# Main.net
KiCad netlist of a schematic drawn in Altium Designer
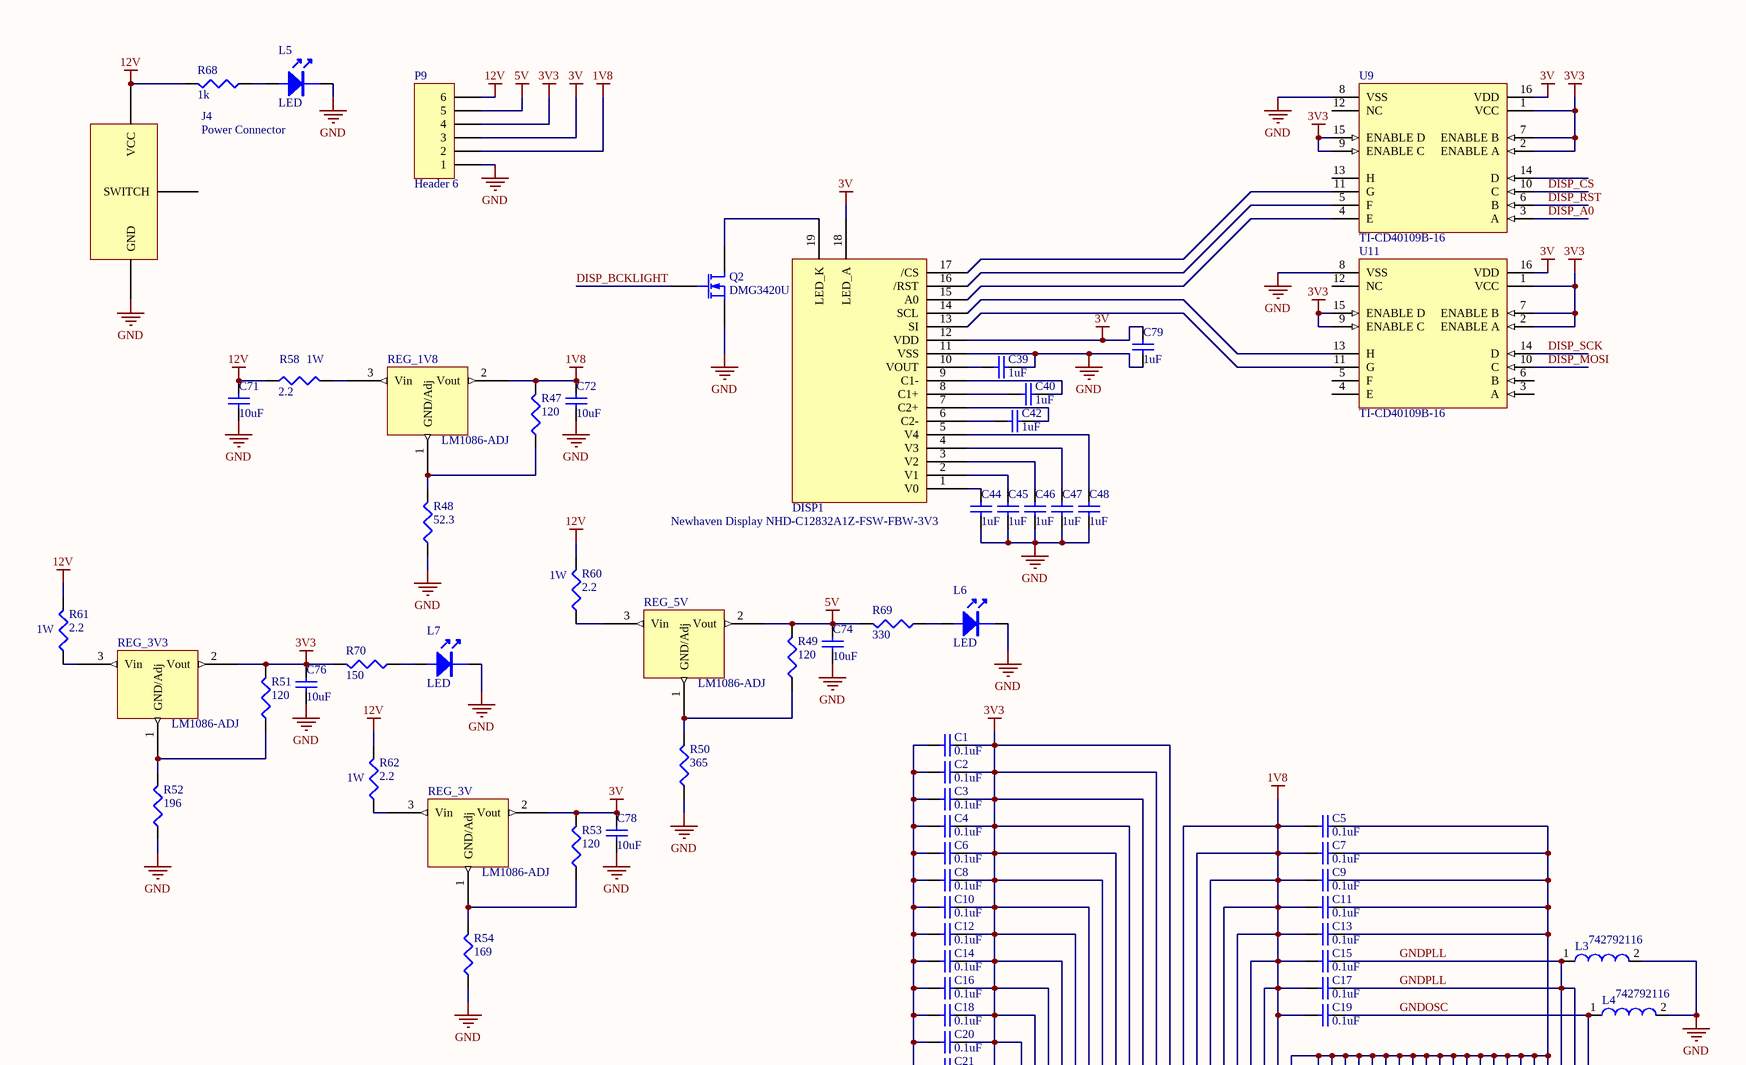
[diagram p0: Main.SchDoc, top left]
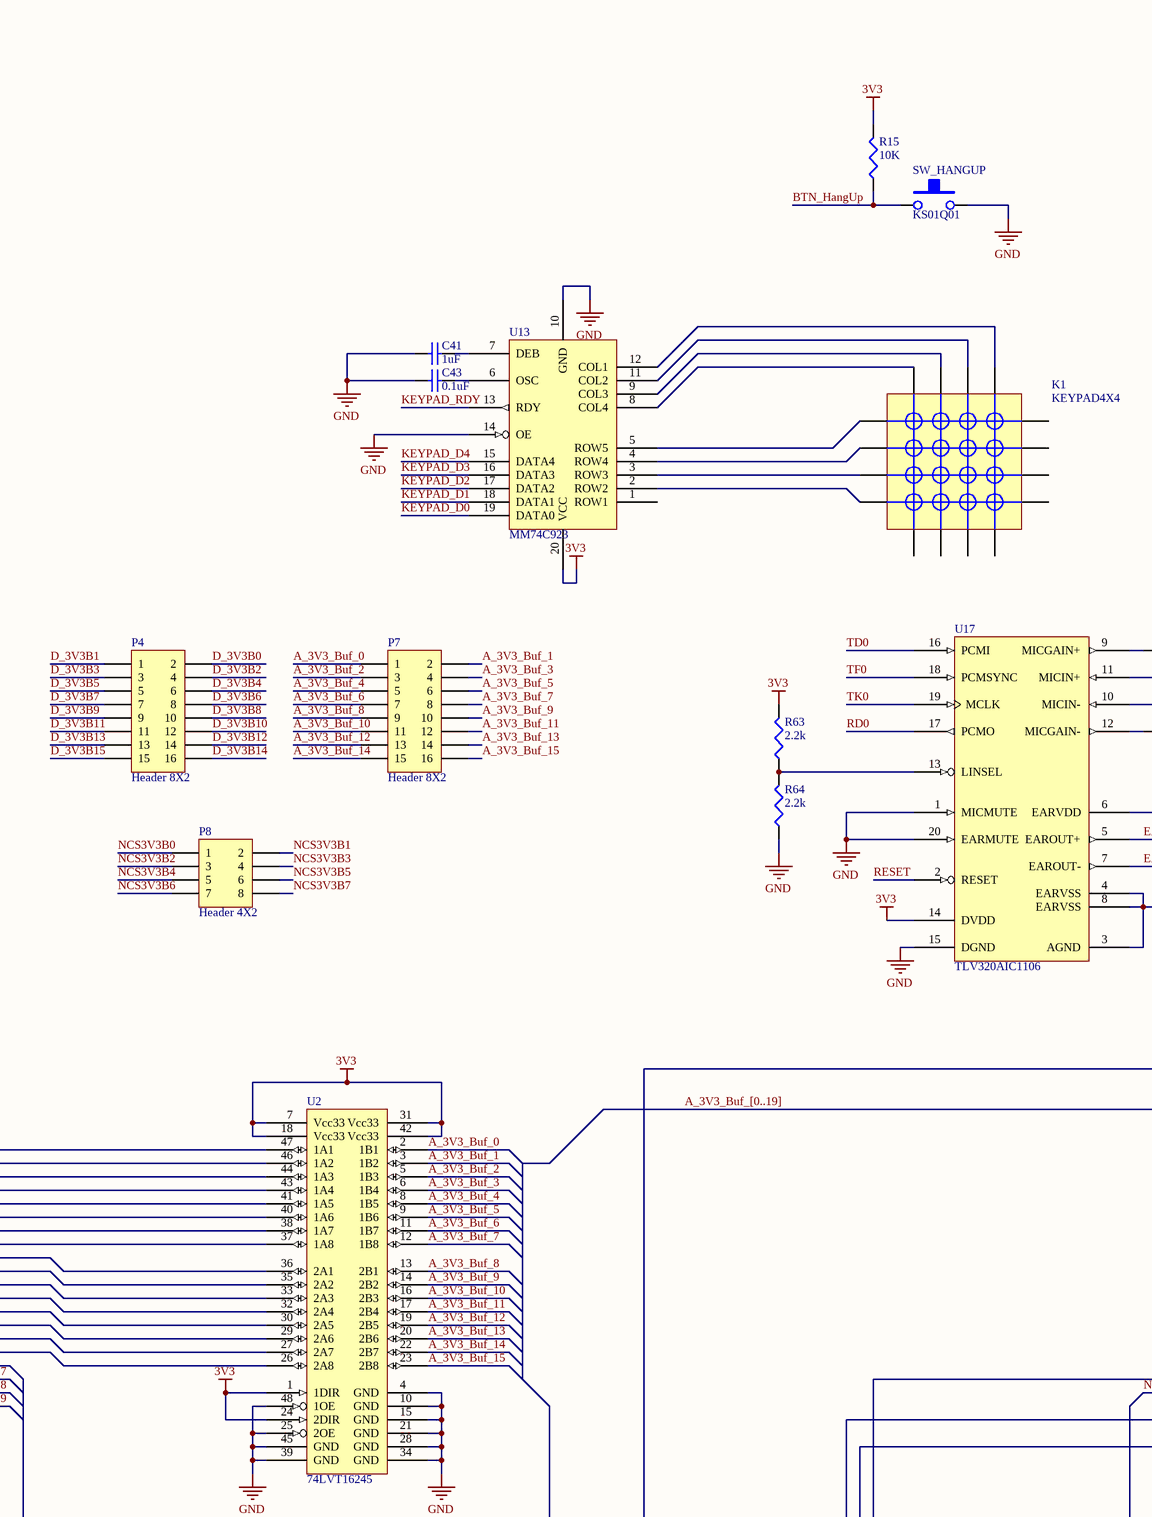
[diagram p1: Main.SchDoc, top middle]
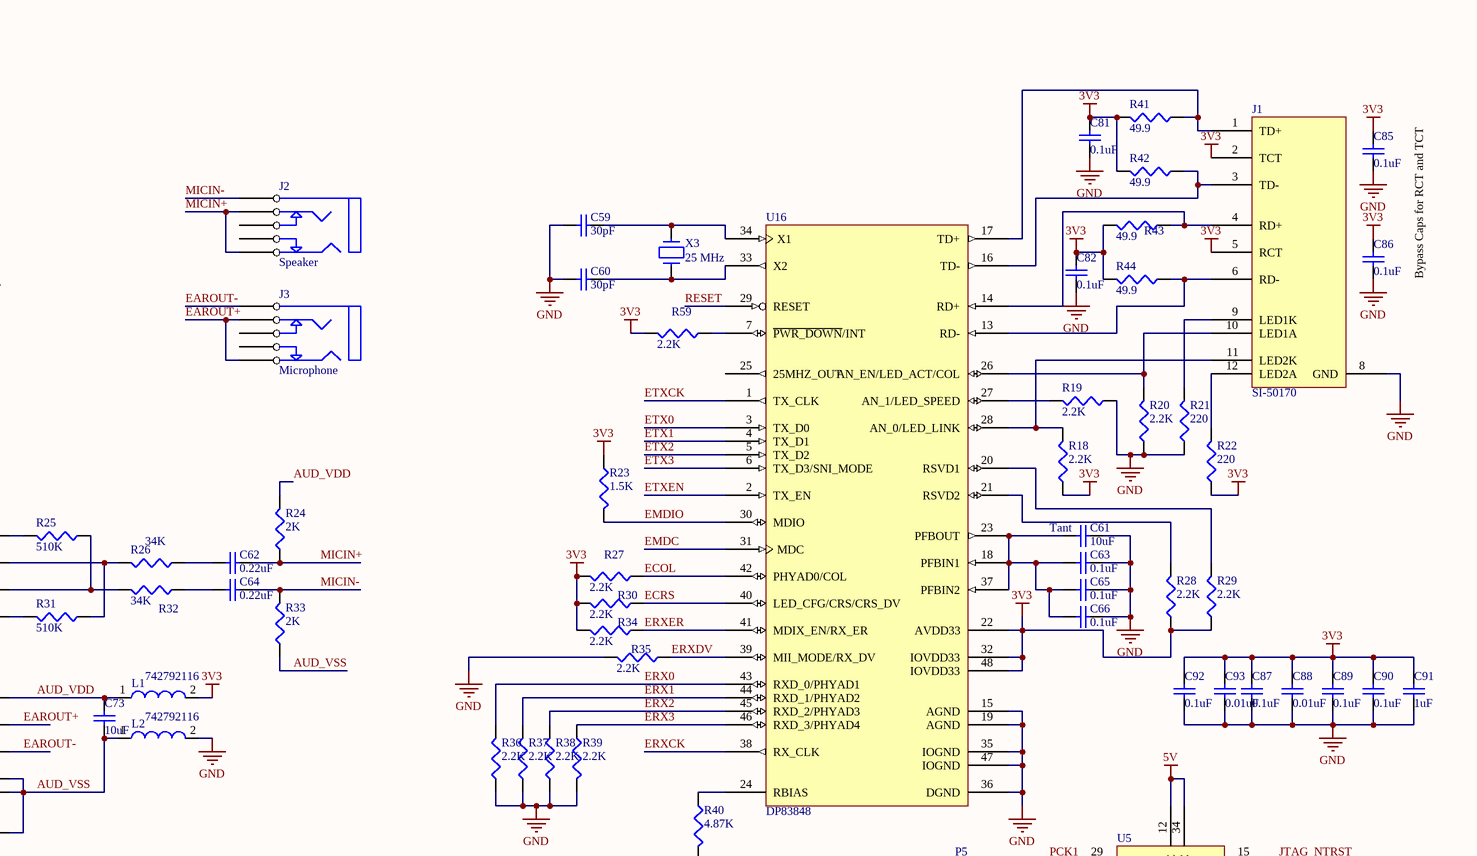
[diagram p2: Main.SchDoc, top right]
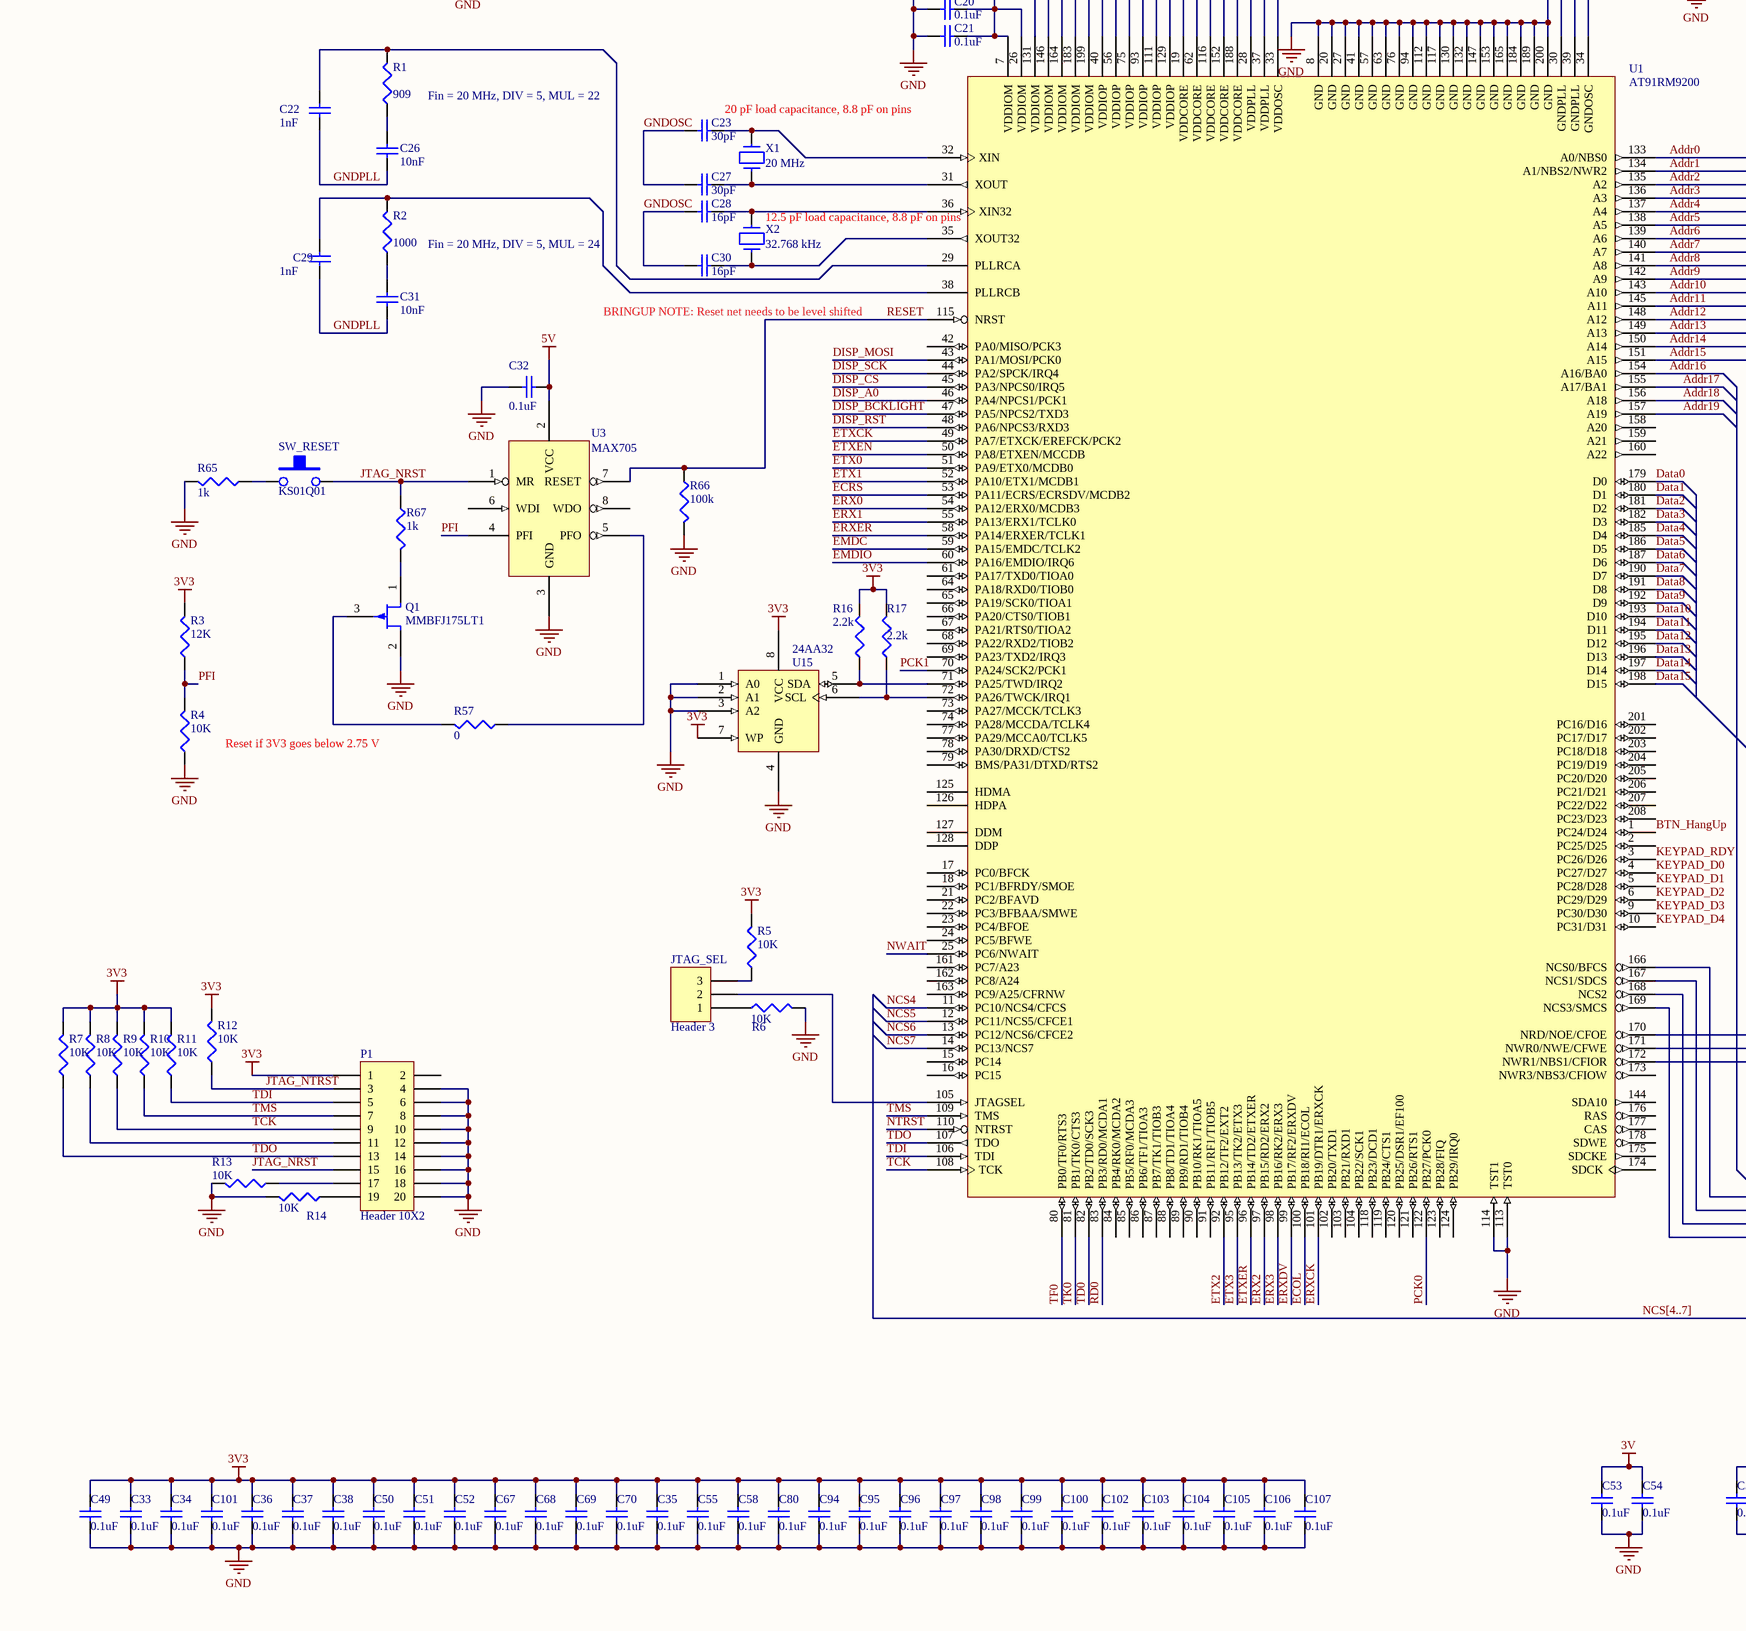
[diagram p3: Main.SchDoc, bottom left]
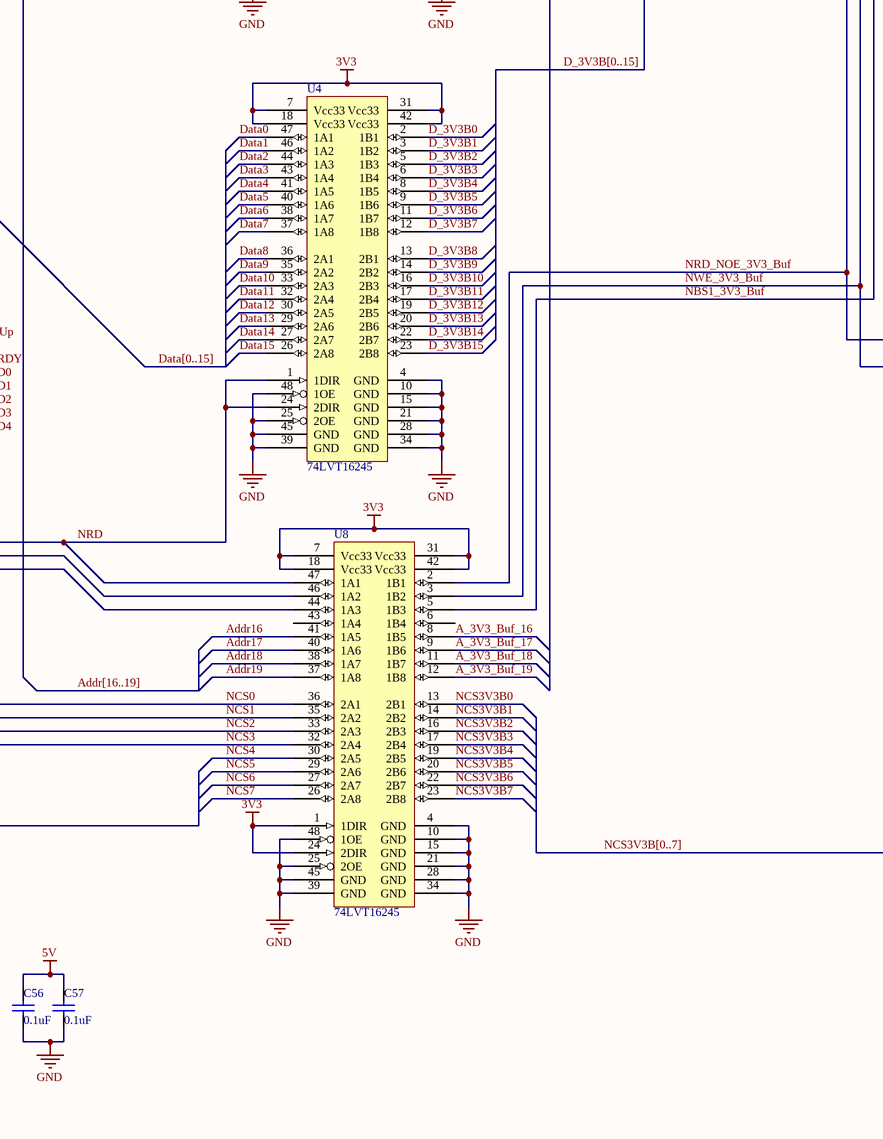
[diagram p4: Main.SchDoc, bottom middle]
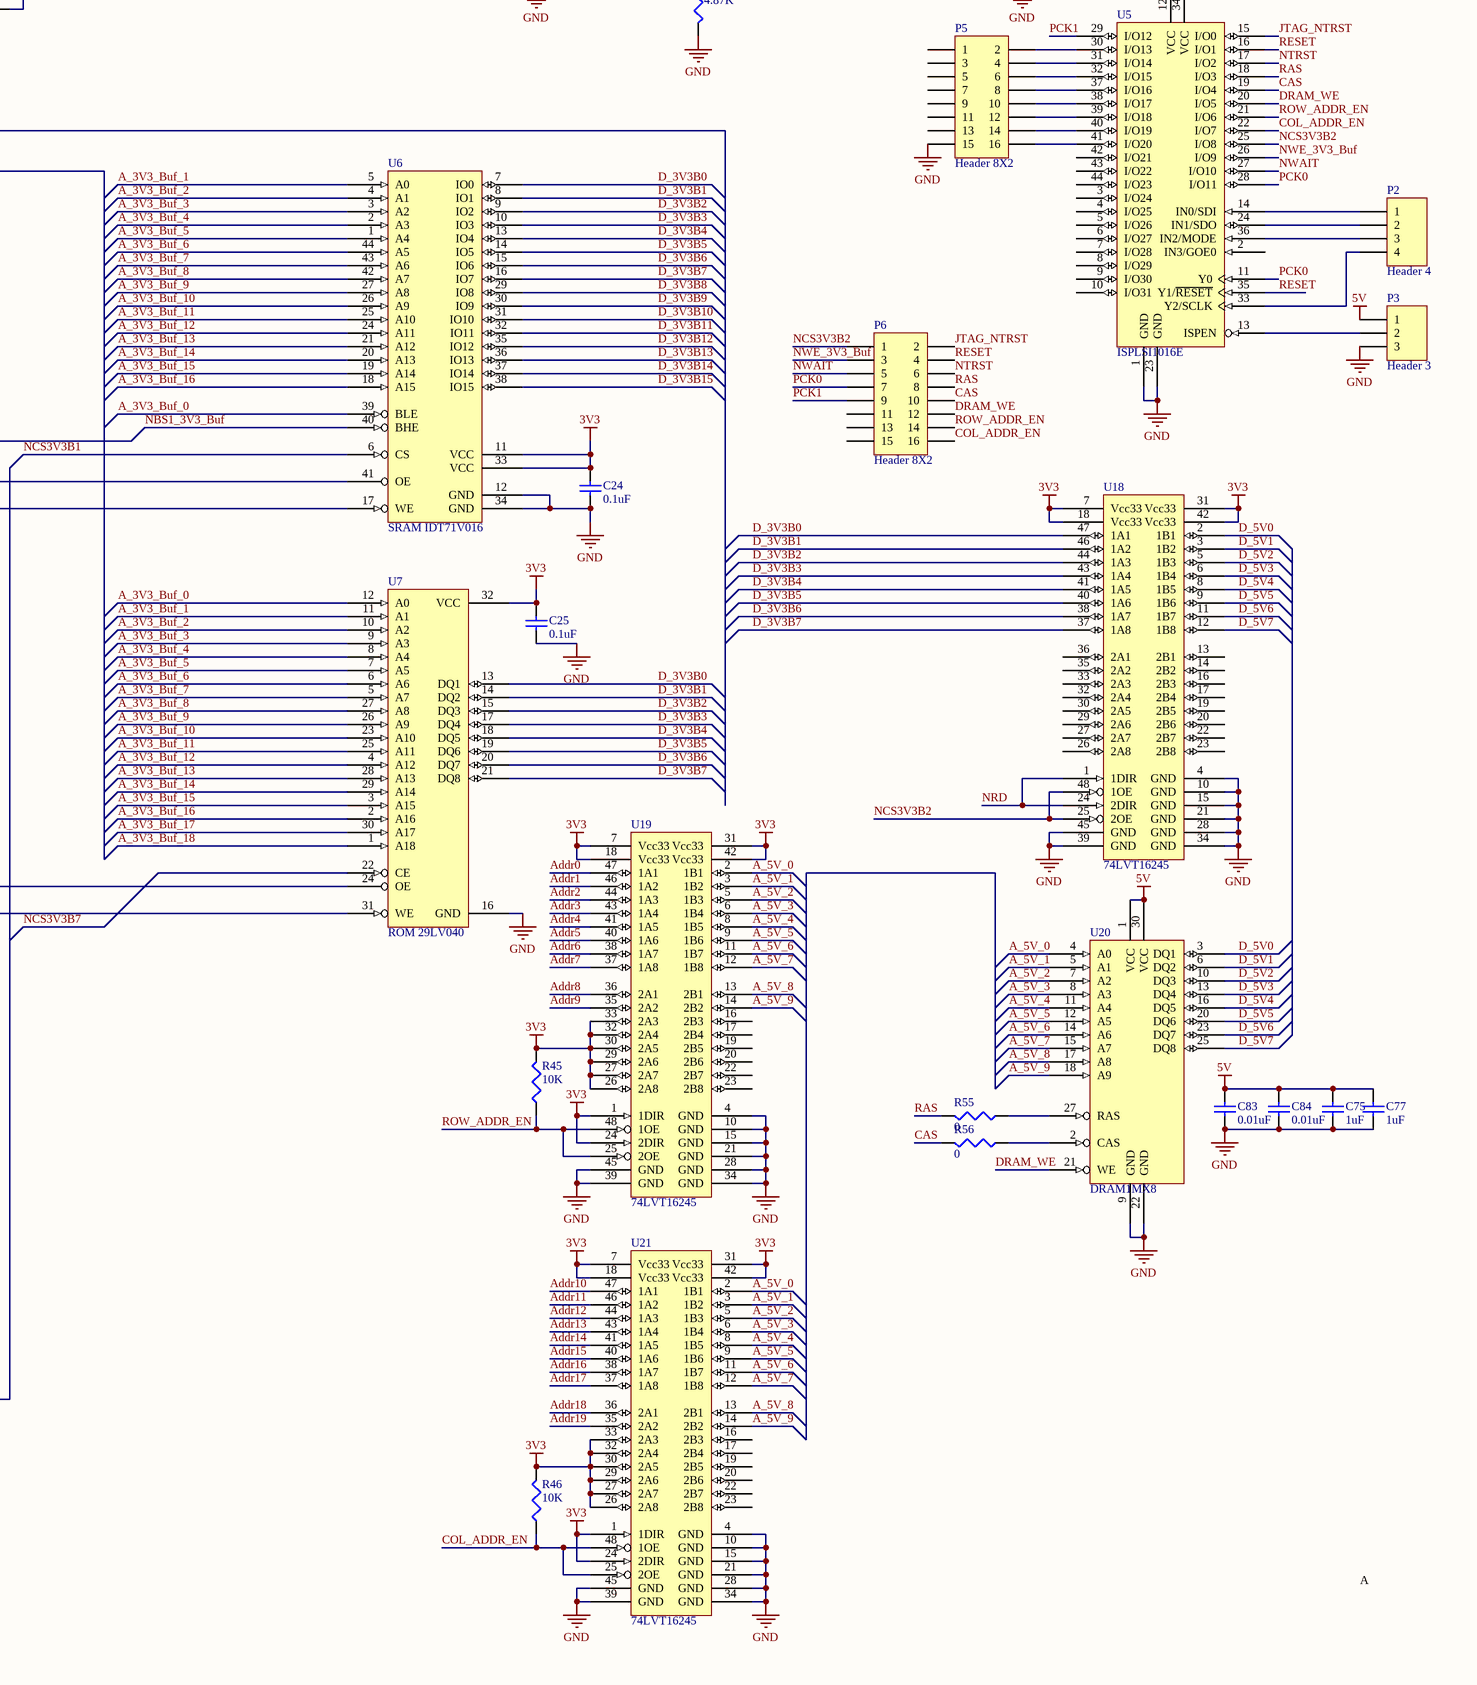
[diagram p5: Main.SchDoc, bottom right]

(export (version "E")
  (design (tool "Eeschema 10.0.6"))
  (components
    (comp (ref "C1")
      (value "0.1uF")
      (footprint "1608[0603]")
      (description "Capacitor (Semiconductor SIM Model)")
      (fields (field (name "PUBLISHER") "Altium Limited"))
      (libsource (lib "Miscellaneous Devices") (part "Cap Semi"))
    )
    (comp (ref "C2")
      (value "0.1uF")
      (footprint "1608[0603]")
      (description "Capacitor (Semiconductor SIM Model)")
      (fields (field (name "PUBLISHER") "Altium Limited"))
      (libsource (lib "Miscellaneous Devices") (part "Cap Semi"))
    )
    (comp (ref "C3")
      (value "0.1uF")
      (footprint "1608[0603]")
      (description "Capacitor (Semiconductor SIM Model)")
      (fields (field (name "PUBLISHER") "Altium Limited"))
      (libsource (lib "Miscellaneous Devices") (part "Cap Semi"))
    )
    (comp (ref "C4")
      (value "0.1uF")
      (footprint "1608[0603]")
      (description "Capacitor (Semiconductor SIM Model)")
      (fields (field (name "PUBLISHER") "Altium Limited"))
      (libsource (lib "Miscellaneous Devices") (part "Cap Semi"))
    )
    (comp (ref "C5")
      (value "0.1uF")
      (footprint "1608[0603]")
      (description "Capacitor (Semiconductor SIM Model)")
      (fields (field (name "PUBLISHER") "Altium Limited"))
      (libsource (lib "Miscellaneous Devices") (part "Cap Semi"))
    )
    (comp (ref "C6")
      (value "0.1uF")
      (footprint "1608[0603]")
      (description "Capacitor (Semiconductor SIM Model)")
      (fields (field (name "PUBLISHER") "Altium Limited"))
      (libsource (lib "Miscellaneous Devices") (part "Cap Semi"))
    )
    (comp (ref "C7")
      (value "0.1uF")
      (footprint "1608[0603]")
      (description "Capacitor (Semiconductor SIM Model)")
      (fields (field (name "PUBLISHER") "Altium Limited"))
      (libsource (lib "Miscellaneous Devices") (part "Cap Semi"))
    )
    (comp (ref "C8")
      (value "0.1uF")
      (footprint "1608[0603]")
      (description "Capacitor (Semiconductor SIM Model)")
      (fields (field (name "PUBLISHER") "Altium Limited"))
      (libsource (lib "Miscellaneous Devices") (part "Cap Semi"))
    )
    (comp (ref "C9")
      (value "0.1uF")
      (footprint "1608[0603]")
      (description "Capacitor (Semiconductor SIM Model)")
      (fields (field (name "PUBLISHER") "Altium Limited"))
      (libsource (lib "Miscellaneous Devices") (part "Cap Semi"))
    )
    (comp (ref "C10")
      (value "0.1uF")
      (footprint "1608[0603]")
      (description "Capacitor (Semiconductor SIM Model)")
      (fields (field (name "PUBLISHER") "Altium Limited"))
      (libsource (lib "Miscellaneous Devices") (part "Cap Semi"))
    )
    (comp (ref "C11")
      (value "0.1uF")
      (footprint "1608[0603]")
      (description "Capacitor (Semiconductor SIM Model)")
      (fields (field (name "PUBLISHER") "Altium Limited"))
      (libsource (lib "Miscellaneous Devices") (part "Cap Semi"))
    )
    (comp (ref "C12")
      (value "0.1uF")
      (footprint "1608[0603]")
      (description "Capacitor (Semiconductor SIM Model)")
      (fields (field (name "PUBLISHER") "Altium Limited"))
      (libsource (lib "Miscellaneous Devices") (part "Cap Semi"))
    )
    (comp (ref "C13")
      (value "0.1uF")
      (footprint "1608[0603]")
      (description "Capacitor (Semiconductor SIM Model)")
      (fields (field (name "PUBLISHER") "Altium Limited"))
      (libsource (lib "Miscellaneous Devices") (part "Cap Semi"))
    )
    (comp (ref "C14")
      (value "0.1uF")
      (footprint "1608[0603]")
      (description "Capacitor (Semiconductor SIM Model)")
      (fields (field (name "PUBLISHER") "Altium Limited"))
      (libsource (lib "Miscellaneous Devices") (part "Cap Semi"))
    )
    (comp (ref "C15")
      (value "0.1uF")
      (footprint "1608[0603]")
      (description "Capacitor (Semiconductor SIM Model)")
      (fields (field (name "PUBLISHER") "Altium Limited"))
      (libsource (lib "Miscellaneous Devices") (part "Cap Semi"))
    )
    (comp (ref "C16")
      (value "0.1uF")
      (footprint "1608[0603]")
      (description "Capacitor (Semiconductor SIM Model)")
      (fields (field (name "PUBLISHER") "Altium Limited"))
      (libsource (lib "Miscellaneous Devices") (part "Cap Semi"))
    )
    (comp (ref "C17")
      (value "0.1uF")
      (footprint "1608[0603]")
      (description "Capacitor (Semiconductor SIM Model)")
      (fields (field (name "PUBLISHER") "Altium Limited"))
      (libsource (lib "Miscellaneous Devices") (part "Cap Semi"))
    )
    (comp (ref "C18")
      (value "0.1uF")
      (footprint "1608[0603]")
      (description "Capacitor (Semiconductor SIM Model)")
      (fields (field (name "PUBLISHER") "Altium Limited"))
      (libsource (lib "Miscellaneous Devices") (part "Cap Semi"))
    )
    (comp (ref "C19")
      (value "0.1uF")
      (footprint "1608[0603]")
      (description "Capacitor (Semiconductor SIM Model)")
      (fields (field (name "PUBLISHER") "Altium Limited"))
      (libsource (lib "Miscellaneous Devices") (part "Cap Semi"))
    )
    (comp (ref "C20")
      (value "0.1uF")
      (footprint "1608[0603]")
      (description "Capacitor (Semiconductor SIM Model)")
      (fields (field (name "PUBLISHER") "Altium Limited"))
      (libsource (lib "Miscellaneous Devices") (part "Cap Semi"))
    )
    (comp (ref "C21")
      (value "0.1uF")
      (footprint "1608[0603]")
      (description "Capacitor (Semiconductor SIM Model)")
      (fields (field (name "PUBLISHER") "Altium Limited"))
      (libsource (lib "Miscellaneous Devices") (part "Cap Semi"))
    )
    (comp (ref "C22")
      (value "1nF")
      (footprint "1608[0603]")
      (description "Capacitor (Semiconductor SIM Model)")
      (fields (field (name "PUBLISHER") "Altium Limited"))
      (libsource (lib "Miscellaneous Devices") (part "Cap Semi"))
    )
    (comp (ref "C23")
      (value "30pF")
      (footprint "1608[0603]")
      (description "Capacitor (Semiconductor SIM Model)")
      (fields (field (name "PUBLISHER") "Altium Limited"))
      (libsource (lib "Miscellaneous Devices") (part "Cap Semi"))
    )
    (comp (ref "C24")
      (value "0.1uF")
      (footprint "1608[0603]")
      (description "Capacitor (Semiconductor SIM Model)")
      (fields (field (name "PUBLISHER") "Altium Limited"))
      (libsource (lib "Miscellaneous Devices") (part "Cap Semi"))
    )
    (comp (ref "C25")
      (value "0.1uF")
      (footprint "1608[0603]")
      (description "Capacitor (Semiconductor SIM Model)")
      (fields (field (name "PUBLISHER") "Altium Limited"))
      (libsource (lib "Miscellaneous Devices") (part "Cap Semi"))
    )
    (comp (ref "C26")
      (value "10nF")
      (footprint "1608[0603]")
      (description "Capacitor (Semiconductor SIM Model)")
      (fields (field (name "PUBLISHER") "Altium Limited"))
      (libsource (lib "Miscellaneous Devices") (part "Cap Semi"))
    )
    (comp (ref "C27")
      (value "30pF")
      (footprint "1608[0603]")
      (description "Capacitor (Semiconductor SIM Model)")
      (fields (field (name "PUBLISHER") "Altium Limited"))
      (libsource (lib "Miscellaneous Devices") (part "Cap Semi"))
    )
    (comp (ref "C28")
      (value "16pF")
      (footprint "1608[0603]")
      (description "Capacitor (Semiconductor SIM Model)")
      (fields (field (name "PUBLISHER") "Altium Limited"))
      (libsource (lib "Miscellaneous Devices") (part "Cap Semi"))
    )
    (comp (ref "C29")
      (value "1nF")
      (footprint "1608[0603]")
      (description "Capacitor (Semiconductor SIM Model)")
      (fields (field (name "PUBLISHER") "Altium Limited"))
      (libsource (lib "Miscellaneous Devices") (part "Cap Semi"))
    )
    (comp (ref "C30")
      (value "16pF")
      (footprint "1608[0603]")
      (description "Capacitor (Semiconductor SIM Model)")
      (fields (field (name "PUBLISHER") "Altium Limited"))
      (libsource (lib "Miscellaneous Devices") (part "Cap Semi"))
    )
    (comp (ref "C31")
      (value "10nF")
      (footprint "1608[0603]")
      (description "Capacitor (Semiconductor SIM Model)")
      (fields (field (name "PUBLISHER") "Altium Limited"))
      (libsource (lib "Miscellaneous Devices") (part "Cap Semi"))
    )
    (comp (ref "C32")
      (value "0.1uF")
      (footprint "1608[0603]")
      (description "Capacitor (Semiconductor SIM Model)")
      (fields (field (name "PUBLISHER") "Altium Limited"))
      (libsource (lib "Miscellaneous Devices") (part "Cap Semi"))
    )
    (comp (ref "C33")
      (value "0.1uF")
      (footprint "1608[0603]")
      (description "Capacitor (Semiconductor SIM Model)")
      (fields (field (name "PUBLISHER") "Altium Limited"))
      (libsource (lib "Miscellaneous Devices") (part "Cap Semi"))
    )
    (comp (ref "C34")
      (value "0.1uF")
      (footprint "1608[0603]")
      (description "Capacitor (Semiconductor SIM Model)")
      (fields (field (name "PUBLISHER") "Altium Limited"))
      (libsource (lib "Miscellaneous Devices") (part "Cap Semi"))
    )
    (comp (ref "C35")
      (value "0.1uF")
      (footprint "1608[0603]")
      (description "Capacitor (Semiconductor SIM Model)")
      (fields (field (name "PUBLISHER") "Altium Limited"))
      (libsource (lib "Miscellaneous Devices") (part "Cap Semi"))
    )
    (comp (ref "C36")
      (value "0.1uF")
      (footprint "1608[0603]")
      (description "Capacitor (Semiconductor SIM Model)")
      (fields (field (name "PUBLISHER") "Altium Limited"))
      (libsource (lib "Miscellaneous Devices") (part "Cap Semi"))
    )
    (comp (ref "C37")
      (value "0.1uF")
      (footprint "1608[0603]")
      (description "Capacitor (Semiconductor SIM Model)")
      (fields (field (name "PUBLISHER") "Altium Limited"))
      (libsource (lib "Miscellaneous Devices") (part "Cap Semi"))
    )
    (comp (ref "C38")
      (value "0.1uF")
      (footprint "1608[0603]")
      (description "Capacitor (Semiconductor SIM Model)")
      (fields (field (name "PUBLISHER") "Altium Limited"))
      (libsource (lib "Miscellaneous Devices") (part "Cap Semi"))
    )
    (comp (ref "C39")
      (value "1uF")
      (footprint "1608[0603]")
      (description "Capacitor (Semiconductor SIM Model)")
      (fields (field (name "PUBLISHER") "Altium Limited"))
      (libsource (lib "Miscellaneous Devices") (part "Cap Semi"))
    )
    (comp (ref "C40")
      (value "1uF")
      (footprint "1608[0603]")
      (description "Capacitor (Semiconductor SIM Model)")
      (fields (field (name "PUBLISHER") "Altium Limited"))
      (libsource (lib "Miscellaneous Devices") (part "Cap Semi"))
    )
    (comp (ref "C41")
      (value "1uF")
      (footprint "1608[0603]")
      (description "Capacitor (Semiconductor SIM Model)")
      (fields (field (name "PUBLISHER") "Altium Limited"))
      (libsource (lib "Miscellaneous Devices") (part "Cap Semi"))
    )
    (comp (ref "C42")
      (value "1uF")
      (footprint "1608[0603]")
      (description "Capacitor (Semiconductor SIM Model)")
      (fields (field (name "PUBLISHER") "Altium Limited"))
      (libsource (lib "Miscellaneous Devices") (part "Cap Semi"))
    )
    (comp (ref "C43")
      (value "0.1uF")
      (footprint "1608[0603]")
      (description "Capacitor (Semiconductor SIM Model)")
      (fields (field (name "PUBLISHER") "Altium Limited"))
      (libsource (lib "Miscellaneous Devices") (part "Cap Semi"))
    )
    (comp (ref "C44")
      (value "1uF")
      (footprint "1608[0603]")
      (description "Capacitor (Semiconductor SIM Model)")
      (fields (field (name "PUBLISHER") "Altium Limited"))
      (libsource (lib "Miscellaneous Devices") (part "Cap Semi"))
    )
    (comp (ref "C45")
      (value "1uF")
      (footprint "1608[0603]")
      (description "Capacitor (Semiconductor SIM Model)")
      (fields (field (name "PUBLISHER") "Altium Limited"))
      (libsource (lib "Miscellaneous Devices") (part "Cap Semi"))
    )
    (comp (ref "C46")
      (value "1uF")
      (footprint "1608[0603]")
      (description "Capacitor (Semiconductor SIM Model)")
      (fields (field (name "PUBLISHER") "Altium Limited"))
      (libsource (lib "Miscellaneous Devices") (part "Cap Semi"))
    )
    (comp (ref "C47")
      (value "1uF")
      (footprint "1608[0603]")
      (description "Capacitor (Semiconductor SIM Model)")
      (fields (field (name "PUBLISHER") "Altium Limited"))
      (libsource (lib "Miscellaneous Devices") (part "Cap Semi"))
    )
    (comp (ref "C48")
      (value "1uF")
      (footprint "1608[0603]")
      (description "Capacitor (Semiconductor SIM Model)")
      (fields (field (name "PUBLISHER") "Altium Limited"))
      (libsource (lib "Miscellaneous Devices") (part "Cap Semi"))
    )
    (comp (ref "C49")
      (value "0.1uF")
      (footprint "1608[0603]")
      (description "Capacitor (Semiconductor SIM Model)")
      (fields (field (name "PUBLISHER") "Altium Limited"))
      (libsource (lib "Miscellaneous Devices") (part "Cap Semi"))
    )
    (comp (ref "C50")
      (value "0.1uF")
      (footprint "1608[0603]")
      (description "Capacitor (Semiconductor SIM Model)")
      (fields (field (name "PUBLISHER") "Altium Limited"))
      (libsource (lib "Miscellaneous Devices") (part "Cap Semi"))
    )
    (comp (ref "C51")
      (value "0.1uF")
      (footprint "1608[0603]")
      (description "Capacitor (Semiconductor SIM Model)")
      (fields (field (name "PUBLISHER") "Altium Limited"))
      (libsource (lib "Miscellaneous Devices") (part "Cap Semi"))
    )
    (comp (ref "C52")
      (value "0.1uF")
      (footprint "1608[0603]")
      (description "Capacitor (Semiconductor SIM Model)")
      (fields (field (name "PUBLISHER") "Altium Limited"))
      (libsource (lib "Miscellaneous Devices") (part "Cap Semi"))
    )
    (comp (ref "C53")
      (value "0.1uF")
      (footprint "1608[0603]")
      (description "Capacitor (Semiconductor SIM Model)")
      (fields (field (name "PUBLISHER") "Altium Limited"))
      (libsource (lib "Miscellaneous Devices") (part "Cap Semi"))
    )
    (comp (ref "C54")
      (value "0.1uF")
      (footprint "1608[0603]")
      (description "Capacitor (Semiconductor SIM Model)")
      (fields (field (name "PUBLISHER") "Altium Limited"))
      (libsource (lib "Miscellaneous Devices") (part "Cap Semi"))
    )
    (comp (ref "C55")
      (value "0.1uF")
      (footprint "1608[0603]")
      (description "Capacitor (Semiconductor SIM Model)")
      (fields (field (name "PUBLISHER") "Altium Limited"))
      (libsource (lib "Miscellaneous Devices") (part "Cap Semi"))
    )
    (comp (ref "C56")
      (value "0.1uF")
      (footprint "1608[0603]")
      (description "Capacitor (Semiconductor SIM Model)")
      (fields (field (name "PUBLISHER") "Altium Limited"))
      (libsource (lib "Miscellaneous Devices") (part "Cap Semi"))
    )
    (comp (ref "C57")
      (value "0.1uF")
      (footprint "1608[0603]")
      (description "Capacitor (Semiconductor SIM Model)")
      (fields (field (name "PUBLISHER") "Altium Limited"))
      (libsource (lib "Miscellaneous Devices") (part "Cap Semi"))
    )
    (comp (ref "C58")
      (value "0.1uF")
      (footprint "1608[0603]")
      (description "Capacitor (Semiconductor SIM Model)")
      (fields (field (name "PUBLISHER") "Altium Limited"))
      (libsource (lib "Miscellaneous Devices") (part "Cap Semi"))
    )
    (comp (ref "C59")
      (value "30pF")
      (footprint "1608[0603]")
      (description "Capacitor (Semiconductor SIM Model)")
      (fields (field (name "PUBLISHER") "Altium Limited"))
      (libsource (lib "Miscellaneous Devices") (part "Cap Semi"))
    )
    (comp (ref "C60")
      (value "30pF")
      (footprint "1608[0603]")
      (description "Capacitor (Semiconductor SIM Model)")
      (fields (field (name "PUBLISHER") "Altium Limited"))
      (libsource (lib "Miscellaneous Devices") (part "Cap Semi"))
    )
    (comp (ref "C61")
      (value "Tant")
      (footprint "C1206")
      (description "Capacitor (Semiconductor SIM Model)")
      (fields (field (name "ALTIUM_VALUE") "10uF") (field (name "PUBLISHER") "Altium Limited"))
      (libsource (lib "Miscellaneous Devices") (part "Cap Semi"))
    )
    (comp (ref "C62")
      (value "0.22uF")
      (footprint "1608[0603]")
      (description "Capacitor (Semiconductor SIM Model)")
      (fields (field (name "PUBLISHER") "Altium Limited"))
      (libsource (lib "Miscellaneous Devices") (part "Cap Semi"))
    )
    (comp (ref "C63")
      (value "0.1uF")
      (footprint "1608[0603]")
      (description "Capacitor (Semiconductor SIM Model)")
      (fields (field (name "PUBLISHER") "Altium Limited"))
      (libsource (lib "Miscellaneous Devices") (part "Cap Semi"))
    )
    (comp (ref "C64")
      (value "0.22uF")
      (footprint "1608[0603]")
      (description "Capacitor (Semiconductor SIM Model)")
      (fields (field (name "PUBLISHER") "Altium Limited"))
      (libsource (lib "Miscellaneous Devices") (part "Cap Semi"))
    )
    (comp (ref "C65")
      (value "0.1uF")
      (footprint "1608[0603]")
      (description "Capacitor (Semiconductor SIM Model)")
      (fields (field (name "PUBLISHER") "Altium Limited"))
      (libsource (lib "Miscellaneous Devices") (part "Cap Semi"))
    )
    (comp (ref "C66")
      (value "0.1uF")
      (footprint "1608[0603]")
      (description "Capacitor (Semiconductor SIM Model)")
      (fields (field (name "PUBLISHER") "Altium Limited"))
      (libsource (lib "Miscellaneous Devices") (part "Cap Semi"))
    )
    (comp (ref "C67")
      (value "0.1uF")
      (footprint "1608[0603]")
      (description "Capacitor (Semiconductor SIM Model)")
      (fields (field (name "PUBLISHER") "Altium Limited"))
      (libsource (lib "Miscellaneous Devices") (part "Cap Semi"))
    )
    (comp (ref "C68")
      (value "0.1uF")
      (footprint "1608[0603]")
      (description "Capacitor (Semiconductor SIM Model)")
      (fields (field (name "PUBLISHER") "Altium Limited"))
      (libsource (lib "Miscellaneous Devices") (part "Cap Semi"))
    )
    (comp (ref "C69")
      (value "0.1uF")
      (footprint "1608[0603]")
      (description "Capacitor (Semiconductor SIM Model)")
      (fields (field (name "PUBLISHER") "Altium Limited"))
      (libsource (lib "Miscellaneous Devices") (part "Cap Semi"))
    )
    (comp (ref "C70")
      (value "0.1uF")
      (footprint "1608[0603]")
      (description "Capacitor (Semiconductor SIM Model)")
      (fields (field (name "PUBLISHER") "Altium Limited"))
      (libsource (lib "Miscellaneous Devices") (part "Cap Semi"))
    )
    (comp (ref "C71")
      (value "10uF")
      (footprint "C1206")
      (description "Capacitor (Semiconductor SIM Model)")
      (fields (field (name "PUBLISHER") "Altium Limited"))
      (libsource (lib "Miscellaneous Devices") (part "Cap Semi"))
    )
    (comp (ref "C72")
      (value "10uF")
      (footprint "C1206")
      (description "Capacitor (Semiconductor SIM Model)")
      (fields (field (name "PUBLISHER") "Altium Limited"))
      (libsource (lib "Miscellaneous Devices") (part "Cap Semi"))
    )
    (comp (ref "C73")
      (value "10uF")
      (footprint "C1206")
      (description "Capacitor (Semiconductor SIM Model)")
      (fields (field (name "PUBLISHER") "Altium Limited"))
      (libsource (lib "Miscellaneous Devices") (part "Cap Semi"))
    )
    (comp (ref "C74")
      (value "10uF")
      (footprint "C1206")
      (description "Capacitor (Semiconductor SIM Model)")
      (fields (field (name "PUBLISHER") "Altium Limited"))
      (libsource (lib "Miscellaneous Devices") (part "Cap Semi"))
    )
    (comp (ref "C75")
      (value "1uF")
      (footprint "1608[0603]")
      (description "Capacitor (Semiconductor SIM Model)")
      (fields (field (name "PUBLISHER") "Altium Limited"))
      (libsource (lib "Miscellaneous Devices") (part "Cap Semi"))
    )
    (comp (ref "C76")
      (value "10uF")
      (footprint "C1206")
      (description "Capacitor (Semiconductor SIM Model)")
      (fields (field (name "PUBLISHER") "Altium Limited"))
      (libsource (lib "Miscellaneous Devices") (part "Cap Semi"))
    )
    (comp (ref "C77")
      (value "1uF")
      (footprint "1608[0603]")
      (description "Capacitor (Semiconductor SIM Model)")
      (fields (field (name "PUBLISHER") "Altium Limited"))
      (libsource (lib "Miscellaneous Devices") (part "Cap Semi"))
    )
    (comp (ref "C78")
      (value "10uF")
      (footprint "C1206")
      (description "Capacitor (Semiconductor SIM Model)")
      (fields (field (name "PUBLISHER") "Altium Limited"))
      (libsource (lib "Miscellaneous Devices") (part "Cap Semi"))
    )
    (comp (ref "C79")
      (value "1uF")
      (footprint "1608[0603]")
      (description "Capacitor (Semiconductor SIM Model)")
      (fields (field (name "PUBLISHER") "Altium Limited"))
      (libsource (lib "Miscellaneous Devices") (part "Cap Semi"))
    )
    (comp (ref "C80")
      (value "0.1uF")
      (footprint "1608[0603]")
      (description "Capacitor (Semiconductor SIM Model)")
      (fields (field (name "PUBLISHER") "Altium Limited"))
      (libsource (lib "Miscellaneous Devices") (part "Cap Semi"))
    )
    (comp (ref "C81")
      (value "0.1uF")
      (footprint "1608[0603]")
      (description "Capacitor (Semiconductor SIM Model)")
      (fields (field (name "PUBLISHER") "Altium Limited"))
      (libsource (lib "Miscellaneous Devices") (part "Cap Semi"))
    )
    (comp (ref "C82")
      (value "0.1uF")
      (footprint "1608[0603]")
      (description "Capacitor (Semiconductor SIM Model)")
      (fields (field (name "PUBLISHER") "Altium Limited"))
      (libsource (lib "Miscellaneous Devices") (part "Cap Semi"))
    )
    (comp (ref "C83")
      (value "0.01uF")
      (footprint "1608[0603]")
      (description "Capacitor (Semiconductor SIM Model)")
      (fields (field (name "PUBLISHER") "Altium Limited"))
      (libsource (lib "Miscellaneous Devices") (part "Cap Semi"))
    )
    (comp (ref "C84")
      (value "0.01uF")
      (footprint "1608[0603]")
      (description "Capacitor (Semiconductor SIM Model)")
      (fields (field (name "PUBLISHER") "Altium Limited"))
      (libsource (lib "Miscellaneous Devices") (part "Cap Semi"))
    )
    (comp (ref "C85")
      (value "0.1uF")
      (footprint "1608[0603]")
      (description "Capacitor (Semiconductor SIM Model)")
      (fields (field (name "PUBLISHER") "Altium Limited"))
      (libsource (lib "Miscellaneous Devices") (part "Cap Semi"))
    )
    (comp (ref "C86")
      (value "0.1uF")
      (footprint "1608[0603]")
      (description "Capacitor (Semiconductor SIM Model)")
      (fields (field (name "PUBLISHER") "Altium Limited"))
      (libsource (lib "Miscellaneous Devices") (part "Cap Semi"))
    )
    (comp (ref "C87")
      (value "0.1uF")
      (footprint "1608[0603]")
      (description "Capacitor (Semiconductor SIM Model)")
      (fields (field (name "PUBLISHER") "Altium Limited"))
      (libsource (lib "Miscellaneous Devices") (part "Cap Semi"))
    )
    (comp (ref "C88")
      (value "0.01uF")
      (footprint "1608[0603]")
      (description "Capacitor (Semiconductor SIM Model)")
      (fields (field (name "PUBLISHER") "Altium Limited"))
      (libsource (lib "Miscellaneous Devices") (part "Cap Semi"))
    )
    (comp (ref "C89")
      (value "0.1uF")
      (footprint "1608[0603]")
      (description "Capacitor (Semiconductor SIM Model)")
      (fields (field (name "PUBLISHER") "Altium Limited"))
      (libsource (lib "Miscellaneous Devices") (part "Cap Semi"))
    )
    (comp (ref "C90")
      (value "0.1uF")
      (footprint "1608[0603]")
      (description "Capacitor (Semiconductor SIM Model)")
      (fields (field (name "PUBLISHER") "Altium Limited"))
      (libsource (lib "Miscellaneous Devices") (part "Cap Semi"))
    )
    (comp (ref "C91")
      (value "1uF")
      (footprint "1608[0603]")
      (description "Capacitor (Semiconductor SIM Model)")
      (fields (field (name "PUBLISHER") "Altium Limited"))
      (libsource (lib "Miscellaneous Devices") (part "Cap Semi"))
    )
    (comp (ref "C92")
      (value "0.1uF")
      (footprint "1608[0603]")
      (description "Capacitor (Semiconductor SIM Model)")
      (fields (field (name "PUBLISHER") "Altium Limited"))
      (libsource (lib "Miscellaneous Devices") (part "Cap Semi"))
    )
    (comp (ref "C93")
      (value "0.01uF")
      (footprint "1608[0603]")
      (description "Capacitor (Semiconductor SIM Model)")
      (fields (field (name "PUBLISHER") "Altium Limited"))
      (libsource (lib "Miscellaneous Devices") (part "Cap Semi"))
    )
    (comp (ref "C94")
      (value "0.1uF")
      (footprint "1608[0603]")
      (description "Capacitor (Semiconductor SIM Model)")
      (fields (field (name "PUBLISHER") "Altium Limited"))
      (libsource (lib "Miscellaneous Devices") (part "Cap Semi"))
    )
    (comp (ref "C95")
      (value "0.1uF")
      (footprint "1608[0603]")
      (description "Capacitor (Semiconductor SIM Model)")
      (fields (field (name "PUBLISHER") "Altium Limited"))
      (libsource (lib "Miscellaneous Devices") (part "Cap Semi"))
    )
    (comp (ref "C96")
      (value "0.1uF")
      (footprint "1608[0603]")
      (description "Capacitor (Semiconductor SIM Model)")
      (fields (field (name "PUBLISHER") "Altium Limited"))
      (libsource (lib "Miscellaneous Devices") (part "Cap Semi"))
    )
    (comp (ref "C97")
      (value "0.1uF")
      (footprint "1608[0603]")
      (description "Capacitor (Semiconductor SIM Model)")
      (fields (field (name "PUBLISHER") "Altium Limited"))
      (libsource (lib "Miscellaneous Devices") (part "Cap Semi"))
    )
    (comp (ref "C98")
      (value "0.1uF")
      (footprint "1608[0603]")
      (description "Capacitor (Semiconductor SIM Model)")
      (fields (field (name "PUBLISHER") "Altium Limited"))
      (libsource (lib "Miscellaneous Devices") (part "Cap Semi"))
    )
    (comp (ref "C99")
      (value "0.1uF")
      (footprint "1608[0603]")
      (description "Capacitor (Semiconductor SIM Model)")
      (fields (field (name "PUBLISHER") "Altium Limited"))
      (libsource (lib "Miscellaneous Devices") (part "Cap Semi"))
    )
    (comp (ref "C100")
      (value "0.1uF")
      (footprint "1608[0603]")
      (description "Capacitor (Semiconductor SIM Model)")
      (fields (field (name "PUBLISHER") "Altium Limited"))
      (libsource (lib "Miscellaneous Devices") (part "Cap Semi"))
    )
    (comp (ref "C101")
      (value "0.1uF")
      (footprint "1608[0603]")
      (description "Capacitor (Semiconductor SIM Model)")
      (fields (field (name "PUBLISHER") "Altium Limited"))
      (libsource (lib "Miscellaneous Devices") (part "Cap Semi"))
    )
    (comp (ref "C102")
      (value "0.1uF")
      (footprint "1608[0603]")
      (description "Capacitor (Semiconductor SIM Model)")
      (fields (field (name "PUBLISHER") "Altium Limited"))
      (libsource (lib "Miscellaneous Devices") (part "Cap Semi"))
    )
    (comp (ref "C103")
      (value "0.1uF")
      (footprint "1608[0603]")
      (description "Capacitor (Semiconductor SIM Model)")
      (fields (field (name "PUBLISHER") "Altium Limited"))
      (libsource (lib "Miscellaneous Devices") (part "Cap Semi"))
    )
    (comp (ref "C104")
      (value "0.1uF")
      (footprint "1608[0603]")
      (description "Capacitor (Semiconductor SIM Model)")
      (fields (field (name "PUBLISHER") "Altium Limited"))
      (libsource (lib "Miscellaneous Devices") (part "Cap Semi"))
    )
    (comp (ref "C105")
      (value "0.1uF")
      (footprint "1608[0603]")
      (description "Capacitor (Semiconductor SIM Model)")
      (fields (field (name "PUBLISHER") "Altium Limited"))
      (libsource (lib "Miscellaneous Devices") (part "Cap Semi"))
    )
    (comp (ref "C106")
      (value "0.1uF")
      (footprint "1608[0603]")
      (description "Capacitor (Semiconductor SIM Model)")
      (fields (field (name "PUBLISHER") "Altium Limited"))
      (libsource (lib "Miscellaneous Devices") (part "Cap Semi"))
    )
    (comp (ref "C107")
      (value "0.1uF")
      (footprint "1608[0603]")
      (description "Capacitor (Semiconductor SIM Model)")
      (fields (field (name "PUBLISHER") "Altium Limited"))
      (libsource (lib "Miscellaneous Devices") (part "Cap Semi"))
    )
    (comp (ref "DISP1")
      (value "Newhaven Display NHD-C12832A1Z-FSW-FBW-3V3")
      (footprint "PCB-1539121-1")
      (libsource (lib "Display-NHD-C12832") (part "SYM-1539121-1"))
    )
    (comp (ref "J1")
      (value "SI-50170")
      (footprint "SI51070")
      (description "MagJack SI-50170 Ethernet Jack with LEDs")
      (libsource (lib "eecs5x") (part "SI-50170"))
    )
    (comp (ref "J2")
      (value "Speaker")
      (footprint "SJ1-352")
      (description "3.5mm Stereo Jack with Switches PHONEJACK STEREO SW")
      (libsource (lib "eecs5x") (part "PHONEJACK STEREO SW"))
    )
    (comp (ref "J3")
      (value "Microphone")
      (footprint "SJ1-352")
      (description "3.5mm Stereo Jack with Switches PHONEJACK STEREO SW")
      (libsource (lib "eecs5x") (part "PHONEJACK STEREO SW"))
    )
    (comp (ref "J4")
      (value "Power Connector")
      (footprint "EJ508A")
      (description "EJ508A")
      (libsource (lib "EEW_Client") (part "EJ508A"))
    )
    (comp (ref "JTAG_SEL")
      (value "Header 3")
      (footprint "HDR1X3")
      (description "Header, 3-Pin")
      (fields (field (name "PUBLISHER") "Altium Limited"))
      (libsource (lib "Miscellaneous Connectors") (part "Header 3"))
    )
    (comp (ref "K1")
      (value "KEYPAD4X4")
      (footprint "SIP8")
      (description "Grayhill 4x4 Keypad")
      (libsource (lib "eecs5x") (part "KEYPAD4X4"))
    )
    (comp (ref "L1")
      (value "742792116")
      (footprint "SMD-1206")
      (description "SMD EMI Suppression Ferrite Bead WE-CBF, Z = 500 Ohm")
      (libsource (lib "WE-CBF SMD EMI Suppression Ferrite Bead") (part "742792116"))
    )
    (comp (ref "L2")
      (value "742792116")
      (footprint "SMD-1206")
      (description "SMD EMI Suppression Ferrite Bead WE-CBF, Z = 500 Ohm")
      (libsource (lib "WE-CBF SMD EMI Suppression Ferrite Bead") (part "742792116"))
    )
    (comp (ref "L3")
      (value "742792116")
      (footprint "SMD-1206")
      (description "SMD EMI Suppression Ferrite Bead WE-CBF, Z = 500 Ohm")
      (libsource (lib "WE-CBF SMD EMI Suppression Ferrite Bead") (part "742792116"))
    )
    (comp (ref "L4")
      (value "742792116")
      (footprint "SMD-1206")
      (description "SMD EMI Suppression Ferrite Bead WE-CBF, Z = 500 Ohm")
      (libsource (lib "WE-CBF SMD EMI Suppression Ferrite Bead") (part "742792116"))
    )
    (comp (ref "L5")
      (value "LED")
      (footprint "LTST-C191KFKT")
      (libsource (lib "EEW_Client") (part "LTST-C191KFKT"))
    )
    (comp (ref "L6")
      (value "LED")
      (footprint "LTST-C191KFKT")
      (libsource (lib "EEW_Client") (part "LTST-C191KFKT"))
    )
    (comp (ref "L7")
      (value "LED")
      (footprint "LTST-C191KFKT")
      (libsource (lib "EEW_Client") (part "LTST-C191KFKT"))
    )
    (comp (ref "P1")
      (value "Header 10X2")
      (footprint "HDR2X10")
      (description "Header, 10-Pin, Dual row")
      (fields (field (name "PUBLISHER") "Altium Limited"))
      (libsource (lib "Miscellaneous Connectors") (part "Header 10X2"))
    )
    (comp (ref "P2")
      (value "Header 4")
      (footprint "HDR1X4")
      (description "Header, 4-Pin")
      (fields (field (name "PUBLISHER") "Altium Limited"))
      (libsource (lib "Miscellaneous Connectors") (part "Header 4"))
    )
    (comp (ref "P3")
      (value "Header 3")
      (footprint "HDR1X3")
      (description "Header, 3-Pin")
      (fields (field (name "PUBLISHER") "Altium Limited"))
      (libsource (lib "") (part "Header 3_1"))
    )
    (comp (ref "P4")
      (value "Header 8X2")
      (footprint "HDR2X8")
      (description "Header, 8-Pin, Dual row")
      (fields (field (name "PUBLISHER") "Altium Limited"))
      (libsource (lib "Miscellaneous Connectors") (part "Header 8X2"))
    )
    (comp (ref "P5")
      (value "Header 8X2")
      (footprint "HDR2X8")
      (description "Header, 8-Pin, Dual row")
      (fields (field (name "PUBLISHER") "Altium Limited"))
      (libsource (lib "Miscellaneous Connectors") (part "Header 8X2"))
    )
    (comp (ref "P6")
      (value "Header 8X2")
      (footprint "HDR2X8")
      (description "Header, 8-Pin, Dual row")
      (fields (field (name "PUBLISHER") "Altium Limited"))
      (libsource (lib "Miscellaneous Connectors") (part "Header 8X2"))
    )
    (comp (ref "P7")
      (value "Header 8X2")
      (footprint "HDR2X8")
      (description "Header, 8-Pin, Dual row")
      (fields (field (name "PUBLISHER") "Altium Limited"))
      (libsource (lib "Miscellaneous Connectors") (part "Header 8X2"))
    )
    (comp (ref "P8")
      (value "Header 4X2")
      (footprint "HDR2X4")
      (description "Header, 4-Pin, Dual row")
      (fields (field (name "PUBLISHER") "Altium Limited"))
      (libsource (lib "Miscellaneous Connectors") (part "Header 4X2"))
    )
    (comp (ref "P9")
      (value "Header 6")
      (footprint "HDR1X6")
      (description "Header, 6-Pin")
      (fields (field (name "PUBLISHER") "Altium Limited"))
      (libsource (lib "Miscellaneous Connectors") (part "Header 6"))
    )
    (comp (ref "Q1")
      (value "MMBFJ175LT1")
      (footprint "ONSC-SOT-23-3-318-08_V")
      (description "JFET Chopper, P-Channel - Depletion, 3-Pin SOT-23, Tape and Reel")
      (fields (field (name "MANUFACTURER") "On Semiconductor"))
      (libsource (lib "ON Semi JFETs") (part "MMBFJ175LT1"))
    )
    (comp (ref "Q2") (value "DMG3420U") (footprint "SOT23") (libsource (lib "EEW_Client") (part "DMG3420")))
    (comp (ref "R1")
      (value "909")
      (footprint "J1-0603")
      (description "Resistor")
      (fields (field (name "Comment") "Res3") (field (name "PUBLISHER") "Altium Limited"))
      (libsource (lib "Miscellaneous Devices") (part "Res3"))
    )
    (comp (ref "R2")
      (value "1000")
      (footprint "J1-0603")
      (description "Resistor")
      (fields (field (name "Comment") "Res3") (field (name "PUBLISHER") "Altium Limited"))
      (libsource (lib "Miscellaneous Devices") (part "Res3"))
    )
    (comp (ref "R3")
      (value "12K")
      (footprint "J1-0603")
      (description "Resistor")
      (fields (field (name "Comment") "Res3") (field (name "PUBLISHER") "Altium Limited"))
      (libsource (lib "Miscellaneous Devices") (part "Res3"))
    )
    (comp (ref "R4")
      (value "10K")
      (footprint "J1-0603")
      (description "Resistor")
      (fields (field (name "Comment") "Res3") (field (name "PUBLISHER") "Altium Limited"))
      (libsource (lib "Miscellaneous Devices") (part "Res3"))
    )
    (comp (ref "R5")
      (value "10K")
      (footprint "J1-0603")
      (description "Resistor")
      (fields (field (name "Comment") "Res3") (field (name "PUBLISHER") "Altium Limited"))
      (libsource (lib "Miscellaneous Devices") (part "Res3"))
    )
    (comp (ref "R6")
      (value "10K")
      (footprint "J1-0603")
      (description "Resistor")
      (fields (field (name "Comment") "Res3") (field (name "PUBLISHER") "Altium Limited"))
      (libsource (lib "Miscellaneous Devices") (part "Res3"))
    )
    (comp (ref "R7")
      (value "10K")
      (footprint "J1-0603")
      (description "Resistor")
      (fields (field (name "Comment") "Res3") (field (name "PUBLISHER") "Altium Limited"))
      (libsource (lib "Miscellaneous Devices") (part "Res3"))
    )
    (comp (ref "R8")
      (value "10K")
      (footprint "J1-0603")
      (description "Resistor")
      (fields (field (name "Comment") "Res3") (field (name "PUBLISHER") "Altium Limited"))
      (libsource (lib "Miscellaneous Devices") (part "Res3"))
    )
    (comp (ref "R9")
      (value "10K")
      (footprint "J1-0603")
      (description "Resistor")
      (fields (field (name "Comment") "Res3") (field (name "PUBLISHER") "Altium Limited"))
      (libsource (lib "Miscellaneous Devices") (part "Res3"))
    )
    (comp (ref "R10")
      (value "10K")
      (footprint "J1-0603")
      (description "Resistor")
      (fields (field (name "Comment") "Res3") (field (name "PUBLISHER") "Altium Limited"))
      (libsource (lib "Miscellaneous Devices") (part "Res3"))
    )
    (comp (ref "R11")
      (value "10K")
      (footprint "J1-0603")
      (description "Resistor")
      (fields (field (name "Comment") "Res3") (field (name "PUBLISHER") "Altium Limited"))
      (libsource (lib "Miscellaneous Devices") (part "Res3"))
    )
    (comp (ref "R12")
      (value "10K")
      (footprint "J1-0603")
      (description "Resistor")
      (fields (field (name "Comment") "Res3") (field (name "PUBLISHER") "Altium Limited"))
      (libsource (lib "Miscellaneous Devices") (part "Res3"))
    )
    (comp (ref "R13")
      (value "10K")
      (footprint "J1-0603")
      (description "Resistor")
      (fields (field (name "Comment") "Res3") (field (name "PUBLISHER") "Altium Limited"))
      (libsource (lib "Miscellaneous Devices") (part "Res3"))
    )
    (comp (ref "R14")
      (value "10K")
      (footprint "J1-0603")
      (description "Resistor")
      (fields (field (name "Comment") "Res3") (field (name "PUBLISHER") "Altium Limited"))
      (libsource (lib "Miscellaneous Devices") (part "Res3"))
    )
    (comp (ref "R15")
      (value "10K")
      (footprint "J1-0603")
      (description "Resistor")
      (fields (field (name "Comment") "Res3") (field (name "PUBLISHER") "Altium Limited"))
      (libsource (lib "Miscellaneous Devices") (part "Res3"))
    )
    (comp (ref "R16")
      (value "2.2k")
      (footprint "J1-0603")
      (description "Resistor")
      (fields (field (name "Comment") "Res3") (field (name "PUBLISHER") "Altium Limited"))
      (libsource (lib "Miscellaneous Devices") (part "Res3"))
    )
    (comp (ref "R17")
      (value "2.2k")
      (footprint "J1-0603")
      (description "Resistor")
      (fields (field (name "Comment") "Res3") (field (name "PUBLISHER") "Altium Limited"))
      (libsource (lib "Miscellaneous Devices") (part "Res3"))
    )
    (comp (ref "R18")
      (value "2.2K")
      (footprint "J1-0603")
      (description "Resistor")
      (fields (field (name "Comment") "Res3") (field (name "PUBLISHER") "Altium Limited"))
      (libsource (lib "Miscellaneous Devices") (part "Res3"))
    )
    (comp (ref "R19")
      (value "2.2K")
      (footprint "J1-0603")
      (description "Resistor")
      (fields (field (name "Comment") "Res3") (field (name "PUBLISHER") "Altium Limited"))
      (libsource (lib "Miscellaneous Devices") (part "Res3"))
    )
    (comp (ref "R20")
      (value "2.2K")
      (footprint "J1-0603")
      (description "Resistor")
      (fields (field (name "Comment") "Res3") (field (name "PUBLISHER") "Altium Limited"))
      (libsource (lib "Miscellaneous Devices") (part "Res3"))
    )
    (comp (ref "R21")
      (value "220")
      (footprint "J1-0603")
      (description "Resistor")
      (fields (field (name "Comment") "Res3") (field (name "PUBLISHER") "Altium Limited"))
      (libsource (lib "Miscellaneous Devices") (part "Res3"))
    )
    (comp (ref "R22")
      (value "220")
      (footprint "J1-0603")
      (description "Resistor")
      (fields (field (name "Comment") "Res3") (field (name "PUBLISHER") "Altium Limited"))
      (libsource (lib "Miscellaneous Devices") (part "Res3"))
    )
    (comp (ref "R23")
      (value "1.5K")
      (footprint "J1-0603")
      (description "Resistor")
      (fields (field (name "Comment") "Res3") (field (name "PUBLISHER") "Altium Limited"))
      (libsource (lib "Miscellaneous Devices") (part "Res3"))
    )
    (comp (ref "R24")
      (value "2K")
      (footprint "J1-0603")
      (description "Resistor")
      (fields (field (name "Comment") "Res3") (field (name "PUBLISHER") "Altium Limited"))
      (libsource (lib "Miscellaneous Devices") (part "Res3"))
    )
    (comp (ref "R25")
      (value "510K")
      (footprint "J1-0603")
      (description "Resistor")
      (fields (field (name "Comment") "Res3") (field (name "PUBLISHER") "Altium Limited"))
      (libsource (lib "Miscellaneous Devices") (part "Res3"))
    )
    (comp (ref "R26")
      (value "34K")
      (footprint "J1-0603")
      (description "Resistor")
      (fields (field (name "Comment") "Res3") (field (name "PUBLISHER") "Altium Limited"))
      (libsource (lib "Miscellaneous Devices") (part "Res3"))
    )
    (comp (ref "R27")
      (value "2.2K")
      (footprint "J1-0603")
      (description "Resistor")
      (fields (field (name "Comment") "Res3") (field (name "PUBLISHER") "Altium Limited"))
      (libsource (lib "Miscellaneous Devices") (part "Res3"))
    )
    (comp (ref "R28")
      (value "2.2K")
      (footprint "J1-0603")
      (description "Resistor")
      (fields (field (name "Comment") "Res3") (field (name "PUBLISHER") "Altium Limited"))
      (libsource (lib "Miscellaneous Devices") (part "Res3"))
    )
    (comp (ref "R29")
      (value "2.2K")
      (footprint "J1-0603")
      (description "Resistor")
      (fields (field (name "Comment") "Res3") (field (name "PUBLISHER") "Altium Limited"))
      (libsource (lib "Miscellaneous Devices") (part "Res3"))
    )
    (comp (ref "R30")
      (value "2.2K")
      (footprint "J1-0603")
      (description "Resistor")
      (fields (field (name "Comment") "Res3") (field (name "PUBLISHER") "Altium Limited"))
      (libsource (lib "Miscellaneous Devices") (part "Res3"))
    )
    (comp (ref "R31")
      (value "510K")
      (footprint "J1-0603")
      (description "Resistor")
      (fields (field (name "Comment") "Res3") (field (name "PUBLISHER") "Altium Limited"))
      (libsource (lib "Miscellaneous Devices") (part "Res3"))
    )
    (comp (ref "R32")
      (value "34K")
      (footprint "J1-0603")
      (description "Resistor")
      (fields (field (name "Comment") "Res3") (field (name "PUBLISHER") "Altium Limited"))
      (libsource (lib "Miscellaneous Devices") (part "Res3"))
    )
    (comp (ref "R33")
      (value "2K")
      (footprint "J1-0603")
      (description "Resistor")
      (fields (field (name "Comment") "Res3") (field (name "PUBLISHER") "Altium Limited"))
      (libsource (lib "Miscellaneous Devices") (part "Res3"))
    )
    (comp (ref "R34")
      (value "2.2K")
      (footprint "J1-0603")
      (description "Resistor")
      (fields (field (name "Comment") "Res3") (field (name "PUBLISHER") "Altium Limited"))
      (libsource (lib "Miscellaneous Devices") (part "Res3"))
    )
    (comp (ref "R35")
      (value "2.2K")
      (footprint "J1-0603")
      (description "Resistor")
      (fields (field (name "Comment") "Res3") (field (name "PUBLISHER") "Altium Limited"))
      (libsource (lib "Miscellaneous Devices") (part "Res3"))
    )
    (comp (ref "R36")
      (value "2.2K")
      (footprint "J1-0603")
      (description "Resistor")
      (fields (field (name "Comment") "Res3") (field (name "PUBLISHER") "Altium Limited"))
      (libsource (lib "Miscellaneous Devices") (part "Res3"))
    )
    (comp (ref "R37")
      (value "2.2K")
      (footprint "J1-0603")
      (description "Resistor")
      (fields (field (name "Comment") "Res3") (field (name "PUBLISHER") "Altium Limited"))
      (libsource (lib "Miscellaneous Devices") (part "Res3"))
    )
    (comp (ref "R38")
      (value "2.2K")
      (footprint "J1-0603")
      (description "Resistor")
      (fields (field (name "Comment") "Res3") (field (name "PUBLISHER") "Altium Limited"))
      (libsource (lib "Miscellaneous Devices") (part "Res3"))
    )
    (comp (ref "R39")
      (value "2.2K")
      (footprint "J1-0603")
      (description "Resistor")
      (fields (field (name "Comment") "Res3") (field (name "PUBLISHER") "Altium Limited"))
      (libsource (lib "Miscellaneous Devices") (part "Res3"))
    )
    (comp (ref "R40")
      (value "4.87K")
      (footprint "J1-0603")
      (description "Resistor")
      (fields (field (name "Comment") "Res3") (field (name "PUBLISHER") "Altium Limited"))
      (libsource (lib "Miscellaneous Devices") (part "Res3"))
    )
    (comp (ref "R41")
      (value "49.9")
      (footprint "J1-0603")
      (description "Resistor")
      (fields (field (name "Comment") "Res3") (field (name "PUBLISHER") "Altium Limited"))
      (libsource (lib "Miscellaneous Devices") (part "Res3"))
    )
    (comp (ref "R42")
      (value "49.9")
      (footprint "J1-0603")
      (description "Resistor")
      (fields (field (name "Comment") "Res3") (field (name "PUBLISHER") "Altium Limited"))
      (libsource (lib "Miscellaneous Devices") (part "Res3"))
    )
    (comp (ref "R43")
      (value "49.9")
      (footprint "J1-0603")
      (description "Resistor")
      (fields (field (name "Comment") "Res3") (field (name "PUBLISHER") "Altium Limited"))
      (libsource (lib "Miscellaneous Devices") (part "Res3"))
    )
    (comp (ref "R44")
      (value "49.9")
      (footprint "J1-0603")
      (description "Resistor")
      (fields (field (name "Comment") "Res3") (field (name "PUBLISHER") "Altium Limited"))
      (libsource (lib "Miscellaneous Devices") (part "Res3"))
    )
    (comp (ref "R45")
      (value "10K")
      (footprint "J1-0603")
      (description "Resistor")
      (fields (field (name "Comment") "Res3") (field (name "PUBLISHER") "Altium Limited"))
      (libsource (lib "Miscellaneous Devices") (part "Res3"))
    )
    (comp (ref "R46")
      (value "10K")
      (footprint "J1-0603")
      (description "Resistor")
      (fields (field (name "Comment") "Res3") (field (name "PUBLISHER") "Altium Limited"))
      (libsource (lib "Miscellaneous Devices") (part "Res3"))
    )
    (comp (ref "R47")
      (value "120")
      (footprint "J1-0603")
      (description "Resistor")
      (fields (field (name "Comment") "Res3") (field (name "PUBLISHER") "Altium Limited"))
      (libsource (lib "Miscellaneous Devices") (part "Res3"))
    )
    (comp (ref "R48")
      (value "52.3")
      (footprint "J1-0603")
      (description "Resistor")
      (fields (field (name "Comment") "Res3") (field (name "PUBLISHER") "Altium Limited"))
      (libsource (lib "Miscellaneous Devices") (part "Res3"))
    )
    (comp (ref "R49")
      (value "120")
      (footprint "J1-0603")
      (description "Resistor")
      (fields (field (name "Comment") "Res3") (field (name "PUBLISHER") "Altium Limited"))
      (libsource (lib "Miscellaneous Devices") (part "Res3"))
    )
    (comp (ref "R50")
      (value "365")
      (footprint "J1-0603")
      (description "Resistor")
      (fields (field (name "Comment") "Res3") (field (name "PUBLISHER") "Altium Limited"))
      (libsource (lib "Miscellaneous Devices") (part "Res3"))
    )
    (comp (ref "R51")
      (value "120")
      (footprint "J1-0603")
      (description "Resistor")
      (fields (field (name "Comment") "Res3") (field (name "PUBLISHER") "Altium Limited"))
      (libsource (lib "Miscellaneous Devices") (part "Res3"))
    )
    (comp (ref "R52")
      (value "196")
      (footprint "J1-0603")
      (description "Resistor")
      (fields (field (name "Comment") "Res3") (field (name "PUBLISHER") "Altium Limited"))
      (libsource (lib "Miscellaneous Devices") (part "Res3"))
    )
    (comp (ref "R53")
      (value "120")
      (footprint "J1-0603")
      (description "Resistor")
      (fields (field (name "Comment") "Res3") (field (name "PUBLISHER") "Altium Limited"))
      (libsource (lib "Miscellaneous Devices") (part "Res3"))
    )
    (comp (ref "R54")
      (value "169")
      (footprint "J1-0603")
      (description "Resistor")
      (fields (field (name "Comment") "Res3") (field (name "PUBLISHER") "Altium Limited"))
      (libsource (lib "Miscellaneous Devices") (part "Res3"))
    )
    (comp (ref "R55")
      (value "0")
      (footprint "J1-0603")
      (description "Resistor")
      (fields (field (name "Comment") "Res3") (field (name "PUBLISHER") "Altium Limited"))
      (libsource (lib "Miscellaneous Devices") (part "Res3"))
    )
    (comp (ref "R56")
      (value "0")
      (footprint "J1-0603")
      (description "Resistor")
      (fields (field (name "Comment") "Res3") (field (name "PUBLISHER") "Altium Limited"))
      (libsource (lib "Miscellaneous Devices") (part "Res3"))
    )
    (comp (ref "R57")
      (value "0")
      (footprint "J1-0603")
      (description "Resistor")
      (fields (field (name "Comment") "Res3") (field (name "PUBLISHER") "Altium Limited"))
      (libsource (lib "Miscellaneous Devices") (part "Res3"))
    )
    (comp (ref "R58")
      (value "1W")
      (footprint "RESC6332")
      (description "MCR100JZHJ2R2")
      (fields (field (name "ALTIUM_VALUE") "2.2") (field (name "PUBLISHER") "Altium Limited"))
      (libsource (lib "Miscellaneous Devices") (part "Res3"))
    )
    (comp (ref "R59")
      (value "2.2K")
      (footprint "J1-0603")
      (description "Resistor")
      (fields (field (name "Comment") "Res3") (field (name "PUBLISHER") "Altium Limited"))
      (libsource (lib "Miscellaneous Devices") (part "Res3"))
    )
    (comp (ref "R60")
      (value "1W")
      (footprint "RESC6332")
      (description "MCR100JZHJ2R2")
      (fields (field (name "ALTIUM_VALUE") "2.2") (field (name "PUBLISHER") "Altium Limited"))
      (libsource (lib "Miscellaneous Devices") (part "Res3"))
    )
    (comp (ref "R61")
      (value "1W")
      (footprint "RESC6332")
      (description "MCR100JZHJ2R2")
      (fields (field (name "ALTIUM_VALUE") "2.2") (field (name "PUBLISHER") "Altium Limited"))
      (libsource (lib "Miscellaneous Devices") (part "Res3"))
    )
    (comp (ref "R62")
      (value "1W")
      (footprint "RESC6332")
      (description "MCR100JZHJ2R2")
      (fields (field (name "ALTIUM_VALUE") "2.2") (field (name "PUBLISHER") "Altium Limited"))
      (libsource (lib "Miscellaneous Devices") (part "Res3"))
    )
    (comp (ref "R63")
      (value "2.2k")
      (footprint "J1-0603")
      (description "Resistor")
      (fields (field (name "Comment") "Res3") (field (name "PUBLISHER") "Altium Limited"))
      (libsource (lib "Miscellaneous Devices") (part "Res3"))
    )
    (comp (ref "R64")
      (value "2.2k")
      (footprint "J1-0603")
      (description "Resistor")
      (fields (field (name "Comment") "Res3") (field (name "PUBLISHER") "Altium Limited"))
      (libsource (lib "Miscellaneous Devices") (part "Res3"))
    )
    (comp (ref "R65")
      (value "1k")
      (footprint "J1-0603")
      (description "Resistor")
      (fields (field (name "Comment") "Res3") (field (name "PUBLISHER") "Altium Limited"))
      (libsource (lib "Miscellaneous Devices") (part "Res3"))
    )
    (comp (ref "R66")
      (value "100k")
      (footprint "J1-0603")
      (description "Resistor")
      (fields (field (name "Comment") "Res3") (field (name "PUBLISHER") "Altium Limited"))
      (libsource (lib "Miscellaneous Devices") (part "Res3"))
    )
    (comp (ref "R67")
      (value "1k")
      (footprint "J1-0603")
      (description "Resistor")
      (fields (field (name "Comment") "Res3") (field (name "PUBLISHER") "Altium Limited"))
      (libsource (lib "Miscellaneous Devices") (part "Res3"))
    )
    (comp (ref "R68")
      (value "1k")
      (footprint "J1-0603")
      (description "Resistor")
      (fields (field (name "Comment") "Res3") (field (name "PUBLISHER") "Altium Limited"))
      (libsource (lib "Miscellaneous Devices") (part "Res3"))
    )
    (comp (ref "R69")
      (value "330")
      (footprint "J1-0603")
      (description "Resistor")
      (fields (field (name "Comment") "Res3") (field (name "PUBLISHER") "Altium Limited"))
      (libsource (lib "Miscellaneous Devices") (part "Res3"))
    )
    (comp (ref "R70")
      (value "150")
      (footprint "J1-0603")
      (description "Resistor")
      (fields (field (name "Comment") "Res3") (field (name "PUBLISHER") "Altium Limited"))
      (libsource (lib "Miscellaneous Devices") (part "Res3"))
    )
    (comp (ref "REG_1V8")
      (value "LM1086-ADJ")
      (footprint "TO-220V")
      (description "1.5A Low Dropout Positive Regulator")
      (libsource (lib "eecs5x") (part "LM1086"))
    )
    (comp (ref "REG_3V")
      (value "LM1086-ADJ")
      (footprint "TO-220V")
      (description "1.5A Low Dropout Positive Regulator")
      (libsource (lib "eecs5x") (part "LM1086"))
    )
    (comp (ref "REG_3V3")
      (value "LM1086-ADJ")
      (footprint "TO-220V")
      (description "1.5A Low Dropout Positive Regulator")
      (libsource (lib "eecs5x") (part "LM1086"))
    )
    (comp (ref "REG_5V")
      (value "LM1086-ADJ")
      (footprint "TO-220V")
      (description "1.5A Low Dropout Positive Regulator")
      (libsource (lib "eecs5x") (part "LM1086"))
    )
    (comp (ref "SW_HANGUP")
      (value "KS01Q01")
      (footprint "KS01Q01")
      (libsource (lib "EEW_Client") (part "KS01Q01"))
    )
    (comp (ref "SW_RESET")
      (value "KS01Q01")
      (footprint "KS01Q01")
      (libsource (lib "EEW_Client") (part "KS01Q01"))
    )
    (comp (ref "U1")
      (value "AT91RM9200")
      (footprint "PQFP208")
      (description "Atmel ARM")
      (libsource (lib "eecs5x") (part "AT91RM9200"))
    )
    (comp (ref "U2")
      (value "74LVT16245")
      (footprint "TSSOP48")
      (description "16-Bit Bus Transceiver")
      (libsource (lib "eecs5x") (part "74LVT16245"))
    )
    (comp (ref "U3")
      (value "MAX705")
      (footprint "DIPS8")
      (description "Maxim uP Supervisory Circuit")
      (libsource (lib "eecs5x") (part "MAX705"))
    )
    (comp (ref "U4")
      (value "74LVT16245")
      (footprint "TSSOP48")
      (description "16-Bit Bus Transceiver")
      (libsource (lib "eecs5x") (part "74LVT16245"))
    )
    (comp (ref "U5")
      (value "ISPLSI1016E")
      (footprint "PLCCS44")
      (description "In-System Programmable High Density CPLD")
      (libsource (lib "eecs5x") (part "ISPLSI1016E"))
    )
    (comp (ref "U6")
      (value "SRAM IDT71V016")
      (footprint "SSOP44.400")
      (description "64K x 16 3.3V Static CMOS RAM")
      (libsource (lib "eecs5x") (part "IDT71V016"))
    )
    (comp (ref "U7")
      (value "ROM 29LV040")
      (footprint "PLCCS32")
      (description "4 Megabit (512K x 8) CMOS Uniform Sector Flash Memory")
      (libsource (lib "eecs5x") (part "29LV040"))
    )
    (comp (ref "U8")
      (value "74LVT16245")
      (footprint "TSSOP48")
      (description "16-Bit Bus Transceiver")
      (libsource (lib "eecs5x") (part "74LVT16245"))
    )
    (comp (ref "U9")
      (value "TI-CD40109B-16")
      (footprint "TI-PW16_M")
      (libsource (lib "CD40109") (part "TI-CD40109B-16"))
    )
    (comp (ref "U11")
      (value "TI-CD40109B-16")
      (footprint "TI-PW16_M")
      (libsource (lib "CD40109") (part "TI-CD40109B-16"))
    )
    (comp (ref "U13")
      (value "MM74C923")
      (footprint "DIPS20")
      (description "20-Key Encoder")
      (libsource (lib "eecs5x") (part "MM74C923"))
    )
    (comp (ref "U15")
      (value "24AA32")
      (footprint "DIPS8")
      (description "I2C Serial EEPROM")
      (libsource (lib "eecs5x") (part "24AA32"))
    )
    (comp (ref "U16")
      (value "DP83848")
      (footprint "LQFP48")
      (description "PHYTER - Single Port 10/100 Mb/s Ethernet Physical Layer Transceiver")
      (libsource (lib "eecs5x") (part "DP83848"))
    )
    (comp (ref "U17")
      (value "TLV320AIC1106")
      (footprint "PSOP20")
      (description "PCM Codec")
      (libsource (lib "eecs5x") (part "TLV320AIC1106"))
    )
    (comp (ref "U18")
      (value "74LVT16245")
      (footprint "TSSOP48")
      (description "16-Bit Bus Transceiver")
      (libsource (lib "eecs5x") (part "74LVT16245"))
    )
    (comp (ref "U19")
      (value "74LVT16245")
      (footprint "TSSOP48")
      (description "16-Bit Bus Transceiver")
      (libsource (lib "eecs5x") (part "74LVT16245"))
    )
    (comp (ref "U20")
      (value "DRAM1MX8")
      (footprint "SIMM30")
      (description "1M x 8 DRAM SIMM")
      (libsource (lib "eecs5x") (part "DRAM1MX8"))
    )
    (comp (ref "U21")
      (value "74LVT16245")
      (footprint "TSSOP48")
      (description "16-Bit Bus Transceiver")
      (libsource (lib "eecs5x") (part "74LVT16245"))
    )
    (comp (ref "X1")
      (value "20 MHz")
      (footprint "HC-49U")
      (description "Crystal")
      (libsource (lib "eecs5x") (part "CRYSTAL"))
    )
    (comp (ref "X2")
      (value "32.768 kHz")
      (footprint "FX-3")
      (description "Crystal")
      (libsource (lib "eecs5x") (part "CRYSTAL"))
    )
    (comp (ref "X3")
      (value "25 MHz")
      (footprint "HC-49U")
      (description "Crystal")
      (libsource (lib "eecs5x") (part "CRYSTAL"))
    )
  )
  (nets
    (net (code "1") (name "/AUD_VDD") (class "Default")
      (node (ref "C73") (pin "2") (pinfunction "2_2") (pintype "passive"))
      (node (ref "L1") (pin "1") (pinfunction "1_1") (pintype "passive"))
      (node (ref "R24") (pin "2") (pinfunction "2_2") (pintype "passive"))
      (node (ref "U17") (pin "6") (pinfunction "EARVDD_6") (pintype "power_in"))
    )
    (net (code "2") (name "/AUD_VSS") (class "Default")
      (node (ref "C73") (pin "1") (pinfunction "1_1") (pintype "passive"))
      (node (ref "L2") (pin "1") (pinfunction "1_1") (pintype "passive"))
      (node (ref "R33") (pin "1") (pinfunction "1_1") (pintype "passive"))
      (node (ref "U17") (pin "3") (pinfunction "AGND_3") (pintype "power_in"))
      (node (ref "U17") (pin "4") (pinfunction "EARVSS_4") (pintype "power_in"))
      (node (ref "U17") (pin "8") (pinfunction "EARVSS_8") (pintype "power_in"))
    )
    (net (code "3") (name "/A_3V3_Buf_0") (class "Default")
      (node (ref "P7") (pin "1") (pinfunction "1_1") (pintype "passive"))
      (node (ref "U2") (pin "2") (pinfunction "1B1_2") (pintype "bidirectional"))
      (node (ref "U6") (pin "39") (pinfunction "BLE_39") (pintype "input"))
      (node (ref "U7") (pin "12") (pinfunction "A0_12") (pintype "input"))
    )
    (net (code "4") (name "/A_3V3_Buf_1") (class "Default")
      (node (ref "P7") (pin "2") (pinfunction "2_2") (pintype "passive"))
      (node (ref "U2") (pin "3") (pinfunction "1B2_3") (pintype "bidirectional"))
      (node (ref "U6") (pin "5") (pinfunction "A0_5") (pintype "input"))
      (node (ref "U7") (pin "11") (pinfunction "A1_11") (pintype "input"))
    )
    (net (code "5") (name "/A_3V3_Buf_2") (class "Default")
      (node (ref "P7") (pin "3") (pinfunction "3_3") (pintype "passive"))
      (node (ref "U2") (pin "5") (pinfunction "1B3_5") (pintype "bidirectional"))
      (node (ref "U6") (pin "4") (pinfunction "A1_4") (pintype "input"))
      (node (ref "U7") (pin "10") (pinfunction "A2_10") (pintype "input"))
    )
    (net (code "6") (name "/A_3V3_Buf_3") (class "Default")
      (node (ref "P7") (pin "4") (pinfunction "4_4") (pintype "passive"))
      (node (ref "U2") (pin "6") (pinfunction "1B4_6") (pintype "bidirectional"))
      (node (ref "U6") (pin "3") (pinfunction "A2_3") (pintype "input"))
      (node (ref "U7") (pin "9") (pinfunction "A3_9") (pintype "input"))
    )
    (net (code "7") (name "/A_3V3_Buf_4") (class "Default")
      (node (ref "P7") (pin "5") (pinfunction "5_5") (pintype "passive"))
      (node (ref "U2") (pin "8") (pinfunction "1B5_8") (pintype "bidirectional"))
      (node (ref "U6") (pin "2") (pinfunction "A3_2") (pintype "input"))
      (node (ref "U7") (pin "8") (pinfunction "A4_8") (pintype "input"))
    )
    (net (code "8") (name "/A_3V3_Buf_5") (class "Default")
      (node (ref "P7") (pin "6") (pinfunction "6_6") (pintype "passive"))
      (node (ref "U2") (pin "9") (pinfunction "1B6_9") (pintype "bidirectional"))
      (node (ref "U6") (pin "1") (pinfunction "A4_1") (pintype "input"))
      (node (ref "U7") (pin "7") (pinfunction "A5_7") (pintype "input"))
    )
    (net (code "9") (name "/A_3V3_Buf_6") (class "Default")
      (node (ref "P7") (pin "7") (pinfunction "7_7") (pintype "passive"))
      (node (ref "U2") (pin "11") (pinfunction "1B7_11") (pintype "bidirectional"))
      (node (ref "U6") (pin "44") (pinfunction "A5_44") (pintype "input"))
      (node (ref "U7") (pin "6") (pinfunction "A6_6") (pintype "input"))
    )
    (net (code "10") (name "/A_3V3_Buf_7") (class "Default")
      (node (ref "P7") (pin "8") (pinfunction "8_8") (pintype "passive"))
      (node (ref "U2") (pin "12") (pinfunction "1B8_12") (pintype "bidirectional"))
      (node (ref "U6") (pin "43") (pinfunction "A6_43") (pintype "input"))
      (node (ref "U7") (pin "5") (pinfunction "A7_5") (pintype "input"))
    )
    (net (code "11") (name "/A_3V3_Buf_8") (class "Default")
      (node (ref "P7") (pin "9") (pinfunction "9_9") (pintype "passive"))
      (node (ref "U2") (pin "13") (pinfunction "2B1_13") (pintype "bidirectional"))
      (node (ref "U6") (pin "42") (pinfunction "A7_42") (pintype "input"))
      (node (ref "U7") (pin "27") (pinfunction "A8_27") (pintype "input"))
    )
    (net (code "12") (name "/A_3V3_Buf_9") (class "Default")
      (node (ref "P7") (pin "10") (pinfunction "10_10") (pintype "passive"))
      (node (ref "U2") (pin "14") (pinfunction "2B2_14") (pintype "bidirectional"))
      (node (ref "U6") (pin "27") (pinfunction "A8_27") (pintype "input"))
      (node (ref "U7") (pin "26") (pinfunction "A9_26") (pintype "input"))
    )
    (net (code "13") (name "/A_3V3_Buf_10") (class "Default")
      (node (ref "P7") (pin "11") (pinfunction "11_11") (pintype "passive"))
      (node (ref "U2") (pin "16") (pinfunction "2B3_16") (pintype "bidirectional"))
      (node (ref "U6") (pin "26") (pinfunction "A9_26") (pintype "input"))
      (node (ref "U7") (pin "23") (pinfunction "A10_23") (pintype "input"))
    )
    (net (code "14") (name "/A_3V3_Buf_11") (class "Default")
      (node (ref "P7") (pin "12") (pinfunction "12_12") (pintype "passive"))
      (node (ref "U2") (pin "17") (pinfunction "2B4_17") (pintype "bidirectional"))
      (node (ref "U6") (pin "25") (pinfunction "A10_25") (pintype "input"))
      (node (ref "U7") (pin "25") (pinfunction "A11_25") (pintype "input"))
    )
    (net (code "15") (name "/A_3V3_Buf_12") (class "Default")
      (node (ref "P7") (pin "13") (pinfunction "13_13") (pintype "passive"))
      (node (ref "U2") (pin "19") (pinfunction "2B5_19") (pintype "bidirectional"))
      (node (ref "U6") (pin "24") (pinfunction "A11_24") (pintype "input"))
      (node (ref "U7") (pin "4") (pinfunction "A12_4") (pintype "input"))
    )
    (net (code "16") (name "/A_3V3_Buf_13") (class "Default")
      (node (ref "P7") (pin "14") (pinfunction "14_14") (pintype "passive"))
      (node (ref "U2") (pin "20") (pinfunction "2B6_20") (pintype "bidirectional"))
      (node (ref "U6") (pin "21") (pinfunction "A12_21") (pintype "input"))
      (node (ref "U7") (pin "28") (pinfunction "A13_28") (pintype "input"))
    )
    (net (code "17") (name "/A_3V3_Buf_14") (class "Default")
      (node (ref "P7") (pin "15") (pinfunction "15_15") (pintype "passive"))
      (node (ref "U2") (pin "22") (pinfunction "2B7_22") (pintype "bidirectional"))
      (node (ref "U6") (pin "20") (pinfunction "A13_20") (pintype "input"))
      (node (ref "U7") (pin "29") (pinfunction "A14_29") (pintype "input"))
    )
    (net (code "18") (name "/A_3V3_Buf_15") (class "Default")
      (node (ref "P7") (pin "16") (pinfunction "16_16") (pintype "passive"))
      (node (ref "U2") (pin "23") (pinfunction "2B8_23") (pintype "bidirectional"))
      (node (ref "U6") (pin "19") (pinfunction "A14_19") (pintype "input"))
      (node (ref "U7") (pin "3") (pinfunction "A15_3") (pintype "input"))
    )
    (net (code "19") (name "/A_3V3_Buf_16") (class "Default")
      (node (ref "U6") (pin "18") (pinfunction "A15_18") (pintype "input"))
      (node (ref "U7") (pin "2") (pinfunction "A16_2") (pintype "input"))
      (node (ref "U8") (pin "8") (pinfunction "1B5_8") (pintype "bidirectional"))
    )
    (net (code "20") (name "/A_3V3_Buf_17") (class "Default")
      (node (ref "U7") (pin "30") (pinfunction "A17_30") (pintype "input"))
      (node (ref "U8") (pin "9") (pinfunction "1B6_9") (pintype "bidirectional"))
    )
    (net (code "21") (name "/A_3V3_Buf_18") (class "Default")
      (node (ref "U7") (pin "1") (pinfunction "A18_1") (pintype "input"))
      (node (ref "U8") (pin "11") (pinfunction "1B7_11") (pintype "bidirectional"))
    )
    (net (code "22") (name "/A_3V3_Buf_19") (class "Default")
      (node (ref "U8") (pin "12") (pinfunction "1B8_12") (pintype "bidirectional"))
    )
    (net (code "24") (name "/A_5V_0") (class "Default")
      (node (ref "U19") (pin "2") (pinfunction "1B1_2") (pintype "bidirectional"))
      (node (ref "U20") (pin "4") (pinfunction "A0_4") (pintype "input"))
      (node (ref "U21") (pin "2") (pinfunction "1B1_2") (pintype "bidirectional"))
    )
    (net (code "25") (name "/A_5V_1") (class "Default")
      (node (ref "U19") (pin "3") (pinfunction "1B2_3") (pintype "bidirectional"))
      (node (ref "U20") (pin "5") (pinfunction "A1_5") (pintype "input"))
      (node (ref "U21") (pin "3") (pinfunction "1B2_3") (pintype "bidirectional"))
    )
    (net (code "26") (name "/A_5V_2") (class "Default")
      (node (ref "U19") (pin "5") (pinfunction "1B3_5") (pintype "bidirectional"))
      (node (ref "U20") (pin "7") (pinfunction "A2_7") (pintype "input"))
      (node (ref "U21") (pin "5") (pinfunction "1B3_5") (pintype "bidirectional"))
    )
    (net (code "27") (name "/A_5V_3") (class "Default")
      (node (ref "U19") (pin "6") (pinfunction "1B4_6") (pintype "bidirectional"))
      (node (ref "U20") (pin "8") (pinfunction "A3_8") (pintype "input"))
      (node (ref "U21") (pin "6") (pinfunction "1B4_6") (pintype "bidirectional"))
    )
    (net (code "28") (name "/A_5V_4") (class "Default")
      (node (ref "U19") (pin "8") (pinfunction "1B5_8") (pintype "bidirectional"))
      (node (ref "U20") (pin "11") (pinfunction "A4_11") (pintype "input"))
      (node (ref "U21") (pin "8") (pinfunction "1B5_8") (pintype "bidirectional"))
    )
    (net (code "29") (name "/A_5V_5") (class "Default")
      (node (ref "U19") (pin "9") (pinfunction "1B6_9") (pintype "bidirectional"))
      (node (ref "U20") (pin "12") (pinfunction "A5_12") (pintype "input"))
      (node (ref "U21") (pin "9") (pinfunction "1B6_9") (pintype "bidirectional"))
    )
    (net (code "30") (name "/A_5V_6") (class "Default")
      (node (ref "U19") (pin "11") (pinfunction "1B7_11") (pintype "bidirectional"))
      (node (ref "U20") (pin "14") (pinfunction "A6_14") (pintype "input"))
      (node (ref "U21") (pin "11") (pinfunction "1B7_11") (pintype "bidirectional"))
    )
    (net (code "31") (name "/A_5V_7") (class "Default")
      (node (ref "U19") (pin "12") (pinfunction "1B8_12") (pintype "bidirectional"))
      (node (ref "U20") (pin "15") (pinfunction "A7_15") (pintype "input"))
      (node (ref "U21") (pin "12") (pinfunction "1B8_12") (pintype "bidirectional"))
    )
    (net (code "32") (name "/A_5V_8") (class "Default")
      (node (ref "U19") (pin "13") (pinfunction "2B1_13") (pintype "bidirectional"))
      (node (ref "U20") (pin "17") (pinfunction "A8_17") (pintype "input"))
      (node (ref "U21") (pin "13") (pinfunction "2B1_13") (pintype "bidirectional"))
    )
    (net (code "33") (name "/A_5V_9") (class "Default")
      (node (ref "U19") (pin "14") (pinfunction "2B2_14") (pintype "bidirectional"))
      (node (ref "U20") (pin "18") (pinfunction "A9_18") (pintype "input"))
      (node (ref "U21") (pin "14") (pinfunction "2B2_14") (pintype "bidirectional"))
    )
    (net (code "34") (name "/Addr0") (class "Default")
      (node (ref "U1") (pin "133") (pinfunction "A0/NBS0_133") (pintype "output"))
      (node (ref "U19") (pin "47") (pinfunction "1A1_47") (pintype "bidirectional"))
      (node (ref "U2") (pin "47") (pinfunction "1A1_47") (pintype "bidirectional"))
    )
    (net (code "35") (name "/Addr1") (class "Default")
      (node (ref "U1") (pin "134") (pinfunction "A1/NBS2/NWR2_134") (pintype "output"))
      (node (ref "U19") (pin "46") (pinfunction "1A2_46") (pintype "bidirectional"))
      (node (ref "U2") (pin "46") (pinfunction "1A2_46") (pintype "bidirectional"))
    )
    (net (code "36") (name "/Addr2") (class "Default")
      (node (ref "U1") (pin "135") (pinfunction "A2_135") (pintype "output"))
      (node (ref "U19") (pin "44") (pinfunction "1A3_44") (pintype "bidirectional"))
      (node (ref "U2") (pin "44") (pinfunction "1A3_44") (pintype "bidirectional"))
    )
    (net (code "37") (name "/Addr3") (class "Default")
      (node (ref "U1") (pin "136") (pinfunction "A3_136") (pintype "output"))
      (node (ref "U19") (pin "43") (pinfunction "1A4_43") (pintype "bidirectional"))
      (node (ref "U2") (pin "43") (pinfunction "1A4_43") (pintype "bidirectional"))
    )
    (net (code "38") (name "/Addr4") (class "Default")
      (node (ref "U1") (pin "137") (pinfunction "A4_137") (pintype "output"))
      (node (ref "U19") (pin "41") (pinfunction "1A5_41") (pintype "bidirectional"))
      (node (ref "U2") (pin "41") (pinfunction "1A5_41") (pintype "bidirectional"))
    )
    (net (code "39") (name "/Addr5") (class "Default")
      (node (ref "U1") (pin "138") (pinfunction "A5_138") (pintype "output"))
      (node (ref "U19") (pin "40") (pinfunction "1A6_40") (pintype "bidirectional"))
      (node (ref "U2") (pin "40") (pinfunction "1A6_40") (pintype "bidirectional"))
    )
    (net (code "40") (name "/Addr6") (class "Default")
      (node (ref "U1") (pin "139") (pinfunction "A6_139") (pintype "output"))
      (node (ref "U19") (pin "38") (pinfunction "1A7_38") (pintype "bidirectional"))
      (node (ref "U2") (pin "38") (pinfunction "1A7_38") (pintype "bidirectional"))
    )
    (net (code "41") (name "/Addr7") (class "Default")
      (node (ref "U1") (pin "140") (pinfunction "A7_140") (pintype "output"))
      (node (ref "U19") (pin "37") (pinfunction "1A8_37") (pintype "bidirectional"))
      (node (ref "U2") (pin "37") (pinfunction "1A8_37") (pintype "bidirectional"))
    )
    (net (code "42") (name "/Addr8") (class "Default")
      (node (ref "U1") (pin "141") (pinfunction "A8_141") (pintype "output"))
      (node (ref "U19") (pin "36") (pinfunction "2A1_36") (pintype "bidirectional"))
      (node (ref "U2") (pin "36") (pinfunction "2A1_36") (pintype "bidirectional"))
    )
    (net (code "43") (name "/Addr9") (class "Default")
      (node (ref "U1") (pin "142") (pinfunction "A9_142") (pintype "output"))
      (node (ref "U19") (pin "35") (pinfunction "2A2_35") (pintype "bidirectional"))
      (node (ref "U2") (pin "35") (pinfunction "2A2_35") (pintype "bidirectional"))
    )
    (net (code "44") (name "/Addr10") (class "Default")
      (node (ref "U1") (pin "143") (pinfunction "A10_143") (pintype "output"))
      (node (ref "U2") (pin "33") (pinfunction "2A3_33") (pintype "bidirectional"))
      (node (ref "U21") (pin "47") (pinfunction "1A1_47") (pintype "bidirectional"))
    )
    (net (code "45") (name "/Addr11") (class "Default")
      (node (ref "U1") (pin "145") (pinfunction "A11_145") (pintype "output"))
      (node (ref "U2") (pin "32") (pinfunction "2A4_32") (pintype "bidirectional"))
      (node (ref "U21") (pin "46") (pinfunction "1A2_46") (pintype "bidirectional"))
    )
    (net (code "46") (name "/Addr12") (class "Default")
      (node (ref "U1") (pin "148") (pinfunction "A12_148") (pintype "output"))
      (node (ref "U2") (pin "30") (pinfunction "2A5_30") (pintype "bidirectional"))
      (node (ref "U21") (pin "44") (pinfunction "1A3_44") (pintype "bidirectional"))
    )
    (net (code "47") (name "/Addr13") (class "Default")
      (node (ref "U1") (pin "149") (pinfunction "A13_149") (pintype "output"))
      (node (ref "U2") (pin "29") (pinfunction "2A6_29") (pintype "bidirectional"))
      (node (ref "U21") (pin "43") (pinfunction "1A4_43") (pintype "bidirectional"))
    )
    (net (code "48") (name "/Addr14") (class "Default")
      (node (ref "U1") (pin "150") (pinfunction "A14_150") (pintype "output"))
      (node (ref "U2") (pin "27") (pinfunction "2A7_27") (pintype "bidirectional"))
      (node (ref "U21") (pin "41") (pinfunction "1A5_41") (pintype "bidirectional"))
    )
    (net (code "49") (name "/Addr15") (class "Default")
      (node (ref "U1") (pin "151") (pinfunction "A15_151") (pintype "output"))
      (node (ref "U2") (pin "26") (pinfunction "2A8_26") (pintype "bidirectional"))
      (node (ref "U21") (pin "40") (pinfunction "1A6_40") (pintype "bidirectional"))
    )
    (net (code "50") (name "/Addr16") (class "Default")
      (node (ref "U1") (pin "154") (pinfunction "A16/BA0_154") (pintype "output"))
      (node (ref "U21") (pin "38") (pinfunction "1A7_38") (pintype "bidirectional"))
      (node (ref "U8") (pin "41") (pinfunction "1A5_41") (pintype "bidirectional"))
    )
    (net (code "51") (name "/Addr17") (class "Default")
      (node (ref "U1") (pin "155") (pinfunction "A17/BA1_155") (pintype "output"))
      (node (ref "U21") (pin "37") (pinfunction "1A8_37") (pintype "bidirectional"))
      (node (ref "U8") (pin "40") (pinfunction "1A6_40") (pintype "bidirectional"))
    )
    (net (code "52") (name "/Addr18") (class "Default")
      (node (ref "U1") (pin "156") (pinfunction "A18_156") (pintype "output"))
      (node (ref "U21") (pin "36") (pinfunction "2A1_36") (pintype "bidirectional"))
      (node (ref "U8") (pin "38") (pinfunction "1A7_38") (pintype "bidirectional"))
    )
    (net (code "53") (name "/Addr19") (class "Default")
      (node (ref "U1") (pin "157") (pinfunction "A19_157") (pintype "output"))
      (node (ref "U21") (pin "35") (pinfunction "2A2_35") (pintype "bidirectional"))
      (node (ref "U8") (pin "37") (pinfunction "1A8_37") (pintype "bidirectional"))
    )
    (net (code "55") (name "/BTN_HangUp") (class "Default")
      (node (ref "R15") (pin "1") (pinfunction "1_1") (pintype "passive"))
      (node (ref "SW_HANGUP") (pin "1") (pintype "passive"))
      (node (ref "U1") (pin "1") (pinfunction "PC24/D24_1") (pintype "bidirectional"))
    )
    (net (code "56") (name "/CAS") (class "Default")
      (node (ref "P6") (pin "10") (pinfunction "10_10") (pintype "passive"))
      (node (ref "R56") (pin "2") (pinfunction "2_2") (pintype "passive"))
      (node (ref "U5") (pin "19") (pinfunction "I/O4_19") (pintype "bidirectional"))
    )
    (net (code "57") (name "/COL_ADDR_EN") (class "Default")
      (node (ref "P6") (pin "16") (pinfunction "16_16") (pintype "passive"))
      (node (ref "R46") (pin "1") (pinfunction "1_1") (pintype "passive"))
      (node (ref "U21") (pin "25") (pinfunction "2OE_25") (pintype "input"))
      (node (ref "U21") (pin "48") (pinfunction "1OE_48") (pintype "input"))
      (node (ref "U5") (pin "22") (pinfunction "I/O7_22") (pintype "bidirectional"))
    )
    (net (code "58") (name "/DISP_A0") (class "Default")
      (node (ref "U1") (pin "46") (pinfunction "PA4/NPCS1/PCK1_46") (pintype "bidirectional"))
      (node (ref "U9") (pin "3") (pinfunction "A_3") (pintype "input"))
    )
    (net (code "59") (name "/DISP_BCKLIGHT") (class "Default")
      (node (ref "Q2") (pin "G") (pinfunction "G_G") (pintype "passive"))
      (node (ref "U1") (pin "47") (pinfunction "PA5/NPCS2/TXD3_47") (pintype "bidirectional"))
    )
    (net (code "60") (name "/DISP_CS") (class "Default")
      (node (ref "U1") (pin "45") (pinfunction "PA3/NPCS0/IRQ5_45") (pintype "bidirectional"))
      (node (ref "U9") (pin "10") (pinfunction "C_10") (pintype "input"))
    )
    (net (code "61") (name "/DISP_MOSI") (class "Default")
      (node (ref "U1") (pin "43") (pinfunction "PA1/MOSI/PCK0_43") (pintype "bidirectional"))
      (node (ref "U11") (pin "10") (pinfunction "C_10") (pintype "input"))
    )
    (net (code "62") (name "/DISP_RST") (class "Default")
      (node (ref "U1") (pin "48") (pinfunction "PA6/NPCS3/RXD3_48") (pintype "bidirectional"))
      (node (ref "U9") (pin "6") (pinfunction "B_6") (pintype "input"))
    )
    (net (code "63") (name "/DISP_SCK") (class "Default")
      (node (ref "U1") (pin "44") (pinfunction "PA2/SPCK/IRQ4_44") (pintype "bidirectional"))
      (node (ref "U11") (pin "14") (pinfunction "D_14") (pintype "input"))
    )
    (net (code "64") (name "/DRAM_WE") (class "Default")
      (node (ref "P6") (pin "12") (pinfunction "12_12") (pintype "passive"))
      (node (ref "U20") (pin "21") (pinfunction "WE_21") (pintype "input"))
      (node (ref "U5") (pin "20") (pinfunction "I/O5_20") (pintype "bidirectional"))
    )
    (net (code "65") (name "/D_3V3B0") (class "Default")
      (node (ref "P4") (pin "2") (pinfunction "2_2") (pintype "passive"))
      (node (ref "U18") (pin "47") (pinfunction "1A1_47") (pintype "bidirectional"))
      (node (ref "U4") (pin "2") (pinfunction "1B1_2") (pintype "bidirectional"))
      (node (ref "U6") (pin "7") (pinfunction "IO0_7") (pintype "bidirectional"))
      (node (ref "U7") (pin "13") (pinfunction "DQ1_13") (pintype "bidirectional"))
    )
    (net (code "66") (name "/D_3V3B1") (class "Default")
      (node (ref "P4") (pin "1") (pinfunction "1_1") (pintype "passive"))
      (node (ref "U18") (pin "46") (pinfunction "1A2_46") (pintype "bidirectional"))
      (node (ref "U4") (pin "3") (pinfunction "1B2_3") (pintype "bidirectional"))
      (node (ref "U6") (pin "8") (pinfunction "IO1_8") (pintype "bidirectional"))
      (node (ref "U7") (pin "14") (pinfunction "DQ2_14") (pintype "bidirectional"))
    )
    (net (code "67") (name "/D_3V3B2") (class "Default")
      (node (ref "P4") (pin "4") (pinfunction "4_4") (pintype "passive"))
      (node (ref "U18") (pin "44") (pinfunction "1A3_44") (pintype "bidirectional"))
      (node (ref "U4") (pin "5") (pinfunction "1B3_5") (pintype "bidirectional"))
      (node (ref "U6") (pin "9") (pinfunction "IO2_9") (pintype "bidirectional"))
      (node (ref "U7") (pin "15") (pinfunction "DQ3_15") (pintype "bidirectional"))
    )
    (net (code "68") (name "/D_3V3B3") (class "Default")
      (node (ref "P4") (pin "3") (pinfunction "3_3") (pintype "passive"))
      (node (ref "U18") (pin "43") (pinfunction "1A4_43") (pintype "bidirectional"))
      (node (ref "U4") (pin "6") (pinfunction "1B4_6") (pintype "bidirectional"))
      (node (ref "U6") (pin "10") (pinfunction "IO3_10") (pintype "bidirectional"))
      (node (ref "U7") (pin "17") (pinfunction "DQ4_17") (pintype "bidirectional"))
    )
    (net (code "69") (name "/D_3V3B4") (class "Default")
      (node (ref "P4") (pin "6") (pinfunction "6_6") (pintype "passive"))
      (node (ref "U18") (pin "41") (pinfunction "1A5_41") (pintype "bidirectional"))
      (node (ref "U4") (pin "8") (pinfunction "1B5_8") (pintype "bidirectional"))
      (node (ref "U6") (pin "13") (pinfunction "IO4_13") (pintype "bidirectional"))
      (node (ref "U7") (pin "18") (pinfunction "DQ5_18") (pintype "bidirectional"))
    )
    (net (code "70") (name "/D_3V3B5") (class "Default")
      (node (ref "P4") (pin "5") (pinfunction "5_5") (pintype "passive"))
      (node (ref "U18") (pin "40") (pinfunction "1A6_40") (pintype "bidirectional"))
      (node (ref "U4") (pin "9") (pinfunction "1B6_9") (pintype "bidirectional"))
      (node (ref "U6") (pin "14") (pinfunction "IO5_14") (pintype "bidirectional"))
      (node (ref "U7") (pin "19") (pinfunction "DQ6_19") (pintype "bidirectional"))
    )
    (net (code "71") (name "/D_3V3B6") (class "Default")
      (node (ref "P4") (pin "8") (pinfunction "8_8") (pintype "passive"))
      (node (ref "U18") (pin "38") (pinfunction "1A7_38") (pintype "bidirectional"))
      (node (ref "U4") (pin "11") (pinfunction "1B7_11") (pintype "bidirectional"))
      (node (ref "U6") (pin "15") (pinfunction "IO6_15") (pintype "bidirectional"))
      (node (ref "U7") (pin "20") (pinfunction "DQ7_20") (pintype "bidirectional"))
    )
    (net (code "72") (name "/D_3V3B7") (class "Default")
      (node (ref "P4") (pin "7") (pinfunction "7_7") (pintype "passive"))
      (node (ref "U18") (pin "37") (pinfunction "1A8_37") (pintype "bidirectional"))
      (node (ref "U4") (pin "12") (pinfunction "1B8_12") (pintype "bidirectional"))
      (node (ref "U6") (pin "16") (pinfunction "IO7_16") (pintype "bidirectional"))
      (node (ref "U7") (pin "21") (pinfunction "DQ8_21") (pintype "bidirectional"))
    )
    (net (code "73") (name "/D_3V3B8") (class "Default")
      (node (ref "P4") (pin "10") (pinfunction "10_10") (pintype "passive"))
      (node (ref "U4") (pin "13") (pinfunction "2B1_13") (pintype "bidirectional"))
      (node (ref "U6") (pin "29") (pinfunction "IO8_29") (pintype "bidirectional"))
    )
    (net (code "74") (name "/D_3V3B9") (class "Default")
      (node (ref "P4") (pin "9") (pinfunction "9_9") (pintype "passive"))
      (node (ref "U4") (pin "14") (pinfunction "2B2_14") (pintype "bidirectional"))
      (node (ref "U6") (pin "30") (pinfunction "IO9_30") (pintype "bidirectional"))
    )
    (net (code "75") (name "/D_3V3B10") (class "Default")
      (node (ref "P4") (pin "12") (pinfunction "12_12") (pintype "passive"))
      (node (ref "U4") (pin "16") (pinfunction "2B3_16") (pintype "bidirectional"))
      (node (ref "U6") (pin "31") (pinfunction "IO10_31") (pintype "bidirectional"))
    )
    (net (code "76") (name "/D_3V3B11") (class "Default")
      (node (ref "P4") (pin "11") (pinfunction "11_11") (pintype "passive"))
      (node (ref "U4") (pin "17") (pinfunction "2B4_17") (pintype "bidirectional"))
      (node (ref "U6") (pin "32") (pinfunction "IO11_32") (pintype "bidirectional"))
    )
    (net (code "77") (name "/D_3V3B12") (class "Default")
      (node (ref "P4") (pin "14") (pinfunction "14_14") (pintype "passive"))
      (node (ref "U4") (pin "19") (pinfunction "2B5_19") (pintype "bidirectional"))
      (node (ref "U6") (pin "35") (pinfunction "IO12_35") (pintype "bidirectional"))
    )
    (net (code "78") (name "/D_3V3B13") (class "Default")
      (node (ref "P4") (pin "13") (pinfunction "13_13") (pintype "passive"))
      (node (ref "U4") (pin "20") (pinfunction "2B6_20") (pintype "bidirectional"))
      (node (ref "U6") (pin "36") (pinfunction "IO13_36") (pintype "bidirectional"))
    )
    (net (code "79") (name "/D_3V3B14") (class "Default")
      (node (ref "P4") (pin "16") (pinfunction "16_16") (pintype "passive"))
      (node (ref "U4") (pin "22") (pinfunction "2B7_22") (pintype "bidirectional"))
      (node (ref "U6") (pin "37") (pinfunction "IO14_37") (pintype "bidirectional"))
    )
    (net (code "80") (name "/D_3V3B15") (class "Default")
      (node (ref "P4") (pin "15") (pinfunction "15_15") (pintype "passive"))
      (node (ref "U4") (pin "23") (pinfunction "2B8_23") (pintype "bidirectional"))
      (node (ref "U6") (pin "38") (pinfunction "IO15_38") (pintype "bidirectional"))
    )
    (net (code "82") (name "/D_5V0") (class "Default")
      (node (ref "U18") (pin "2") (pinfunction "1B1_2") (pintype "bidirectional"))
      (node (ref "U20") (pin "3") (pinfunction "DQ1_3") (pintype "bidirectional"))
    )
    (net (code "83") (name "/D_5V1") (class "Default")
      (node (ref "U18") (pin "3") (pinfunction "1B2_3") (pintype "bidirectional"))
      (node (ref "U20") (pin "6") (pinfunction "DQ2_6") (pintype "bidirectional"))
    )
    (net (code "84") (name "/D_5V2") (class "Default")
      (node (ref "U18") (pin "5") (pinfunction "1B3_5") (pintype "bidirectional"))
      (node (ref "U20") (pin "10") (pinfunction "DQ3_10") (pintype "bidirectional"))
    )
    (net (code "85") (name "/D_5V3") (class "Default")
      (node (ref "U18") (pin "6") (pinfunction "1B4_6") (pintype "bidirectional"))
      (node (ref "U20") (pin "13") (pinfunction "DQ4_13") (pintype "bidirectional"))
    )
    (net (code "86") (name "/D_5V4") (class "Default")
      (node (ref "U18") (pin "8") (pinfunction "1B5_8") (pintype "bidirectional"))
      (node (ref "U20") (pin "16") (pinfunction "DQ5_16") (pintype "bidirectional"))
    )
    (net (code "87") (name "/D_5V5") (class "Default")
      (node (ref "U18") (pin "9") (pinfunction "1B6_9") (pintype "bidirectional"))
      (node (ref "U20") (pin "20") (pinfunction "DQ6_20") (pintype "bidirectional"))
    )
    (net (code "88") (name "/D_5V6") (class "Default")
      (node (ref "U18") (pin "11") (pinfunction "1B7_11") (pintype "bidirectional"))
      (node (ref "U20") (pin "23") (pinfunction "DQ7_23") (pintype "bidirectional"))
    )
    (net (code "89") (name "/D_5V7") (class "Default")
      (node (ref "U18") (pin "12") (pinfunction "1B8_12") (pintype "bidirectional"))
      (node (ref "U20") (pin "25") (pinfunction "DQ8_25") (pintype "bidirectional"))
    )
    (net (code "90") (name "/Data0") (class "Default")
      (node (ref "U1") (pin "179") (pinfunction "D0_179") (pintype "bidirectional"))
      (node (ref "U4") (pin "47") (pinfunction "1A1_47") (pintype "bidirectional"))
    )
    (net (code "91") (name "/Data1") (class "Default")
      (node (ref "U1") (pin "180") (pinfunction "D1_180") (pintype "bidirectional"))
      (node (ref "U4") (pin "46") (pinfunction "1A2_46") (pintype "bidirectional"))
    )
    (net (code "92") (name "/Data2") (class "Default")
      (node (ref "U1") (pin "181") (pinfunction "D2_181") (pintype "bidirectional"))
      (node (ref "U4") (pin "44") (pinfunction "1A3_44") (pintype "bidirectional"))
    )
    (net (code "93") (name "/Data3") (class "Default")
      (node (ref "U1") (pin "182") (pinfunction "D3_182") (pintype "bidirectional"))
      (node (ref "U4") (pin "43") (pinfunction "1A4_43") (pintype "bidirectional"))
    )
    (net (code "94") (name "/Data4") (class "Default")
      (node (ref "U1") (pin "185") (pinfunction "D4_185") (pintype "bidirectional"))
      (node (ref "U4") (pin "41") (pinfunction "1A5_41") (pintype "bidirectional"))
    )
    (net (code "95") (name "/Data5") (class "Default")
      (node (ref "U1") (pin "186") (pinfunction "D5_186") (pintype "bidirectional"))
      (node (ref "U4") (pin "40") (pinfunction "1A6_40") (pintype "bidirectional"))
    )
    (net (code "96") (name "/Data6") (class "Default")
      (node (ref "U1") (pin "187") (pinfunction "D6_187") (pintype "bidirectional"))
      (node (ref "U4") (pin "38") (pinfunction "1A7_38") (pintype "bidirectional"))
    )
    (net (code "97") (name "/Data7") (class "Default")
      (node (ref "U1") (pin "190") (pinfunction "D7_190") (pintype "bidirectional"))
      (node (ref "U4") (pin "37") (pinfunction "1A8_37") (pintype "bidirectional"))
    )
    (net (code "98") (name "/Data8") (class "Default")
      (node (ref "U1") (pin "191") (pinfunction "D8_191") (pintype "bidirectional"))
      (node (ref "U4") (pin "36") (pinfunction "2A1_36") (pintype "bidirectional"))
    )
    (net (code "99") (name "/Data9") (class "Default")
      (node (ref "U1") (pin "192") (pinfunction "D9_192") (pintype "bidirectional"))
      (node (ref "U4") (pin "35") (pinfunction "2A2_35") (pintype "bidirectional"))
    )
    (net (code "100") (name "/Data10") (class "Default")
      (node (ref "U1") (pin "193") (pinfunction "D10_193") (pintype "bidirectional"))
      (node (ref "U4") (pin "33") (pinfunction "2A3_33") (pintype "bidirectional"))
    )
    (net (code "101") (name "/Data11") (class "Default")
      (node (ref "U1") (pin "194") (pinfunction "D11_194") (pintype "bidirectional"))
      (node (ref "U4") (pin "32") (pinfunction "2A4_32") (pintype "bidirectional"))
    )
    (net (code "102") (name "/Data12") (class "Default")
      (node (ref "U1") (pin "195") (pinfunction "D12_195") (pintype "bidirectional"))
      (node (ref "U4") (pin "30") (pinfunction "2A5_30") (pintype "bidirectional"))
    )
    (net (code "103") (name "/Data13") (class "Default")
      (node (ref "U1") (pin "196") (pinfunction "D13_196") (pintype "bidirectional"))
      (node (ref "U4") (pin "29") (pinfunction "2A6_29") (pintype "bidirectional"))
    )
    (net (code "104") (name "/Data14") (class "Default")
      (node (ref "U1") (pin "197") (pinfunction "D14_197") (pintype "bidirectional"))
      (node (ref "U4") (pin "27") (pinfunction "2A7_27") (pintype "bidirectional"))
    )
    (net (code "105") (name "/Data15") (class "Default")
      (node (ref "U1") (pin "198") (pinfunction "D15_198") (pintype "bidirectional"))
      (node (ref "U4") (pin "26") (pinfunction "2A8_26") (pintype "bidirectional"))
    )
    (net (code "107") (name "/EAROUT+") (class "Default")
      (node (ref "J3") (pin "A") (pinfunction "RING_A") (pintype "passive"))
      (node (ref "J3") (pin "D") (pinfunction "TIP_D") (pintype "passive"))
      (node (ref "U17") (pin "5") (pinfunction "EAROUT+_5") (pintype "output"))
    )
    (net (code "108") (name "/EAROUT-") (class "Default")
      (node (ref "J3") (pin "E") (pinfunction "SLEEVE_E") (pintype "passive"))
      (node (ref "U17") (pin "7") (pinfunction "EAROUT-_7") (pintype "output"))
    )
    (net (code "109") (name "/ECOL") (class "Default")
      (node (ref "R27") (pin "1") (pinfunction "1_1") (pintype "passive"))
      (node (ref "U1") (pin "100") (pinfunction "PB18/RI1/ECOL_100") (pintype "bidirectional"))
      (node (ref "U16") (pin "42") (pinfunction "PHYAD0/COL_42") (pintype "bidirectional"))
    )
    (net (code "110") (name "/ECRS") (class "Default")
      (node (ref "R30") (pin "1") (pinfunction "1_1") (pintype "passive"))
      (node (ref "U1") (pin "53") (pinfunction "PA11/ECRS/ECRSDV/MCDB2_53") (pintype "bidirectional"))
      (node (ref "U16") (pin "40") (pinfunction "LED_CFG/CRS/CRS_DV_40") (pintype "bidirectional"))
    )
    (net (code "111") (name "/EMDC") (class "Default")
      (node (ref "U1") (pin "59") (pinfunction "PA15/EMDC/TCLK2_59") (pintype "bidirectional"))
      (node (ref "U16") (pin "31") (pinfunction "MDC_31") (pintype "input"))
    )
    (net (code "112") (name "/EMDIO") (class "Default")
      (node (ref "R23") (pin "2") (pinfunction "2_2") (pintype "passive"))
      (node (ref "U1") (pin "60") (pinfunction "PA16/EMDIO/IRQ6_60") (pintype "bidirectional"))
      (node (ref "U16") (pin "30") (pinfunction "MDIO_30") (pintype "bidirectional"))
    )
    (net (code "113") (name "/ERX0") (class "Default")
      (node (ref "R36") (pin "2") (pinfunction "2_2") (pintype "passive"))
      (node (ref "U1") (pin "54") (pinfunction "PA12/ERX0/MCDB3_54") (pintype "bidirectional"))
      (node (ref "U16") (pin "43") (pinfunction "RXD_0/PHYAD1_43") (pintype "bidirectional"))
    )
    (net (code "114") (name "/ERX1") (class "Default")
      (node (ref "R37") (pin "2") (pinfunction "2_2") (pintype "passive"))
      (node (ref "U1") (pin "55") (pinfunction "PA13/ERX1/TCLK0_55") (pintype "bidirectional"))
      (node (ref "U16") (pin "44") (pinfunction "RXD_1/PHYAD2_44") (pintype "bidirectional"))
    )
    (net (code "115") (name "/ERX2") (class "Default")
      (node (ref "R38") (pin "2") (pinfunction "2_2") (pintype "passive"))
      (node (ref "U1") (pin "97") (pinfunction "PB15/RD2/ERX2_97") (pintype "bidirectional"))
      (node (ref "U16") (pin "45") (pinfunction "RXD_2/PHYAD3_45") (pintype "bidirectional"))
    )
    (net (code "116") (name "/ERX3") (class "Default")
      (node (ref "R39") (pin "1") (pinfunction "1_1") (pintype "passive"))
      (node (ref "U1") (pin "98") (pinfunction "PB16/RK2/ERX3_98") (pintype "bidirectional"))
      (node (ref "U16") (pin "46") (pinfunction "RXD_3/PHYAD4_46") (pintype "bidirectional"))
    )
    (net (code "117") (name "/ERXCK") (class "Default")
      (node (ref "U1") (pin "101") (pinfunction "PB19/DTR1/ERXCK_101") (pintype "bidirectional"))
      (node (ref "U16") (pin "38") (pinfunction "RX_CLK_38") (pintype "output"))
    )
    (net (code "118") (name "/ERXDV") (class "Default")
      (node (ref "R35") (pin "1") (pinfunction "1_1") (pintype "passive"))
      (node (ref "U1") (pin "99") (pinfunction "PB17/RF2/ERXDV_99") (pintype "bidirectional"))
      (node (ref "U16") (pin "39") (pinfunction "MII_MODE/RX_DV_39") (pintype "bidirectional"))
    )
    (net (code "119") (name "/ERXER") (class "Default")
      (node (ref "R34") (pin "1") (pinfunction "1_1") (pintype "passive"))
      (node (ref "U1") (pin "58") (pinfunction "PA14/ERXER/TCLK1_58") (pintype "bidirectional"))
      (node (ref "U16") (pin "41") (pinfunction "MDIX_EN/RX_ER_41") (pintype "bidirectional"))
    )
    (net (code "120") (name "/ETX0") (class "Default")
      (node (ref "U1") (pin "51") (pinfunction "PA9/ETX0/MCDB0_51") (pintype "bidirectional"))
      (node (ref "U16") (pin "3") (pinfunction "TX_D0_3") (pintype "input"))
    )
    (net (code "121") (name "/ETX1") (class "Default")
      (node (ref "U1") (pin "52") (pinfunction "PA10/ETX1/MCDB1_52") (pintype "bidirectional"))
      (node (ref "U16") (pin "4") (pinfunction "TX_D1_4") (pintype "input"))
    )
    (net (code "122") (name "/ETX2") (class "Default")
      (node (ref "U1") (pin "92") (pinfunction "PB12/TF2/EXT2_92") (pintype "bidirectional"))
      (node (ref "U16") (pin "5") (pinfunction "TX_D2_5") (pintype "input"))
    )
    (net (code "123") (name "/ETX3") (class "Default")
      (node (ref "U1") (pin "95") (pinfunction "PB13/TK2/ETX3_95") (pintype "bidirectional"))
      (node (ref "U16") (pin "6") (pinfunction "TX_D3/SNI_MODE_6") (pintype "input"))
    )
    (net (code "124") (name "/ETXCK") (class "Default")
      (node (ref "U1") (pin "49") (pinfunction "PA7/ETXCK/EREFCK/PCK2_49") (pintype "bidirectional"))
      (node (ref "U16") (pin "1") (pinfunction "TX_CLK_1") (pintype "output"))
    )
    (net (code "125") (name "/ETXEN") (class "Default")
      (node (ref "U1") (pin "50") (pinfunction "PA8/ETXEN/MCCDB_50") (pintype "bidirectional"))
      (node (ref "U16") (pin "2") (pinfunction "TX_EN_2") (pintype "input"))
    )
    (net (code "126") (name "/ETXER") (class "Default")
      (node (ref "U1") (pin "96") (pinfunction "PB14/TD2/ETXER_96") (pintype "bidirectional"))
    )
    (net (code "127") (name "/GNDOSC") (class "Default")
      (node (ref "C19") (pin "1") (pinfunction "1_1") (pintype "passive"))
      (node (ref "C23") (pin "2") (pinfunction "2_2") (pintype "passive"))
      (node (ref "C27") (pin "2") (pinfunction "2_2") (pintype "passive"))
      (node (ref "C28") (pin "2") (pinfunction "2_2") (pintype "passive"))
      (node (ref "C30") (pin "2") (pinfunction "2_2") (pintype "passive"))
      (node (ref "L4") (pin "1") (pinfunction "1_1") (pintype "passive"))
      (node (ref "U1") (pin "34") (pinfunction "GNDOSC_34") (pintype "power_in"))
    )
    (net (code "128") (name "/GNDPLL") (class "Default")
      (node (ref "C15") (pin "1") (pinfunction "1_1") (pintype "passive"))
      (node (ref "C17") (pin "1") (pinfunction "1_1") (pintype "passive"))
      (node (ref "C22") (pin "2") (pinfunction "2_2") (pintype "passive"))
      (node (ref "C26") (pin "2") (pinfunction "2_2") (pintype "passive"))
      (node (ref "C29") (pin "2") (pinfunction "2_2") (pintype "passive"))
      (node (ref "C31") (pin "2") (pinfunction "2_2") (pintype "passive"))
      (node (ref "L3") (pin "1") (pinfunction "1_1") (pintype "passive"))
      (node (ref "U1") (pin "30") (pinfunction "GNDPLL_30") (pintype "power_in"))
      (node (ref "U1") (pin "39") (pinfunction "GNDPLL_39") (pintype "power_in"))
    )
    (net (code "129") (name "/JTAG_NRST") (class "Default")
      (node (ref "P1") (pin "15") (pinfunction "15_15") (pintype "passive"))
      (node (ref "R67") (pin "1") (pinfunction "1_1") (pintype "passive"))
      (node (ref "SW_RESET") (pin "2") (pintype "passive"))
      (node (ref "U3") (pin "1") (pinfunction "MR_1") (pintype "input"))
    )
    (net (code "130") (name "/JTAG_NTRST") (class "Default")
      (node (ref "P1") (pin "3") (pinfunction "3_3") (pintype "passive"))
      (node (ref "P6") (pin "2") (pinfunction "2_2") (pintype "passive"))
      (node (ref "R12") (pin "1") (pinfunction "1_1") (pintype "passive"))
      (node (ref "U5") (pin "15") (pinfunction "I/O0_15") (pintype "bidirectional"))
    )
    (net (code "131") (name "/KEYPAD_D0") (class "Default")
      (node (ref "U1") (pin "4") (pinfunction "PC27/D27_4") (pintype "bidirectional"))
      (node (ref "U13") (pin "19") (pinfunction "DATA0_19") (pintype "tri_state"))
    )
    (net (code "132") (name "/KEYPAD_D1") (class "Default")
      (node (ref "U1") (pin "5") (pinfunction "PC28/D28_5") (pintype "bidirectional"))
      (node (ref "U13") (pin "18") (pinfunction "DATA1_18") (pintype "tri_state"))
    )
    (net (code "133") (name "/KEYPAD_D2") (class "Default")
      (node (ref "U1") (pin "6") (pinfunction "PC29/D29_6") (pintype "bidirectional"))
      (node (ref "U13") (pin "17") (pinfunction "DATA2_17") (pintype "tri_state"))
    )
    (net (code "134") (name "/KEYPAD_D3") (class "Default")
      (node (ref "U1") (pin "9") (pinfunction "PC30/D30_9") (pintype "bidirectional"))
      (node (ref "U13") (pin "16") (pinfunction "DATA3_16") (pintype "tri_state"))
    )
    (net (code "135") (name "/KEYPAD_D4") (class "Default")
      (node (ref "U1") (pin "10") (pinfunction "PC31/D31_10") (pintype "bidirectional"))
      (node (ref "U13") (pin "15") (pinfunction "DATA4_15") (pintype "passive"))
    )
    (net (code "136") (name "/KEYPAD_RDY") (class "Default")
      (node (ref "U1") (pin "3") (pinfunction "PC26/D26_3") (pintype "bidirectional"))
      (node (ref "U13") (pin "13") (pinfunction "RDY_13") (pintype "output"))
    )
    (net (code "137") (name "/MICIN+") (class "Default")
      (node (ref "C62") (pin "1") (pinfunction "1_1") (pintype "passive"))
      (node (ref "J2") (pin "A") (pinfunction "RING_A") (pintype "passive"))
      (node (ref "J2") (pin "D") (pinfunction "TIP_D") (pintype "passive"))
      (node (ref "R24") (pin "1") (pinfunction "1_1") (pintype "passive"))
    )
    (net (code "138") (name "/MICIN-") (class "Default")
      (node (ref "C64") (pin "1") (pinfunction "1_1") (pintype "passive"))
      (node (ref "J2") (pin "E") (pinfunction "SLEEVE_E") (pintype "passive"))
      (node (ref "R33") (pin "2") (pinfunction "2_2") (pintype "passive"))
    )
    (net (code "139") (name "/NBS1_3V3_Buf") (class "Default")
      (node (ref "U6") (pin "40") (pinfunction "BHE_40") (pintype "input"))
      (node (ref "U8") (pin "5") (pinfunction "1B3_5") (pintype "bidirectional"))
    )
    (net (code "140") (name "/NCS0") (class "Default")
      (node (ref "U1") (pin "166") (pinfunction "NCS0/BFCS_166") (pintype "output"))
      (node (ref "U8") (pin "36") (pinfunction "2A1_36") (pintype "bidirectional"))
    )
    (net (code "141") (name "/NCS1") (class "Default")
      (node (ref "U1") (pin "167") (pinfunction "NCS1/SDCS_167") (pintype "output"))
      (node (ref "U8") (pin "35") (pinfunction "2A2_35") (pintype "bidirectional"))
    )
    (net (code "142") (name "/NCS2") (class "Default")
      (node (ref "U1") (pin "168") (pinfunction "NCS2_168") (pintype "output"))
      (node (ref "U8") (pin "33") (pinfunction "2A3_33") (pintype "bidirectional"))
    )
    (net (code "143") (name "/NCS3") (class "Default")
      (node (ref "U1") (pin "169") (pinfunction "NCS3/SMCS_169") (pintype "output"))
      (node (ref "U8") (pin "32") (pinfunction "2A4_32") (pintype "bidirectional"))
    )
    (net (code "144") (name "/NCS3V3B0") (class "Default")
      (node (ref "P8") (pin "1") (pinfunction "1_1") (pintype "passive"))
      (node (ref "U8") (pin "13") (pinfunction "2B1_13") (pintype "bidirectional"))
    )
    (net (code "145") (name "/NCS3V3B1") (class "Default")
      (node (ref "P8") (pin "2") (pinfunction "2_2") (pintype "passive"))
      (node (ref "U6") (pin "6") (pinfunction "CS_6") (pintype "input"))
      (node (ref "U8") (pin "14") (pinfunction "2B2_14") (pintype "bidirectional"))
    )
    (net (code "146") (name "/NCS3V3B2") (class "Default")
      (node (ref "P6") (pin "1") (pinfunction "1_1") (pintype "passive"))
      (node (ref "P8") (pin "3") (pinfunction "3_3") (pintype "passive"))
      (node (ref "U18") (pin "25") (pinfunction "2OE_25") (pintype "input"))
      (node (ref "U18") (pin "48") (pinfunction "1OE_48") (pintype "input"))
      (node (ref "U5") (pin "25") (pinfunction "I/O8_25") (pintype "bidirectional"))
      (node (ref "U8") (pin "16") (pinfunction "2B3_16") (pintype "bidirectional"))
    )
    (net (code "147") (name "/NCS3V3B3") (class "Default")
      (node (ref "P8") (pin "4") (pinfunction "4_4") (pintype "passive"))
      (node (ref "U8") (pin "17") (pinfunction "2B4_17") (pintype "bidirectional"))
    )
    (net (code "148") (name "/NCS3V3B4") (class "Default")
      (node (ref "P8") (pin "5") (pinfunction "5_5") (pintype "passive"))
      (node (ref "U8") (pin "19") (pinfunction "2B5_19") (pintype "bidirectional"))
    )
    (net (code "149") (name "/NCS3V3B5") (class "Default")
      (node (ref "P8") (pin "6") (pinfunction "6_6") (pintype "passive"))
      (node (ref "U8") (pin "20") (pinfunction "2B6_20") (pintype "bidirectional"))
    )
    (net (code "150") (name "/NCS3V3B6") (class "Default")
      (node (ref "P8") (pin "7") (pinfunction "7_7") (pintype "passive"))
      (node (ref "U8") (pin "22") (pinfunction "2B7_22") (pintype "bidirectional"))
    )
    (net (code "151") (name "/NCS3V3B7") (class "Default")
      (node (ref "P8") (pin "8") (pinfunction "8_8") (pintype "passive"))
      (node (ref "U7") (pin "22") (pinfunction "CE_22") (pintype "input"))
      (node (ref "U8") (pin "23") (pinfunction "2B8_23") (pintype "bidirectional"))
    )
    (net (code "153") (name "/NCS4") (class "Default")
      (node (ref "U1") (pin "11") (pinfunction "PC10/NCS4/CFCS_11") (pintype "bidirectional"))
      (node (ref "U8") (pin "30") (pinfunction "2A5_30") (pintype "bidirectional"))
    )
    (net (code "154") (name "/NCS5") (class "Default")
      (node (ref "U1") (pin "12") (pinfunction "PC11/NCS5/CFCE1_12") (pintype "bidirectional"))
      (node (ref "U8") (pin "29") (pinfunction "2A6_29") (pintype "bidirectional"))
    )
    (net (code "155") (name "/NCS6") (class "Default")
      (node (ref "U1") (pin "13") (pinfunction "PC12/NCS6/CFCE2_13") (pintype "bidirectional"))
      (node (ref "U8") (pin "27") (pinfunction "2A7_27") (pintype "bidirectional"))
    )
    (net (code "156") (name "/NCS7") (class "Default")
      (node (ref "U1") (pin "14") (pinfunction "PC13/NCS7_14") (pintype "bidirectional"))
      (node (ref "U8") (pin "26") (pinfunction "2A8_26") (pintype "bidirectional"))
    )
    (net (code "158") (name "/NRD") (class "Default")
      (node (ref "U1") (pin "170") (pinfunction "NRD/NOE/CFOE_170") (pintype "output"))
      (node (ref "U18") (pin "1") (pinfunction "1DIR_1") (pintype "input"))
      (node (ref "U18") (pin "24") (pinfunction "2DIR_24") (pintype "input"))
      (node (ref "U4") (pin "1") (pinfunction "1DIR_1") (pintype "input"))
      (node (ref "U4") (pin "24") (pinfunction "2DIR_24") (pintype "input"))
      (node (ref "U8") (pin "47") (pinfunction "1A1_47") (pintype "bidirectional"))
    )
    (net (code "159") (name "/NRD_NOE_3V3_Buf") (class "Default")
      (node (ref "U6") (pin "41") (pinfunction "OE_41") (pintype "passive"))
      (node (ref "U7") (pin "24") (pinfunction "OE_24") (pintype "passive"))
      (node (ref "U8") (pin "2") (pinfunction "1B1_2") (pintype "bidirectional"))
    )
    (net (code "160") (name "/NTRST") (class "Default")
      (node (ref "P6") (pin "6") (pinfunction "6_6") (pintype "passive"))
      (node (ref "U1") (pin "110") (pinfunction "NTRST_110") (pintype "input"))
      (node (ref "U5") (pin "17") (pinfunction "I/O2_17") (pintype "bidirectional"))
    )
    (net (code "161") (name "/NWAIT") (class "Default")
      (node (ref "P6") (pin "5") (pinfunction "5_5") (pintype "passive"))
      (node (ref "U1") (pin "25") (pinfunction "PC6/NWAIT_25") (pintype "bidirectional"))
      (node (ref "U5") (pin "27") (pinfunction "I/O10_27") (pintype "bidirectional"))
    )
    (net (code "162") (name "/NWE_3V3_Buf") (class "Default")
      (node (ref "P6") (pin "3") (pinfunction "3_3") (pintype "passive"))
      (node (ref "U5") (pin "26") (pinfunction "I/O9_26") (pintype "bidirectional"))
      (node (ref "U6") (pin "17") (pinfunction "WE_17") (pintype "input"))
      (node (ref "U7") (pin "31") (pinfunction "WE_31") (pintype "input"))
      (node (ref "U8") (pin "3") (pinfunction "1B2_3") (pintype "bidirectional"))
    )
    (net (code "163") (name "/PCK0") (class "Default")
      (node (ref "P6") (pin "7") (pinfunction "7_7") (pintype "passive"))
      (node (ref "U1") (pin "122") (pinfunction "PB27/PCK0_122") (pintype "bidirectional"))
      (node (ref "U5") (pin "11") (pinfunction "Y0_11") (pintype "input"))
      (node (ref "U5") (pin "28") (pinfunction "I/O11_28") (pintype "bidirectional"))
    )
    (net (code "164") (name "/PCK1") (class "Default")
      (node (ref "P6") (pin "9") (pinfunction "9_9") (pintype "passive"))
      (node (ref "U1") (pin "70") (pinfunction "PA24/SCK2/PCK1_70") (pintype "bidirectional"))
      (node (ref "U5") (pin "29") (pinfunction "I/O12_29") (pintype "bidirectional"))
    )
    (net (code "165") (name "/PFI") (class "Default")
      (node (ref "R3") (pin "1") (pinfunction "1_1") (pintype "passive"))
      (node (ref "R4") (pin "2") (pinfunction "2_2") (pintype "passive"))
      (node (ref "U3") (pin "4") (pinfunction "PFI_4") (pintype "passive"))
    )
    (net (code "166") (name "/RAS") (class "Default")
      (node (ref "P6") (pin "8") (pinfunction "8_8") (pintype "passive"))
      (node (ref "R55") (pin "2") (pinfunction "2_2") (pintype "passive"))
      (node (ref "U5") (pin "18") (pinfunction "I/O3_18") (pintype "bidirectional"))
    )
    (net (code "167") (name "/RD0") (class "Default")
      (node (ref "U1") (pin "83") (pinfunction "PB3/RD0/MCDA1_83") (pintype "bidirectional"))
      (node (ref "U17") (pin "17") (pinfunction "PCMO_17") (pintype "output"))
    )
    (net (code "168") (name "/RESET") (class "Default")
      (node (ref "P6") (pin "4") (pinfunction "4_4") (pintype "passive"))
      (node (ref "R66") (pin "1") (pinfunction "1_1") (pintype "passive"))
      (node (ref "U1") (pin "115") (pinfunction "NRST_115") (pintype "input"))
      (node (ref "U16") (pin "29") (pinfunction "RESET_29") (pintype "input"))
      (node (ref "U17") (pin "2") (pinfunction "RESET_2") (pintype "input"))
      (node (ref "U3") (pin "7") (pinfunction "RESET_7") (pintype "output"))
      (node (ref "U5") (pin "16") (pinfunction "I/O1_16") (pintype "bidirectional"))
      (node (ref "U5") (pin "35") (pinfunction "Y1/~{RESET}_35") (pintype "input"))
    )
    (net (code "169") (name "/ROW_ADDR_EN") (class "Default")
      (node (ref "P6") (pin "14") (pinfunction "14_14") (pintype "passive"))
      (node (ref "R45") (pin "1") (pinfunction "1_1") (pintype "passive"))
      (node (ref "U19") (pin "25") (pinfunction "2OE_25") (pintype "input"))
      (node (ref "U19") (pin "48") (pinfunction "1OE_48") (pintype "input"))
      (node (ref "U5") (pin "21") (pinfunction "I/O6_21") (pintype "bidirectional"))
    )
    (net (code "170") (name "/TCK") (class "Default")
      (node (ref "P1") (pin "9") (pinfunction "9_9") (pintype "passive"))
      (node (ref "R9") (pin "1") (pinfunction "1_1") (pintype "passive"))
      (node (ref "U1") (pin "108") (pinfunction "TCK_108") (pintype "input"))
    )
    (net (code "171") (name "/TD0") (class "Default")
      (node (ref "U1") (pin "82") (pinfunction "PB2/TD0/SCK3_82") (pintype "bidirectional"))
      (node (ref "U17") (pin "16") (pinfunction "PCMI_16") (pintype "input"))
    )
    (net (code "172") (name "/TDI") (class "Default")
      (node (ref "P1") (pin "5") (pinfunction "5_5") (pintype "passive"))
      (node (ref "R11") (pin "1") (pinfunction "1_1") (pintype "passive"))
      (node (ref "U1") (pin "106") (pinfunction "TDI_106") (pintype "input"))
    )
    (net (code "173") (name "/TDO") (class "Default")
      (node (ref "P1") (pin "13") (pinfunction "13_13") (pintype "passive"))
      (node (ref "R7") (pin "1") (pinfunction "1_1") (pintype "passive"))
      (node (ref "U1") (pin "107") (pinfunction "TDO_107") (pintype "output"))
    )
    (net (code "174") (name "/TF0") (class "Default")
      (node (ref "U1") (pin "80") (pinfunction "PB0/TF0/RTS3_80") (pintype "bidirectional"))
      (node (ref "U17") (pin "18") (pinfunction "PCMSYNC_18") (pintype "input"))
    )
    (net (code "175") (name "/TK0") (class "Default")
      (node (ref "U1") (pin "81") (pinfunction "PB1/TK0/CTS3_81") (pintype "bidirectional"))
      (node (ref "U17") (pin "19") (pinfunction "MCLK_19") (pintype "input"))
    )
    (net (code "176") (name "/TMS") (class "Default")
      (node (ref "P1") (pin "7") (pinfunction "7_7") (pintype "passive"))
      (node (ref "R10") (pin "1") (pinfunction "1_1") (pintype "passive"))
      (node (ref "U1") (pin "109") (pinfunction "TMS_109") (pintype "input"))
    )
    (net (code "177") (name "1V8") (class "Default")
      (node (ref "C11") (pin "2") (pinfunction "2_2") (pintype "passive"))
      (node (ref "C13") (pin "2") (pinfunction "2_2") (pintype "passive"))
      (node (ref "C15") (pin "2") (pinfunction "2_2") (pintype "passive"))
      (node (ref "C17") (pin "2") (pinfunction "2_2") (pintype "passive"))
      (node (ref "C19") (pin "2") (pinfunction "2_2") (pintype "passive"))
      (node (ref "C5") (pin "2") (pinfunction "2_2") (pintype "passive"))
      (node (ref "C7") (pin "2") (pinfunction "2_2") (pintype "passive"))
      (node (ref "C72") (pin "2") (pinfunction "2_2") (pintype "passive"))
      (node (ref "C9") (pin "2") (pinfunction "2_2") (pintype "passive"))
      (node (ref "P9") (pin "2") (pinfunction "2_2") (pintype "passive"))
      (node (ref "R47") (pin "2") (pinfunction "2_2") (pintype "passive"))
      (node (ref "REG_1V8") (pin "2") (pinfunction "Vout_2") (pintype "output"))
      (node (ref "U1") (pin "116") (pinfunction "VDDCORE_116") (pintype "power_in"))
      (node (ref "U1") (pin "152") (pinfunction "VDDCORE_152") (pintype "power_in"))
      (node (ref "U1") (pin "188") (pinfunction "VDDCORE_188") (pintype "power_in"))
      (node (ref "U1") (pin "19") (pinfunction "VDDCORE_19") (pintype "power_in"))
      (node (ref "U1") (pin "28") (pinfunction "VDDPLL_28") (pintype "power_in"))
      (node (ref "U1") (pin "33") (pinfunction "VDDOSC_33") (pintype "power_in"))
      (node (ref "U1") (pin "37") (pinfunction "VDDPLL_37") (pintype "power_in"))
      (node (ref "U1") (pin "62") (pinfunction "VDDCORE_62") (pintype "power_in"))
    )
    (net (code "178") (name "3V") (class "Default")
      (node (ref "C53") (pin "1") (pinfunction "1_1") (pintype "passive"))
      (node (ref "C54") (pin "1") (pinfunction "1_1") (pintype "passive"))
      (node (ref "C78") (pin "2") (pinfunction "2_2") (pintype "passive"))
      (node (ref "C79") (pin "2") (pinfunction "2_2") (pintype "passive"))
      (node (ref "DISP1") (pin "12") (pinfunction "VDD_12") (pintype "passive"))
      (node (ref "DISP1") (pin "18") (pinfunction "LED_A_18") (pintype "passive"))
      (node (ref "P9") (pin "3") (pinfunction "3_3") (pintype "passive"))
      (node (ref "R53") (pin "2") (pinfunction "2_2") (pintype "passive"))
      (node (ref "REG_3V") (pin "2") (pinfunction "Vout_2") (pintype "output"))
      (node (ref "U11") (pin "16") (pinfunction "VDD_16") (pintype "power_in"))
      (node (ref "U9") (pin "16") (pinfunction "VDD_16") (pintype "power_in"))
    )
    (net (code "179") (name "3V3") (class "Default")
      (node (ref "C1") (pin "1") (pinfunction "1_1") (pintype "passive"))
      (node (ref "C10") (pin "1") (pinfunction "1_1") (pintype "passive"))
      (node (ref "C100") (pin "1") (pinfunction "1_1") (pintype "passive"))
      (node (ref "C101") (pin "1") (pinfunction "1_1") (pintype "passive"))
      (node (ref "C102") (pin "1") (pinfunction "1_1") (pintype "passive"))
      (node (ref "C103") (pin "1") (pinfunction "1_1") (pintype "passive"))
      (node (ref "C104") (pin "1") (pinfunction "1_1") (pintype "passive"))
      (node (ref "C105") (pin "1") (pinfunction "1_1") (pintype "passive"))
      (node (ref "C106") (pin "1") (pinfunction "1_1") (pintype "passive"))
      (node (ref "C107") (pin "1") (pinfunction "1_1") (pintype "passive"))
      (node (ref "C12") (pin "1") (pinfunction "1_1") (pintype "passive"))
      (node (ref "C14") (pin "1") (pinfunction "1_1") (pintype "passive"))
      (node (ref "C16") (pin "1") (pinfunction "1_1") (pintype "passive"))
      (node (ref "C18") (pin "1") (pinfunction "1_1") (pintype "passive"))
      (node (ref "C2") (pin "1") (pinfunction "1_1") (pintype "passive"))
      (node (ref "C20") (pin "1") (pinfunction "1_1") (pintype "passive"))
      (node (ref "C21") (pin "1") (pinfunction "1_1") (pintype "passive"))
      (node (ref "C24") (pin "1") (pinfunction "1_1") (pintype "passive"))
      (node (ref "C25") (pin "1") (pinfunction "1_1") (pintype "passive"))
      (node (ref "C3") (pin "1") (pinfunction "1_1") (pintype "passive"))
      (node (ref "C32") (pin "1") (pinfunction "1_1") (pintype "passive"))
      (node (ref "C33") (pin "1") (pinfunction "1_1") (pintype "passive"))
      (node (ref "C34") (pin "1") (pinfunction "1_1") (pintype "passive"))
      (node (ref "C35") (pin "1") (pinfunction "1_1") (pintype "passive"))
      (node (ref "C36") (pin "1") (pinfunction "1_1") (pintype "passive"))
      (node (ref "C37") (pin "1") (pinfunction "1_1") (pintype "passive"))
      (node (ref "C38") (pin "1") (pinfunction "1_1") (pintype "passive"))
      (node (ref "C4") (pin "1") (pinfunction "1_1") (pintype "passive"))
      (node (ref "C49") (pin "1") (pinfunction "1_1") (pintype "passive"))
      (node (ref "C50") (pin "1") (pinfunction "1_1") (pintype "passive"))
      (node (ref "C51") (pin "1") (pinfunction "1_1") (pintype "passive"))
      (node (ref "C52") (pin "1") (pinfunction "1_1") (pintype "passive"))
      (node (ref "C55") (pin "1") (pinfunction "1_1") (pintype "passive"))
      (node (ref "C56") (pin "1") (pinfunction "1_1") (pintype "passive"))
      (node (ref "C57") (pin "1") (pinfunction "1_1") (pintype "passive"))
      (node (ref "C58") (pin "1") (pinfunction "1_1") (pintype "passive"))
      (node (ref "C6") (pin "1") (pinfunction "1_1") (pintype "passive"))
      (node (ref "C67") (pin "1") (pinfunction "1_1") (pintype "passive"))
      (node (ref "C68") (pin "1") (pinfunction "1_1") (pintype "passive"))
      (node (ref "C69") (pin "1") (pinfunction "1_1") (pintype "passive"))
      (node (ref "C70") (pin "1") (pinfunction "1_1") (pintype "passive"))
      (node (ref "C74") (pin "2") (pinfunction "2_2") (pintype "passive"))
      (node (ref "C75") (pin "1") (pinfunction "1_1") (pintype "passive"))
      (node (ref "C76") (pin "2") (pinfunction "2_2") (pintype "passive"))
      (node (ref "C77") (pin "1") (pinfunction "1_1") (pintype "passive"))
      (node (ref "C8") (pin "1") (pinfunction "1_1") (pintype "passive"))
      (node (ref "C80") (pin "1") (pinfunction "1_1") (pintype "passive"))
      (node (ref "C81") (pin "1") (pinfunction "1_1") (pintype "passive"))
      (node (ref "C82") (pin "1") (pinfunction "1_1") (pintype "passive"))
      (node (ref "C83") (pin "1") (pinfunction "1_1") (pintype "passive"))
      (node (ref "C84") (pin "1") (pinfunction "1_1") (pintype "passive"))
      (node (ref "C85") (pin "1") (pinfunction "1_1") (pintype "passive"))
      (node (ref "C86") (pin "1") (pinfunction "1_1") (pintype "passive"))
      (node (ref "C87") (pin "1") (pinfunction "1_1") (pintype "passive"))
      (node (ref "C88") (pin "1") (pinfunction "1_1") (pintype "passive"))
      (node (ref "C89") (pin "1") (pinfunction "1_1") (pintype "passive"))
      (node (ref "C90") (pin "1") (pinfunction "1_1") (pintype "passive"))
      (node (ref "C91") (pin "1") (pinfunction "1_1") (pintype "passive"))
      (node (ref "C92") (pin "1") (pinfunction "1_1") (pintype "passive"))
      (node (ref "C93") (pin "1") (pinfunction "1_1") (pintype "passive"))
      (node (ref "C94") (pin "1") (pinfunction "1_1") (pintype "passive"))
      (node (ref "C95") (pin "1") (pinfunction "1_1") (pintype "passive"))
      (node (ref "C96") (pin "1") (pinfunction "1_1") (pintype "passive"))
      (node (ref "C97") (pin "1") (pinfunction "1_1") (pintype "passive"))
      (node (ref "C98") (pin "1") (pinfunction "1_1") (pintype "passive"))
      (node (ref "C99") (pin "1") (pinfunction "1_1") (pintype "passive"))
      (node (ref "J1") (pin "2") (pinfunction "TCT_2") (pintype "passive"))
      (node (ref "J1") (pin "5") (pinfunction "RCT_5") (pintype "passive"))
      (node (ref "L1") (pin "2") (pinfunction "2_2") (pintype "passive"))
      (node (ref "P1") (pin "1") (pinfunction "1_1") (pintype "passive"))
      (node (ref "P3") (pin "1") (pinfunction "1_1") (pintype "passive"))
      (node (ref "P9") (pin "4") (pinfunction "4_4") (pintype "passive"))
      (node (ref "P9") (pin "5") (pinfunction "5_5") (pintype "passive"))
      (node (ref "R10") (pin "2") (pinfunction "2_2") (pintype "passive"))
      (node (ref "R11") (pin "2") (pinfunction "2_2") (pintype "passive"))
      (node (ref "R12") (pin "2") (pinfunction "2_2") (pintype "passive"))
      (node (ref "R15") (pin "2") (pinfunction "2_2") (pintype "passive"))
      (node (ref "R16") (pin "2") (pinfunction "2_2") (pintype "passive"))
      (node (ref "R17") (pin "2") (pinfunction "2_2") (pintype "passive"))
      (node (ref "R18") (pin "1") (pinfunction "1_1") (pintype "passive"))
      (node (ref "R22") (pin "1") (pinfunction "1_1") (pintype "passive"))
      (node (ref "R23") (pin "1") (pinfunction "1_1") (pintype "passive"))
      (node (ref "R27") (pin "2") (pinfunction "2_2") (pintype "passive"))
      (node (ref "R28") (pin "1") (pinfunction "1_1") (pintype "passive"))
      (node (ref "R29") (pin "1") (pinfunction "1_1") (pintype "passive"))
      (node (ref "R3") (pin "2") (pinfunction "2_2") (pintype "passive"))
      (node (ref "R30") (pin "2") (pinfunction "2_2") (pintype "passive"))
      (node (ref "R34") (pin "2") (pinfunction "2_2") (pintype "passive"))
      (node (ref "R41") (pin "2") (pinfunction "2_2") (pintype "passive"))
      (node (ref "R42") (pin "2") (pinfunction "2_2") (pintype "passive"))
      (node (ref "R43") (pin "2") (pinfunction "2_2") (pintype "passive"))
      (node (ref "R44") (pin "2") (pinfunction "2_2") (pintype "passive"))
      (node (ref "R45") (pin "2") (pinfunction "2_2") (pintype "passive"))
      (node (ref "R46") (pin "2") (pinfunction "2_2") (pintype "passive"))
      (node (ref "R49") (pin "2") (pinfunction "2_2") (pintype "passive"))
      (node (ref "R5") (pin "2") (pinfunction "2_2") (pintype "passive"))
      (node (ref "R51") (pin "2") (pinfunction "2_2") (pintype "passive"))
      (node (ref "R59") (pin "2") (pinfunction "2_2") (pintype "passive"))
      (node (ref "R63") (pin "2") (pinfunction "2_2") (pintype "passive"))
      (node (ref "R69") (pin "2") (pinfunction "2_2") (pintype "passive"))
      (node (ref "R7") (pin "2") (pinfunction "2_2") (pintype "passive"))
      (node (ref "R70") (pin "2") (pinfunction "2_2") (pintype "passive"))
      (node (ref "R8") (pin "2") (pinfunction "2_2") (pintype "passive"))
      (node (ref "R9") (pin "2") (pinfunction "2_2") (pintype "passive"))
      (node (ref "REG_3V3") (pin "2") (pinfunction "Vout_2") (pintype "output"))
      (node (ref "REG_5V") (pin "2") (pinfunction "Vout_2") (pintype "output"))
      (node (ref "U1") (pin "111") (pinfunction "VDDIOP_111") (pintype "power_in"))
      (node (ref "U1") (pin "129") (pinfunction "VDDIOP_129") (pintype "power_in"))
      (node (ref "U1") (pin "131") (pinfunction "VDDIOM_131") (pintype "power_in"))
      (node (ref "U1") (pin "146") (pinfunction "VDDIOM_146") (pintype "power_in"))
      (node (ref "U1") (pin "164") (pinfunction "VDDIOM_164") (pintype "power_in"))
      (node (ref "U1") (pin "183") (pinfunction "VDDIOM_183") (pintype "power_in"))
      (node (ref "U1") (pin "199") (pinfunction "VDDIOM_199") (pintype "power_in"))
      (node (ref "U1") (pin "26") (pinfunction "VDDIOM_26") (pintype "power_in"))
      (node (ref "U1") (pin "40") (pinfunction "VDDIOP_40") (pintype "power_in"))
      (node (ref "U1") (pin "56") (pinfunction "VDDIOP_56") (pintype "power_in"))
      (node (ref "U1") (pin "7") (pinfunction "VDDIOM_7") (pintype "power_in"))
      (node (ref "U1") (pin "75") (pinfunction "VDDIOP_75") (pintype "power_in"))
      (node (ref "U1") (pin "93") (pinfunction "VDDIOP_93") (pintype "power_in"))
      (node (ref "U11") (pin "1") (pinfunction "VCC_1") (pintype "power_in"))
      (node (ref "U11") (pin "15") (pinfunction "ENABLE_D_15") (pintype "input"))
      (node (ref "U11") (pin "2") (pinfunction "ENABLE_A_2") (pintype "input"))
      (node (ref "U11") (pin "7") (pinfunction "ENABLE_B_7") (pintype "input"))
      (node (ref "U11") (pin "9") (pinfunction "ENABLE_C_9") (pintype "input"))
      (node (ref "U13") (pin "20") (pinfunction "VCC_20") (pintype "power_in"))
      (node (ref "U15") (pin "7") (pinfunction "WP_7") (pintype "input"))
      (node (ref "U15") (pin "8") (pinfunction "VCC_8") (pintype "power_in"))
      (node (ref "U16") (pin "22") (pinfunction "AVDD33_22") (pintype "power_in"))
      (node (ref "U16") (pin "32") (pinfunction "IOVDD33_32") (pintype "power_in"))
      (node (ref "U16") (pin "48") (pinfunction "IOVDD33_48") (pintype "power_in"))
      (node (ref "U17") (pin "14") (pinfunction "DVDD_14") (pintype "power_in"))
      (node (ref "U18") (pin "18") (pinfunction "Vcc33_18") (pintype "power_in"))
      (node (ref "U18") (pin "31") (pinfunction "Vcc33_31") (pintype "power_in"))
      (node (ref "U18") (pin "42") (pinfunction "Vcc33_42") (pintype "power_in"))
      (node (ref "U18") (pin "7") (pinfunction "Vcc33_7") (pintype "power_in"))
      (node (ref "U19") (pin "1") (pinfunction "1DIR_1") (pintype "input"))
      (node (ref "U19") (pin "18") (pinfunction "Vcc33_18") (pintype "power_in"))
      (node (ref "U19") (pin "24") (pinfunction "2DIR_24") (pintype "input"))
      (node (ref "U19") (pin "26") (pinfunction "2A8_26") (pintype "bidirectional"))
      (node (ref "U19") (pin "27") (pinfunction "2A7_27") (pintype "bidirectional"))
      (node (ref "U19") (pin "29") (pinfunction "2A6_29") (pintype "bidirectional"))
      (node (ref "U19") (pin "30") (pinfunction "2A5_30") (pintype "bidirectional"))
      (node (ref "U19") (pin "31") (pinfunction "Vcc33_31") (pintype "power_in"))
      (node (ref "U19") (pin "32") (pinfunction "2A4_32") (pintype "bidirectional"))
      (node (ref "U19") (pin "33") (pinfunction "2A3_33") (pintype "bidirectional"))
      (node (ref "U19") (pin "42") (pinfunction "Vcc33_42") (pintype "power_in"))
      (node (ref "U19") (pin "7") (pinfunction "Vcc33_7") (pintype "power_in"))
      (node (ref "U2") (pin "1") (pinfunction "1DIR_1") (pintype "input"))
      (node (ref "U2") (pin "18") (pinfunction "Vcc33_18") (pintype "power_in"))
      (node (ref "U2") (pin "24") (pinfunction "2DIR_24") (pintype "input"))
      (node (ref "U2") (pin "31") (pinfunction "Vcc33_31") (pintype "power_in"))
      (node (ref "U2") (pin "42") (pinfunction "Vcc33_42") (pintype "power_in"))
      (node (ref "U2") (pin "7") (pinfunction "Vcc33_7") (pintype "power_in"))
      (node (ref "U20") (pin "1") (pinfunction "VCC_1") (pintype "power_in"))
      (node (ref "U20") (pin "30") (pinfunction "VCC_30") (pintype "power_in"))
      (node (ref "U21") (pin "1") (pinfunction "1DIR_1") (pintype "input"))
      (node (ref "U21") (pin "18") (pinfunction "Vcc33_18") (pintype "power_in"))
      (node (ref "U21") (pin "24") (pinfunction "2DIR_24") (pintype "input"))
      (node (ref "U21") (pin "26") (pinfunction "2A8_26") (pintype "bidirectional"))
      (node (ref "U21") (pin "27") (pinfunction "2A7_27") (pintype "bidirectional"))
      (node (ref "U21") (pin "29") (pinfunction "2A6_29") (pintype "bidirectional"))
      (node (ref "U21") (pin "30") (pinfunction "2A5_30") (pintype "bidirectional"))
      (node (ref "U21") (pin "31") (pinfunction "Vcc33_31") (pintype "power_in"))
      (node (ref "U21") (pin "32") (pinfunction "2A4_32") (pintype "bidirectional"))
      (node (ref "U21") (pin "33") (pinfunction "2A3_33") (pintype "bidirectional"))
      (node (ref "U21") (pin "42") (pinfunction "Vcc33_42") (pintype "power_in"))
      (node (ref "U21") (pin "7") (pinfunction "Vcc33_7") (pintype "power_in"))
      (node (ref "U3") (pin "2") (pinfunction "VCC_2") (pintype "power_in"))
      (node (ref "U4") (pin "18") (pinfunction "Vcc33_18") (pintype "power_in"))
      (node (ref "U4") (pin "31") (pinfunction "Vcc33_31") (pintype "power_in"))
      (node (ref "U4") (pin "42") (pinfunction "Vcc33_42") (pintype "power_in"))
      (node (ref "U4") (pin "7") (pinfunction "Vcc33_7") (pintype "power_in"))
      (node (ref "U5") (pin "12") (pinfunction "VCC_12") (pintype "power_in"))
      (node (ref "U5") (pin "34") (pinfunction "VCC_34") (pintype "power_in"))
      (node (ref "U6") (pin "11") (pinfunction "VCC_11") (pintype "power_in"))
      (node (ref "U6") (pin "33") (pinfunction "VCC_33") (pintype "power_in"))
      (node (ref "U7") (pin "32") (pinfunction "VCC_32") (pintype "power_in"))
      (node (ref "U8") (pin "1") (pinfunction "1DIR_1") (pintype "input"))
      (node (ref "U8") (pin "18") (pinfunction "Vcc33_18") (pintype "power_in"))
      (node (ref "U8") (pin "24") (pinfunction "2DIR_24") (pintype "input"))
      (node (ref "U8") (pin "31") (pinfunction "Vcc33_31") (pintype "power_in"))
      (node (ref "U8") (pin "42") (pinfunction "Vcc33_42") (pintype "power_in"))
      (node (ref "U8") (pin "7") (pinfunction "Vcc33_7") (pintype "power_in"))
      (node (ref "U9") (pin "1") (pinfunction "VCC_1") (pintype "power_in"))
      (node (ref "U9") (pin "15") (pinfunction "ENABLE_D_15") (pintype "input"))
      (node (ref "U9") (pin "2") (pinfunction "ENABLE_A_2") (pintype "input"))
      (node (ref "U9") (pin "7") (pinfunction "ENABLE_B_7") (pintype "input"))
      (node (ref "U9") (pin "9") (pinfunction "ENABLE_C_9") (pintype "input"))
    )
    (net (code "180") (name "12V") (class "Default")
      (node (ref "C71") (pin "2") (pinfunction "2_2") (pintype "passive"))
      (node (ref "J4") (pin "VCC") (pinfunction "VCC_VCC") (pintype "passive"))
      (node (ref "P9") (pin "6") (pinfunction "6_6") (pintype "passive"))
      (node (ref "R58") (pin "1") (pinfunction "1_1") (pintype "passive"))
      (node (ref "R60") (pin "2") (pinfunction "2_2") (pintype "passive"))
      (node (ref "R61") (pin "2") (pinfunction "2_2") (pintype "passive"))
      (node (ref "R62") (pin "2") (pinfunction "2_2") (pintype "passive"))
      (node (ref "R68") (pin "2") (pinfunction "2_2") (pintype "passive"))
    )
    (net (code "181") (name "GND") (class "Default")
      (node (ref "C1") (pin "2") (pinfunction "2_2") (pintype "passive"))
      (node (ref "C10") (pin "2") (pinfunction "2_2") (pintype "passive"))
      (node (ref "C100") (pin "2") (pinfunction "2_2") (pintype "passive"))
      (node (ref "C101") (pin "2") (pinfunction "2_2") (pintype "passive"))
      (node (ref "C102") (pin "2") (pinfunction "2_2") (pintype "passive"))
      (node (ref "C103") (pin "2") (pinfunction "2_2") (pintype "passive"))
      (node (ref "C104") (pin "2") (pinfunction "2_2") (pintype "passive"))
      (node (ref "C105") (pin "2") (pinfunction "2_2") (pintype "passive"))
      (node (ref "C106") (pin "2") (pinfunction "2_2") (pintype "passive"))
      (node (ref "C107") (pin "2") (pinfunction "2_2") (pintype "passive"))
      (node (ref "C11") (pin "1") (pinfunction "1_1") (pintype "passive"))
      (node (ref "C12") (pin "2") (pinfunction "2_2") (pintype "passive"))
      (node (ref "C13") (pin "1") (pinfunction "1_1") (pintype "passive"))
      (node (ref "C14") (pin "2") (pinfunction "2_2") (pintype "passive"))
      (node (ref "C16") (pin "2") (pinfunction "2_2") (pintype "passive"))
      (node (ref "C18") (pin "2") (pinfunction "2_2") (pintype "passive"))
      (node (ref "C2") (pin "2") (pinfunction "2_2") (pintype "passive"))
      (node (ref "C20") (pin "2") (pinfunction "2_2") (pintype "passive"))
      (node (ref "C21") (pin "2") (pinfunction "2_2") (pintype "passive"))
      (node (ref "C24") (pin "2") (pinfunction "2_2") (pintype "passive"))
      (node (ref "C25") (pin "2") (pinfunction "2_2") (pintype "passive"))
      (node (ref "C3") (pin "2") (pinfunction "2_2") (pintype "passive"))
      (node (ref "C32") (pin "2") (pinfunction "2_2") (pintype "passive"))
      (node (ref "C33") (pin "2") (pinfunction "2_2") (pintype "passive"))
      (node (ref "C34") (pin "2") (pinfunction "2_2") (pintype "passive"))
      (node (ref "C35") (pin "2") (pinfunction "2_2") (pintype "passive"))
      (node (ref "C36") (pin "2") (pinfunction "2_2") (pintype "passive"))
      (node (ref "C37") (pin "2") (pinfunction "2_2") (pintype "passive"))
      (node (ref "C38") (pin "2") (pinfunction "2_2") (pintype "passive"))
      (node (ref "C39") (pin "2") (pinfunction "2_2") (pintype "passive"))
      (node (ref "C4") (pin "2") (pinfunction "2_2") (pintype "passive"))
      (node (ref "C41") (pin "2") (pinfunction "2_2") (pintype "passive"))
      (node (ref "C43") (pin "2") (pinfunction "2_2") (pintype "passive"))
      (node (ref "C44") (pin "1") (pinfunction "1_1") (pintype "passive"))
      (node (ref "C45") (pin "1") (pinfunction "1_1") (pintype "passive"))
      (node (ref "C46") (pin "1") (pinfunction "1_1") (pintype "passive"))
      (node (ref "C47") (pin "1") (pinfunction "1_1") (pintype "passive"))
      (node (ref "C48") (pin "1") (pinfunction "1_1") (pintype "passive"))
      (node (ref "C49") (pin "2") (pinfunction "2_2") (pintype "passive"))
      (node (ref "C5") (pin "1") (pinfunction "1_1") (pintype "passive"))
      (node (ref "C50") (pin "2") (pinfunction "2_2") (pintype "passive"))
      (node (ref "C51") (pin "2") (pinfunction "2_2") (pintype "passive"))
      (node (ref "C52") (pin "2") (pinfunction "2_2") (pintype "passive"))
      (node (ref "C53") (pin "2") (pinfunction "2_2") (pintype "passive"))
      (node (ref "C54") (pin "2") (pinfunction "2_2") (pintype "passive"))
      (node (ref "C55") (pin "2") (pinfunction "2_2") (pintype "passive"))
      (node (ref "C56") (pin "2") (pinfunction "2_2") (pintype "passive"))
      (node (ref "C57") (pin "2") (pinfunction "2_2") (pintype "passive"))
      (node (ref "C58") (pin "2") (pinfunction "2_2") (pintype "passive"))
      (node (ref "C59") (pin "2") (pinfunction "2_2") (pintype "passive"))
      (node (ref "C6") (pin "2") (pinfunction "2_2") (pintype "passive"))
      (node (ref "C60") (pin "2") (pinfunction "2_2") (pintype "passive"))
      (node (ref "C61") (pin "2") (pinfunction "2_2") (pintype "passive"))
      (node (ref "C63") (pin "2") (pinfunction "2_2") (pintype "passive"))
      (node (ref "C65") (pin "2") (pinfunction "2_2") (pintype "passive"))
      (node (ref "C66") (pin "2") (pinfunction "2_2") (pintype "passive"))
      (node (ref "C67") (pin "2") (pinfunction "2_2") (pintype "passive"))
      (node (ref "C68") (pin "2") (pinfunction "2_2") (pintype "passive"))
      (node (ref "C69") (pin "2") (pinfunction "2_2") (pintype "passive"))
      (node (ref "C7") (pin "1") (pinfunction "1_1") (pintype "passive"))
      (node (ref "C70") (pin "2") (pinfunction "2_2") (pintype "passive"))
      (node (ref "C71") (pin "1") (pinfunction "1_1") (pintype "passive"))
      (node (ref "C72") (pin "1") (pinfunction "1_1") (pintype "passive"))
      (node (ref "C74") (pin "1") (pinfunction "1_1") (pintype "passive"))
      (node (ref "C75") (pin "2") (pinfunction "2_2") (pintype "passive"))
      (node (ref "C76") (pin "1") (pinfunction "1_1") (pintype "passive"))
      (node (ref "C77") (pin "2") (pinfunction "2_2") (pintype "passive"))
      (node (ref "C78") (pin "1") (pinfunction "1_1") (pintype "passive"))
      (node (ref "C79") (pin "1") (pinfunction "1_1") (pintype "passive"))
      (node (ref "C8") (pin "2") (pinfunction "2_2") (pintype "passive"))
      (node (ref "C80") (pin "2") (pinfunction "2_2") (pintype "passive"))
      (node (ref "C81") (pin "2") (pinfunction "2_2") (pintype "passive"))
      (node (ref "C82") (pin "2") (pinfunction "2_2") (pintype "passive"))
      (node (ref "C83") (pin "2") (pinfunction "2_2") (pintype "passive"))
      (node (ref "C84") (pin "2") (pinfunction "2_2") (pintype "passive"))
      (node (ref "C85") (pin "2") (pinfunction "2_2") (pintype "passive"))
      (node (ref "C86") (pin "2") (pinfunction "2_2") (pintype "passive"))
      (node (ref "C87") (pin "2") (pinfunction "2_2") (pintype "passive"))
      (node (ref "C88") (pin "2") (pinfunction "2_2") (pintype "passive"))
      (node (ref "C89") (pin "2") (pinfunction "2_2") (pintype "passive"))
      (node (ref "C9") (pin "1") (pinfunction "1_1") (pintype "passive"))
      (node (ref "C90") (pin "2") (pinfunction "2_2") (pintype "passive"))
      (node (ref "C91") (pin "2") (pinfunction "2_2") (pintype "passive"))
      (node (ref "C92") (pin "2") (pinfunction "2_2") (pintype "passive"))
      (node (ref "C93") (pin "2") (pinfunction "2_2") (pintype "passive"))
      (node (ref "C94") (pin "2") (pinfunction "2_2") (pintype "passive"))
      (node (ref "C95") (pin "2") (pinfunction "2_2") (pintype "passive"))
      (node (ref "C96") (pin "2") (pinfunction "2_2") (pintype "passive"))
      (node (ref "C97") (pin "2") (pinfunction "2_2") (pintype "passive"))
      (node (ref "C98") (pin "2") (pinfunction "2_2") (pintype "passive"))
      (node (ref "C99") (pin "2") (pinfunction "2_2") (pintype "passive"))
      (node (ref "DISP1") (pin "11") (pinfunction "VSS_11") (pintype "passive"))
      (node (ref "J1") (pin "8") (pinfunction "GND_8") (pintype "power_in"))
      (node (ref "J4") (pin "GND") (pinfunction "GND_GND") (pintype "passive"))
      (node (ref "L2") (pin "2") (pinfunction "2_2") (pintype "passive"))
      (node (ref "L3") (pin "2") (pinfunction "2_2") (pintype "passive"))
      (node (ref "L4") (pin "2") (pinfunction "2_2") (pintype "passive"))
      (node (ref "L5") (pin "K") (pintype "passive"))
      (node (ref "L6") (pin "K") (pintype "passive"))
      (node (ref "L7") (pin "K") (pintype "passive"))
      (node (ref "P1") (pin "10") (pinfunction "10_10") (pintype "passive"))
      (node (ref "P1") (pin "12") (pinfunction "12_12") (pintype "passive"))
      (node (ref "P1") (pin "14") (pinfunction "14_14") (pintype "passive"))
      (node (ref "P1") (pin "16") (pinfunction "16_16") (pintype "passive"))
      (node (ref "P1") (pin "18") (pinfunction "18_18") (pintype "passive"))
      (node (ref "P1") (pin "20") (pinfunction "20_20") (pintype "passive"))
      (node (ref "P1") (pin "4") (pinfunction "4_4") (pintype "passive"))
      (node (ref "P1") (pin "6") (pinfunction "6_6") (pintype "passive"))
      (node (ref "P1") (pin "8") (pinfunction "8_8") (pintype "passive"))
      (node (ref "P3") (pin "3") (pinfunction "3_3") (pintype "passive"))
      (node (ref "P5") (pin "15") (pinfunction "15_15") (pintype "passive"))
      (node (ref "P9") (pin "1") (pinfunction "1_1") (pintype "passive"))
      (node (ref "Q1") (pin "2") (pinfunction "S_2") (pintype "passive"))
      (node (ref "Q2") (pin "S") (pinfunction "S_S") (pintype "passive"))
      (node (ref "R13") (pin "2") (pinfunction "2_2") (pintype "passive"))
      (node (ref "R14") (pin "2") (pinfunction "2_2") (pintype "passive"))
      (node (ref "R19") (pin "1") (pinfunction "1_1") (pintype "passive"))
      (node (ref "R20") (pin "1") (pinfunction "1_1") (pintype "passive"))
      (node (ref "R21") (pin "1") (pinfunction "1_1") (pintype "passive"))
      (node (ref "R35") (pin "2") (pinfunction "2_2") (pintype "passive"))
      (node (ref "R36") (pin "1") (pinfunction "1_1") (pintype "passive"))
      (node (ref "R37") (pin "1") (pinfunction "1_1") (pintype "passive"))
      (node (ref "R38") (pin "1") (pinfunction "1_1") (pintype "passive"))
      (node (ref "R39") (pin "2") (pinfunction "2_2") (pintype "passive"))
      (node (ref "R4") (pin "1") (pinfunction "1_1") (pintype "passive"))
      (node (ref "R40") (pin "2") (pinfunction "2_2") (pintype "passive"))
      (node (ref "R48") (pin "1") (pinfunction "1_1") (pintype "passive"))
      (node (ref "R50") (pin "1") (pinfunction "1_1") (pintype "passive"))
      (node (ref "R52") (pin "1") (pinfunction "1_1") (pintype "passive"))
      (node (ref "R54") (pin "1") (pinfunction "1_1") (pintype "passive"))
      (node (ref "R6") (pin "2") (pinfunction "2_2") (pintype "passive"))
      (node (ref "R64") (pin "1") (pinfunction "1_1") (pintype "passive"))
      (node (ref "R65") (pin "2") (pinfunction "2_2") (pintype "passive"))
      (node (ref "R66") (pin "2") (pinfunction "2_2") (pintype "passive"))
      (node (ref "SW_HANGUP") (pin "2") (pintype "passive"))
      (node (ref "U1") (pin "112") (pinfunction "GND_112") (pintype "power_in"))
      (node (ref "U1") (pin "113") (pinfunction "TST0_113") (pintype "input"))
      (node (ref "U1") (pin "114") (pinfunction "TST1_114") (pintype "input"))
      (node (ref "U1") (pin "117") (pinfunction "GND_117") (pintype "power_in"))
      (node (ref "U1") (pin "130") (pinfunction "GND_130") (pintype "power_in"))
      (node (ref "U1") (pin "132") (pinfunction "GND_132") (pintype "power_in"))
      (node (ref "U1") (pin "147") (pinfunction "GND_147") (pintype "power_in"))
      (node (ref "U1") (pin "153") (pinfunction "GND_153") (pintype "power_in"))
      (node (ref "U1") (pin "165") (pinfunction "GND_165") (pintype "power_in"))
      (node (ref "U1") (pin "184") (pinfunction "GND_184") (pintype "power_in"))
      (node (ref "U1") (pin "189") (pinfunction "GND_189") (pintype "power_in"))
      (node (ref "U1") (pin "20") (pinfunction "GND_20") (pintype "power_in"))
      (node (ref "U1") (pin "200") (pinfunction "GND_200") (pintype "power_in"))
      (node (ref "U1") (pin "27") (pinfunction "GND_27") (pintype "power_in"))
      (node (ref "U1") (pin "41") (pinfunction "GND_41") (pintype "power_in"))
      (node (ref "U1") (pin "57") (pinfunction "GND_57") (pintype "power_in"))
      (node (ref "U1") (pin "63") (pinfunction "GND_63") (pintype "power_in"))
      (node (ref "U1") (pin "76") (pinfunction "GND_76") (pintype "power_in"))
      (node (ref "U1") (pin "8") (pinfunction "GND_8") (pintype "power_in"))
      (node (ref "U1") (pin "94") (pinfunction "GND_94") (pintype "power_in"))
      (node (ref "U11") (pin "8") (pinfunction "VSS_8") (pintype "power_in"))
      (node (ref "U13") (pin "10") (pinfunction "GND_10") (pintype "power_in"))
      (node (ref "U13") (pin "14") (pinfunction "OE_14") (pintype "input"))
      (node (ref "U15") (pin "1") (pinfunction "A0_1") (pintype "input"))
      (node (ref "U15") (pin "2") (pinfunction "A1_2") (pintype "input"))
      (node (ref "U15") (pin "3") (pinfunction "A2_3") (pintype "input"))
      (node (ref "U15") (pin "4") (pinfunction "GND_4") (pintype "power_in"))
      (node (ref "U16") (pin "15") (pinfunction "AGND_15") (pintype "power_in"))
      (node (ref "U16") (pin "19") (pinfunction "AGND_19") (pintype "power_in"))
      (node (ref "U16") (pin "35") (pinfunction "IOGND_35") (pintype "power_in"))
      (node (ref "U16") (pin "36") (pinfunction "DGND_36") (pintype "power_in"))
      (node (ref "U16") (pin "47") (pinfunction "IOGND_47") (pintype "power_in"))
      (node (ref "U17") (pin "1") (pinfunction "MICMUTE_1") (pintype "input"))
      (node (ref "U17") (pin "15") (pinfunction "DGND_15") (pintype "power_in"))
      (node (ref "U17") (pin "20") (pinfunction "EARMUTE_20") (pintype "input"))
      (node (ref "U18") (pin "10") (pinfunction "GND_10") (pintype "power_in"))
      (node (ref "U18") (pin "15") (pinfunction "GND_15") (pintype "power_in"))
      (node (ref "U18") (pin "21") (pinfunction "GND_21") (pintype "power_in"))
      (node (ref "U18") (pin "28") (pinfunction "GND_28") (pintype "power_in"))
      (node (ref "U18") (pin "34") (pinfunction "GND_34") (pintype "power_in"))
      (node (ref "U18") (pin "39") (pinfunction "GND_39") (pintype "power_in"))
      (node (ref "U18") (pin "4") (pinfunction "GND_4") (pintype "power_in"))
      (node (ref "U18") (pin "45") (pinfunction "GND_45") (pintype "power_in"))
      (node (ref "U19") (pin "10") (pinfunction "GND_10") (pintype "power_in"))
      (node (ref "U19") (pin "15") (pinfunction "GND_15") (pintype "power_in"))
      (node (ref "U19") (pin "21") (pinfunction "GND_21") (pintype "power_in"))
      (node (ref "U19") (pin "28") (pinfunction "GND_28") (pintype "power_in"))
      (node (ref "U19") (pin "34") (pinfunction "GND_34") (pintype "power_in"))
      (node (ref "U19") (pin "39") (pinfunction "GND_39") (pintype "power_in"))
      (node (ref "U19") (pin "4") (pinfunction "GND_4") (pintype "power_in"))
      (node (ref "U19") (pin "45") (pinfunction "GND_45") (pintype "power_in"))
      (node (ref "U2") (pin "10") (pinfunction "GND_10") (pintype "power_in"))
      (node (ref "U2") (pin "15") (pinfunction "GND_15") (pintype "power_in"))
      (node (ref "U2") (pin "21") (pinfunction "GND_21") (pintype "power_in"))
      (node (ref "U2") (pin "25") (pinfunction "2OE_25") (pintype "input"))
      (node (ref "U2") (pin "28") (pinfunction "GND_28") (pintype "power_in"))
      (node (ref "U2") (pin "34") (pinfunction "GND_34") (pintype "power_in"))
      (node (ref "U2") (pin "39") (pinfunction "GND_39") (pintype "power_in"))
      (node (ref "U2") (pin "4") (pinfunction "GND_4") (pintype "power_in"))
      (node (ref "U2") (pin "45") (pinfunction "GND_45") (pintype "power_in"))
      (node (ref "U2") (pin "48") (pinfunction "1OE_48") (pintype "input"))
      (node (ref "U20") (pin "22") (pinfunction "GND_22") (pintype "power_in"))
      (node (ref "U20") (pin "9") (pinfunction "GND_9") (pintype "power_in"))
      (node (ref "U21") (pin "10") (pinfunction "GND_10") (pintype "power_in"))
      (node (ref "U21") (pin "15") (pinfunction "GND_15") (pintype "power_in"))
      (node (ref "U21") (pin "21") (pinfunction "GND_21") (pintype "power_in"))
      (node (ref "U21") (pin "28") (pinfunction "GND_28") (pintype "power_in"))
      (node (ref "U21") (pin "34") (pinfunction "GND_34") (pintype "power_in"))
      (node (ref "U21") (pin "39") (pinfunction "GND_39") (pintype "power_in"))
      (node (ref "U21") (pin "4") (pinfunction "GND_4") (pintype "power_in"))
      (node (ref "U21") (pin "45") (pinfunction "GND_45") (pintype "power_in"))
      (node (ref "U3") (pin "3") (pinfunction "GND_3") (pintype "power_in"))
      (node (ref "U4") (pin "10") (pinfunction "GND_10") (pintype "power_in"))
      (node (ref "U4") (pin "15") (pinfunction "GND_15") (pintype "power_in"))
      (node (ref "U4") (pin "21") (pinfunction "GND_21") (pintype "power_in"))
      (node (ref "U4") (pin "25") (pinfunction "2OE_25") (pintype "input"))
      (node (ref "U4") (pin "28") (pinfunction "GND_28") (pintype "power_in"))
      (node (ref "U4") (pin "34") (pinfunction "GND_34") (pintype "power_in"))
      (node (ref "U4") (pin "39") (pinfunction "GND_39") (pintype "power_in"))
      (node (ref "U4") (pin "4") (pinfunction "GND_4") (pintype "power_in"))
      (node (ref "U4") (pin "45") (pinfunction "GND_45") (pintype "power_in"))
      (node (ref "U4") (pin "48") (pinfunction "1OE_48") (pintype "input"))
      (node (ref "U5") (pin "1") (pinfunction "GND_1") (pintype "power_in"))
      (node (ref "U5") (pin "23") (pinfunction "GND_23") (pintype "power_in"))
      (node (ref "U6") (pin "12") (pinfunction "GND_12") (pintype "power_in"))
      (node (ref "U6") (pin "34") (pinfunction "GND_34") (pintype "power_in"))
      (node (ref "U7") (pin "16") (pinfunction "GND_16") (pintype "power_in"))
      (node (ref "U8") (pin "10") (pinfunction "GND_10") (pintype "power_in"))
      (node (ref "U8") (pin "15") (pinfunction "GND_15") (pintype "power_in"))
      (node (ref "U8") (pin "21") (pinfunction "GND_21") (pintype "power_in"))
      (node (ref "U8") (pin "25") (pinfunction "2OE_25") (pintype "input"))
      (node (ref "U8") (pin "28") (pinfunction "GND_28") (pintype "power_in"))
      (node (ref "U8") (pin "34") (pinfunction "GND_34") (pintype "power_in"))
      (node (ref "U8") (pin "39") (pinfunction "GND_39") (pintype "power_in"))
      (node (ref "U8") (pin "4") (pinfunction "GND_4") (pintype "power_in"))
      (node (ref "U8") (pin "45") (pinfunction "GND_45") (pintype "power_in"))
      (node (ref "U8") (pin "48") (pinfunction "1OE_48") (pintype "input"))
      (node (ref "U9") (pin "8") (pinfunction "VSS_8") (pintype "power_in"))
    )
    (net (code "182") (name "Net-(C26-Pad1)") (class "Default")
      (node (ref "C26") (pin "1") (pinfunction "1_1") (pintype "passive"))
      (node (ref "R1") (pin "1") (pinfunction "1_1") (pintype "passive"))
    )
    (net (code "183") (name "Net-(C31-Pad1)") (class "Default")
      (node (ref "C31") (pin "1") (pinfunction "1_1") (pintype "passive"))
      (node (ref "R2") (pin "1") (pinfunction "1_1") (pintype "passive"))
    )
    (net (code "184") (name "Net-(C62-Pad2)") (class "Default")
      (node (ref "C62") (pin "2") (pinfunction "2_2") (pintype "passive"))
      (node (ref "R26") (pin "1") (pinfunction "1_1") (pintype "passive"))
    )
    (net (code "185") (name "Net-(C64-Pad2)") (class "Default")
      (node (ref "C64") (pin "2") (pinfunction "2_2") (pintype "passive"))
      (node (ref "R32") (pin "1") (pinfunction "1_1") (pintype "passive"))
    )
    (net (code "186") (name "Net-(DISP1-A0)") (class "Default")
      (node (ref "DISP1") (pin "15") (pinfunction "A0_15") (pintype "passive"))
      (node (ref "U9") (pin "4") (pinfunction "E_4") (pintype "tri_state"))
    )
    (net (code "187") (name "Net-(DISP1-C1+)") (class "Default")
      (node (ref "C40") (pin "1") (pinfunction "1_1") (pintype "passive"))
      (node (ref "DISP1") (pin "8") (pinfunction "C1+_8") (pintype "passive"))
    )
    (net (code "188") (name "Net-(DISP1-C1-)") (class "Default")
      (node (ref "C40") (pin "2") (pinfunction "2_2") (pintype "passive"))
      (node (ref "DISP1") (pin "9") (pinfunction "C1-_9") (pintype "passive"))
    )
    (net (code "189") (name "Net-(DISP1-C2+)") (class "Default")
      (node (ref "C42") (pin "2") (pinfunction "2_2") (pintype "passive"))
      (node (ref "DISP1") (pin "7") (pinfunction "C2+_7") (pintype "passive"))
    )
    (net (code "190") (name "Net-(DISP1-C2-)") (class "Default")
      (node (ref "C42") (pin "1") (pinfunction "1_1") (pintype "passive"))
      (node (ref "DISP1") (pin "6") (pinfunction "C2-_6") (pintype "passive"))
    )
    (net (code "191") (name "Net-(DISP1-LED_K)") (class "Default")
      (node (ref "DISP1") (pin "19") (pinfunction "LED_K_19") (pintype "passive"))
      (node (ref "Q2") (pin "D") (pinfunction "D_D") (pintype "passive"))
    )
    (net (code "192") (name "Net-(DISP1-SCL)") (class "Default")
      (node (ref "DISP1") (pin "14") (pinfunction "SCL_14") (pintype "passive"))
      (node (ref "U11") (pin "13") (pinfunction "H_13") (pintype "tri_state"))
    )
    (net (code "193") (name "Net-(DISP1-SI)") (class "Default")
      (node (ref "DISP1") (pin "13") (pinfunction "SI_13") (pintype "passive"))
      (node (ref "U11") (pin "11") (pinfunction "G_11") (pintype "tri_state"))
    )
    (net (code "194") (name "Net-(DISP1-V0)") (class "Default")
      (node (ref "C44") (pin "2") (pinfunction "2_2") (pintype "passive"))
      (node (ref "DISP1") (pin "1") (pinfunction "V0_1") (pintype "passive"))
    )
    (net (code "195") (name "Net-(DISP1-V1)") (class "Default")
      (node (ref "C45") (pin "2") (pinfunction "2_2") (pintype "passive"))
      (node (ref "DISP1") (pin "2") (pinfunction "V1_2") (pintype "passive"))
    )
    (net (code "196") (name "Net-(DISP1-V2)") (class "Default")
      (node (ref "C46") (pin "2") (pinfunction "2_2") (pintype "passive"))
      (node (ref "DISP1") (pin "3") (pinfunction "V2_3") (pintype "passive"))
    )
    (net (code "197") (name "Net-(DISP1-V3)") (class "Default")
      (node (ref "C47") (pin "2") (pinfunction "2_2") (pintype "passive"))
      (node (ref "DISP1") (pin "4") (pinfunction "V3_4") (pintype "passive"))
    )
    (net (code "198") (name "Net-(DISP1-V4)") (class "Default")
      (node (ref "C48") (pin "2") (pinfunction "2_2") (pintype "passive"))
      (node (ref "DISP1") (pin "5") (pinfunction "V4_5") (pintype "passive"))
    )
    (net (code "199") (name "Net-(DISP1-VOUT)") (class "Default")
      (node (ref "C39") (pin "1") (pinfunction "1_1") (pintype "passive"))
      (node (ref "DISP1") (pin "10") (pinfunction "VOUT_10") (pintype "passive"))
    )
    (net (code "200") (name "Net-(DISP1-{slash}CS)") (class "Default")
      (node (ref "DISP1") (pin "17") (pinfunction "/CS_17") (pintype "passive"))
      (node (ref "U9") (pin "11") (pinfunction "G_11") (pintype "tri_state"))
    )
    (net (code "201") (name "Net-(DISP1-{slash}RST)") (class "Default")
      (node (ref "DISP1") (pin "16") (pinfunction "/RST_16") (pintype "passive"))
      (node (ref "U9") (pin "5") (pinfunction "F_5") (pintype "tri_state"))
    )
    (net (code "202") (name "Net-(J1-LED1A)") (class "Default")
      (node (ref "J1") (pin "10") (pinfunction "LED1A_10") (pintype "power_in"))
      (node (ref "R20") (pin "2") (pinfunction "2_2") (pintype "passive"))
      (node (ref "U16") (pin "26") (pinfunction "AN_EN/LED_ACT/COL_26") (pintype "bidirectional"))
    )
    (net (code "203") (name "Net-(J1-LED1K)") (class "Default")
      (node (ref "J1") (pin "9") (pinfunction "LED1K_9") (pintype "power_in"))
      (node (ref "R21") (pin "2") (pinfunction "2_2") (pintype "passive"))
    )
    (net (code "204") (name "Net-(J1-LED2A)") (class "Default")
      (node (ref "J1") (pin "12") (pinfunction "LED2A_12") (pintype "power_in"))
      (node (ref "R22") (pin "2") (pinfunction "2_2") (pintype "passive"))
    )
    (net (code "205") (name "Net-(J1-LED2K)") (class "Default")
      (node (ref "J1") (pin "11") (pinfunction "LED2K_11") (pintype "power_in"))
      (node (ref "R18") (pin "2") (pinfunction "2_2") (pintype "passive"))
      (node (ref "U16") (pin "28") (pinfunction "AN_0/LED_LINK_28") (pintype "bidirectional"))
    )
    (net (code "206") (name "Net-(J1-RD+)") (class "Default")
      (node (ref "J1") (pin "4") (pinfunction "RD+_4") (pintype "passive"))
      (node (ref "R43") (pin "1") (pinfunction "1_1") (pintype "passive"))
      (node (ref "U16") (pin "14") (pinfunction "RD+_14") (pintype "input"))
    )
    (net (code "207") (name "Net-(J1-RD-)") (class "Default")
      (node (ref "J1") (pin "6") (pinfunction "RD-_6") (pintype "passive"))
      (node (ref "R44") (pin "1") (pinfunction "1_1") (pintype "passive"))
      (node (ref "U16") (pin "13") (pinfunction "RD-_13") (pintype "input"))
    )
    (net (code "208") (name "Net-(J1-TD+)") (class "Default")
      (node (ref "J1") (pin "1") (pinfunction "TD+_1") (pintype "passive"))
      (node (ref "R41") (pin "1") (pinfunction "1_1") (pintype "passive"))
      (node (ref "U16") (pin "17") (pinfunction "TD+_17") (pintype "output"))
    )
    (net (code "209") (name "Net-(J1-TD-)") (class "Default")
      (node (ref "J1") (pin "3") (pinfunction "TD-_3") (pintype "passive"))
      (node (ref "R42") (pin "1") (pinfunction "1_1") (pintype "passive"))
      (node (ref "U16") (pin "16") (pinfunction "TD-_16") (pintype "output"))
    )
    (net (code "210") (name "Net-(JTAG_SEL-Pad1)") (class "Default")
      (node (ref "JTAG_SEL") (pin "1") (pinfunction "1_1") (pintype "passive"))
      (node (ref "R6") (pin "1") (pinfunction "1_1") (pintype "passive"))
    )
    (net (code "211") (name "Net-(JTAG_SEL-Pad3)") (class "Default")
      (node (ref "JTAG_SEL") (pin "3") (pinfunction "3_3") (pintype "passive"))
      (node (ref "R5") (pin "1") (pinfunction "1_1") (pintype "passive"))
    )
    (net (code "212") (name "Net-(K1-COL1)_1") (class "Default")
      (node (ref "K1") (pin "4") (pinfunction "COL1_4") (pintype "passive"))
      (node (ref "U13") (pin "8") (pinfunction "COL4_8") (pintype "passive"))
    )
    (net (code "213") (name "Net-(K1-COL2)_1") (class "Default")
      (node (ref "K1") (pin "3") (pinfunction "COL2_3") (pintype "passive"))
      (node (ref "U13") (pin "9") (pinfunction "COL3_9") (pintype "passive"))
    )
    (net (code "214") (name "Net-(K1-COL3)_1") (class "Default")
      (node (ref "K1") (pin "2") (pinfunction "COL3_2") (pintype "passive"))
      (node (ref "U13") (pin "11") (pinfunction "COL2_11") (pintype "passive"))
    )
    (net (code "215") (name "Net-(K1-COL4)_1") (class "Default")
      (node (ref "K1") (pin "1") (pinfunction "COL4_1") (pintype "passive"))
      (node (ref "U13") (pin "12") (pinfunction "COL1_12") (pintype "passive"))
    )
    (net (code "216") (name "Net-(K1-ROW1)_1") (class "Default")
      (node (ref "K1") (pin "8") (pinfunction "ROW1_8") (pintype "passive"))
      (node (ref "U13") (pin "5") (pinfunction "ROW5_5") (pintype "passive"))
    )
    (net (code "217") (name "Net-(K1-ROW2)_1") (class "Default")
      (node (ref "K1") (pin "7") (pinfunction "ROW2_7") (pintype "passive"))
      (node (ref "U13") (pin "4") (pinfunction "ROW4_4") (pintype "passive"))
    )
    (net (code "218") (name "Net-(K1-ROW3)_1") (class "Default")
      (node (ref "K1") (pin "6") (pinfunction "ROW3_6") (pintype "passive"))
      (node (ref "U13") (pin "3") (pinfunction "ROW3_3") (pintype "passive"))
    )
    (net (code "219") (name "Net-(K1-ROW4)_1") (class "Default")
      (node (ref "K1") (pin "5") (pinfunction "ROW4_5") (pintype "passive"))
      (node (ref "U13") (pin "2") (pinfunction "ROW2_2") (pintype "passive"))
    )
    (net (code "220") (name "Net-(L5-PadA)") (class "Default")
      (node (ref "L5") (pin "A") (pintype "passive"))
      (node (ref "R68") (pin "1") (pinfunction "1_1") (pintype "passive"))
    )
    (net (code "221") (name "Net-(L6-PadA)") (class "Default")
      (node (ref "L6") (pin "A") (pintype "passive"))
      (node (ref "R69") (pin "1") (pinfunction "1_1") (pintype "passive"))
    )
    (net (code "222") (name "Net-(L7-PadA)") (class "Default")
      (node (ref "L7") (pin "A") (pintype "passive"))
      (node (ref "R70") (pin "1") (pinfunction "1_1") (pintype "passive"))
    )
    (net (code "223") (name "Net-(P1-Pad11)") (class "Default")
      (node (ref "P1") (pin "11") (pinfunction "11_11") (pintype "passive"))
      (node (ref "R8") (pin "1") (pinfunction "1_1") (pintype "passive"))
    )
    (net (code "224") (name "Net-(P1-Pad17)") (class "Default")
      (node (ref "P1") (pin "17") (pinfunction "17_17") (pintype "passive"))
      (node (ref "R13") (pin "1") (pinfunction "1_1") (pintype "passive"))
    )
    (net (code "225") (name "Net-(P1-Pad19)") (class "Default")
      (node (ref "P1") (pin "19") (pinfunction "19_19") (pintype "passive"))
      (node (ref "R14") (pin "1") (pinfunction "1_1") (pintype "passive"))
    )
    (net (code "226") (name "Net-(Q1-D)") (class "Default")
      (node (ref "Q1") (pin "1") (pinfunction "D_1") (pintype "passive"))
      (node (ref "R67") (pin "2") (pinfunction "2_2") (pintype "passive"))
    )
    (net (code "227") (name "Net-(Q1-G)") (class "Default")
      (node (ref "Q1") (pin "3") (pinfunction "G_3") (pintype "passive"))
      (node (ref "R57") (pin "2") (pinfunction "2_2") (pintype "passive"))
    )
    (net (code "228") (name "Net-(R65-Pad1)") (class "Default")
      (node (ref "R65") (pin "1") (pinfunction "1_1") (pintype "passive"))
      (node (ref "SW_RESET") (pin "1") (pintype "passive"))
    )
    (net (code "229") (name "Net-(REG_1V8-GND{slash}Adj)") (class "Default")
      (node (ref "R47") (pin "1") (pinfunction "1_1") (pintype "passive"))
      (node (ref "R48") (pin "2") (pinfunction "2_2") (pintype "passive"))
      (node (ref "REG_1V8") (pin "1") (pinfunction "GND/Adj_1") (pintype "output"))
    )
    (net (code "230") (name "Net-(REG_1V8-Vin)") (class "Default")
      (node (ref "R58") (pin "2") (pinfunction "2_2") (pintype "passive"))
      (node (ref "REG_1V8") (pin "3") (pinfunction "Vin_3") (pintype "output"))
    )
    (net (code "231") (name "Net-(REG_3V-GND{slash}Adj)") (class "Default")
      (node (ref "R53") (pin "1") (pinfunction "1_1") (pintype "passive"))
      (node (ref "R54") (pin "2") (pinfunction "2_2") (pintype "passive"))
      (node (ref "REG_3V") (pin "1") (pinfunction "GND/Adj_1") (pintype "output"))
    )
    (net (code "232") (name "Net-(REG_3V-Vin)") (class "Default")
      (node (ref "R62") (pin "1") (pinfunction "1_1") (pintype "passive"))
      (node (ref "REG_3V") (pin "3") (pinfunction "Vin_3") (pintype "output"))
    )
    (net (code "233") (name "Net-(REG_3V3-GND{slash}Adj)") (class "Default")
      (node (ref "R51") (pin "1") (pinfunction "1_1") (pintype "passive"))
      (node (ref "R52") (pin "2") (pinfunction "2_2") (pintype "passive"))
      (node (ref "REG_3V3") (pin "1") (pinfunction "GND/Adj_1") (pintype "output"))
    )
    (net (code "234") (name "Net-(REG_3V3-Vin)") (class "Default")
      (node (ref "R61") (pin "1") (pinfunction "1_1") (pintype "passive"))
      (node (ref "REG_3V3") (pin "3") (pinfunction "Vin_3") (pintype "output"))
    )
    (net (code "235") (name "Net-(REG_5V-GND{slash}Adj)") (class "Default")
      (node (ref "R49") (pin "1") (pinfunction "1_1") (pintype "passive"))
      (node (ref "R50") (pin "2") (pinfunction "2_2") (pintype "passive"))
      (node (ref "REG_5V") (pin "1") (pinfunction "GND/Adj_1") (pintype "output"))
    )
    (net (code "236") (name "Net-(REG_5V-Vin)") (class "Default")
      (node (ref "R60") (pin "1") (pinfunction "1_1") (pintype "passive"))
      (node (ref "REG_5V") (pin "3") (pinfunction "Vin_3") (pintype "output"))
    )
    (net (code "237") (name "Net-(U1-JTAGSEL)") (class "Default")
      (node (ref "JTAG_SEL") (pin "2") (pinfunction "2_2") (pintype "passive"))
      (node (ref "U1") (pin "105") (pinfunction "JTAGSEL_105") (pintype "input"))
    )
    (net (code "238") (name "Net-(U1-NWR0{slash}NWE{slash}CFWE)") (class "Default")
      (node (ref "U1") (pin "171") (pinfunction "NWR0/NWE/CFWE_171") (pintype "output"))
      (node (ref "U8") (pin "46") (pinfunction "1A2_46") (pintype "bidirectional"))
    )
    (net (code "239") (name "Net-(U1-NWR1{slash}NBS1{slash}CFIOR)") (class "Default")
      (node (ref "U1") (pin "172") (pinfunction "NWR1/NBS1/CFIOR_172") (pintype "output"))
      (node (ref "U8") (pin "44") (pinfunction "1A3_44") (pintype "bidirectional"))
    )
    (net (code "240") (name "Net-(U1-PA25{slash}TWD{slash}IRQ2)") (class "Default")
      (node (ref "R16") (pin "1") (pinfunction "1_1") (pintype "passive"))
      (node (ref "U1") (pin "71") (pinfunction "PA25/TWD/IRQ2_71") (pintype "bidirectional"))
      (node (ref "U15") (pin "5") (pinfunction "SDA_5") (pintype "bidirectional"))
    )
    (net (code "241") (name "Net-(U1-PA26{slash}TWCK{slash}IRQ1)") (class "Default")
      (node (ref "R17") (pin "1") (pinfunction "1_1") (pintype "passive"))
      (node (ref "U1") (pin "72") (pinfunction "PA26/TWCK/IRQ1_72") (pintype "bidirectional"))
      (node (ref "U15") (pin "6") (pinfunction "SCL_6") (pintype "input"))
    )
    (net (code "242") (name "Net-(U1-PLLRCA)") (class "Default")
      (node (ref "C22") (pin "1") (pinfunction "1_1") (pintype "passive"))
      (node (ref "R1") (pin "2") (pinfunction "2_2") (pintype "passive"))
      (node (ref "U1") (pin "29") (pinfunction "PLLRCA_29") (pintype "passive"))
    )
    (net (code "243") (name "Net-(U1-PLLRCB)") (class "Default")
      (node (ref "C29") (pin "1") (pinfunction "1_1") (pintype "passive"))
      (node (ref "R2") (pin "2") (pinfunction "2_2") (pintype "passive"))
      (node (ref "U1") (pin "38") (pinfunction "PLLRCB_38") (pintype "passive"))
    )
    (net (code "244") (name "Net-(U1-XIN)") (class "Default")
      (node (ref "C23") (pin "1") (pinfunction "1_1") (pintype "passive"))
      (node (ref "U1") (pin "32") (pinfunction "XIN_32") (pintype "input"))
      (node (ref "X1") (pin "2") (pintype "passive"))
    )
    (net (code "245") (name "Net-(U1-XIN32)") (class "Default")
      (node (ref "C28") (pin "1") (pinfunction "1_1") (pintype "passive"))
      (node (ref "U1") (pin "36") (pinfunction "XIN32_36") (pintype "input"))
      (node (ref "X2") (pin "2") (pintype "passive"))
    )
    (net (code "246") (name "Net-(U1-XOUT)") (class "Default")
      (node (ref "C27") (pin "1") (pinfunction "1_1") (pintype "passive"))
      (node (ref "U1") (pin "31") (pinfunction "XOUT_31") (pintype "output"))
      (node (ref "X1") (pin "1") (pintype "passive"))
    )
    (net (code "247") (name "Net-(U1-XOUT32)") (class "Default")
      (node (ref "C30") (pin "1") (pinfunction "1_1") (pintype "passive"))
      (node (ref "U1") (pin "35") (pinfunction "XOUT32_35") (pintype "output"))
      (node (ref "X2") (pin "1") (pintype "passive"))
    )
    (net (code "248") (name "Net-(U3-PFO)") (class "Default")
      (node (ref "R57") (pin "1") (pinfunction "1_1") (pintype "passive"))
      (node (ref "U3") (pin "5") (pinfunction "PFO_5") (pintype "output"))
    )
    (net (code "249") (name "Net-(U5-IN0{slash}SDI)") (class "Default")
      (node (ref "P2") (pin "1") (pinfunction "1_1") (pintype "passive"))
      (node (ref "U5") (pin "14") (pinfunction "IN0/SDI_14") (pintype "input"))
    )
    (net (code "250") (name "Net-(U5-IN1{slash}SDO)") (class "Default")
      (node (ref "P2") (pin "2") (pinfunction "2_2") (pintype "passive"))
      (node (ref "U5") (pin "24") (pinfunction "IN1/SDO_24") (pintype "bidirectional"))
    )
    (net (code "251") (name "Net-(U5-IN2{slash}MODE)") (class "Default")
      (node (ref "P2") (pin "3") (pinfunction "3_3") (pintype "passive"))
      (node (ref "U5") (pin "36") (pinfunction "IN2/MODE_36") (pintype "input"))
    )
    (net (code "252") (name "Net-(U5-ISPEN)") (class "Default")
      (node (ref "P3") (pin "2") (pinfunction "2_2") (pintype "passive"))
      (node (ref "U5") (pin "13") (pinfunction "ISPEN_13") (pintype "input"))
    )
    (net (code "253") (name "Net-(U5-I{slash}O13)") (class "Default")
      (node (ref "P5") (pin "2") (pinfunction "2_2") (pintype "passive"))
      (node (ref "U5") (pin "30") (pinfunction "I/O13_30") (pintype "bidirectional"))
    )
    (net (code "254") (name "Net-(U5-I{slash}O14)") (class "Default")
      (node (ref "P5") (pin "4") (pinfunction "4_4") (pintype "passive"))
      (node (ref "U5") (pin "31") (pinfunction "I/O14_31") (pintype "bidirectional"))
    )
    (net (code "255") (name "Net-(U5-I{slash}O15)") (class "Default")
      (node (ref "P5") (pin "6") (pinfunction "6_6") (pintype "passive"))
      (node (ref "U5") (pin "32") (pinfunction "I/O15_32") (pintype "bidirectional"))
    )
    (net (code "256") (name "Net-(U5-I{slash}O16)") (class "Default")
      (node (ref "P5") (pin "8") (pinfunction "8_8") (pintype "passive"))
      (node (ref "U5") (pin "37") (pinfunction "I/O16_37") (pintype "bidirectional"))
    )
    (net (code "257") (name "Net-(U5-I{slash}O17)") (class "Default")
      (node (ref "P5") (pin "10") (pinfunction "10_10") (pintype "passive"))
      (node (ref "U5") (pin "38") (pinfunction "I/O17_38") (pintype "bidirectional"))
    )
    (net (code "258") (name "Net-(U5-I{slash}O18)") (class "Default")
      (node (ref "P5") (pin "12") (pinfunction "12_12") (pintype "passive"))
      (node (ref "U5") (pin "39") (pinfunction "I/O18_39") (pintype "bidirectional"))
    )
    (net (code "259") (name "Net-(U5-I{slash}O19)") (class "Default")
      (node (ref "P5") (pin "14") (pinfunction "14_14") (pintype "passive"))
      (node (ref "U5") (pin "40") (pinfunction "I/O19_40") (pintype "bidirectional"))
    )
    (net (code "260") (name "Net-(U5-I{slash}O20)") (class "Default")
      (node (ref "P5") (pin "16") (pinfunction "16_16") (pintype "passive"))
      (node (ref "U5") (pin "41") (pinfunction "I/O20_41") (pintype "bidirectional"))
    )
    (net (code "261") (name "Net-(U5-Y2{slash}SCLK)") (class "Default")
      (node (ref "P2") (pin "4") (pinfunction "4_4") (pintype "passive"))
      (node (ref "U5") (pin "33") (pinfunction "Y2/SCLK_33") (pintype "input"))
    )
    (net (code "262") (name "Net-(U13-DEB)") (class "Default")
      (node (ref "C41") (pin "1") (pinfunction "1_1") (pintype "passive"))
      (node (ref "U13") (pin "7") (pinfunction "DEB_7") (pintype "passive"))
    )
    (net (code "263") (name "Net-(U13-OSC)") (class "Default")
      (node (ref "C43") (pin "1") (pinfunction "1_1") (pintype "passive"))
      (node (ref "U13") (pin "6") (pinfunction "OSC_6") (pintype "passive"))
    )
    (net (code "264") (name "Net-(U16-AN_1{slash}LED_SPEED)") (class "Default")
      (node (ref "R19") (pin "2") (pinfunction "2_2") (pintype "passive"))
      (node (ref "U16") (pin "27") (pinfunction "AN_1/LED_SPEED_27") (pintype "bidirectional"))
    )
    (net (code "265") (name "Net-(U16-PFBIN1)") (class "Default")
      (node (ref "C61") (pin "1") (pinfunction "1_1") (pintype "passive"))
      (node (ref "C63") (pin "1") (pinfunction "1_1") (pintype "passive"))
      (node (ref "C65") (pin "1") (pinfunction "1_1") (pintype "passive"))
      (node (ref "C66") (pin "1") (pinfunction "1_1") (pintype "passive"))
      (node (ref "U16") (pin "18") (pinfunction "PFBIN1_18") (pintype "input"))
      (node (ref "U16") (pin "23") (pinfunction "PFBOUT_23") (pintype "output"))
      (node (ref "U16") (pin "37") (pinfunction "PFBIN2_37") (pintype "input"))
    )
    (net (code "266") (name "Net-(U16-RBIAS)") (class "Default")
      (node (ref "R40") (pin "1") (pinfunction "1_1") (pintype "passive"))
      (node (ref "U16") (pin "24") (pinfunction "RBIAS_24") (pintype "passive"))
    )
    (net (code "267") (name "Net-(U16-RSVD1)") (class "Default")
      (node (ref "R29") (pin "2") (pinfunction "2_2") (pintype "passive"))
      (node (ref "U16") (pin "20") (pinfunction "RSVD1_20") (pintype "bidirectional"))
    )
    (net (code "268") (name "Net-(U16-RSVD2)") (class "Default")
      (node (ref "R28") (pin "2") (pinfunction "2_2") (pintype "passive"))
      (node (ref "U16") (pin "21") (pinfunction "RSVD2_21") (pintype "bidirectional"))
    )
    (net (code "269") (name "Net-(U16-X1)") (class "Default")
      (node (ref "C59") (pin "1") (pinfunction "1_1") (pintype "passive"))
      (node (ref "U16") (pin "34") (pinfunction "X1_34") (pintype "input"))
      (node (ref "X3") (pin "2") (pintype "passive"))
    )
    (net (code "270") (name "Net-(U16-X2)") (class "Default")
      (node (ref "C60") (pin "1") (pinfunction "1_1") (pintype "passive"))
      (node (ref "U16") (pin "33") (pinfunction "X2_33") (pintype "output"))
      (node (ref "X3") (pin "1") (pintype "passive"))
    )
    (net (code "271") (name "Net-(U16-~{PWR_DOWN}{slash}INT)") (class "Default")
      (node (ref "R59") (pin "1") (pinfunction "1_1") (pintype "passive"))
      (node (ref "U16") (pin "7") (pinfunction "~{PWR_DOWN}/INT_7") (pintype "bidirectional"))
    )
    (net (code "272") (name "Net-(U17-LINSEL)") (class "Default")
      (node (ref "R63") (pin "1") (pinfunction "1_1") (pintype "passive"))
      (node (ref "R64") (pin "2") (pinfunction "2_2") (pintype "passive"))
      (node (ref "U17") (pin "13") (pinfunction "LINSEL_13") (pintype "input"))
    )
    (net (code "273") (name "Net-(U17-MICGAIN+)") (class "Default")
      (node (ref "R25") (pin "2") (pinfunction "2_2") (pintype "passive"))
      (node (ref "U17") (pin "9") (pinfunction "MICGAIN+_9") (pintype "output"))
    )
    (net (code "274") (name "Net-(U17-MICGAIN-)") (class "Default")
      (node (ref "R31") (pin "2") (pinfunction "2_2") (pintype "passive"))
      (node (ref "U17") (pin "12") (pinfunction "MICGAIN-_12") (pintype "output"))
    )
    (net (code "275") (name "Net-(U17-MICIN+)") (class "Default")
      (node (ref "R26") (pin "2") (pinfunction "2_2") (pintype "passive"))
      (node (ref "R31") (pin "1") (pinfunction "1_1") (pintype "passive"))
      (node (ref "U17") (pin "11") (pinfunction "MICIN+_11") (pintype "input"))
    )
    (net (code "276") (name "Net-(U17-MICIN-)") (class "Default")
      (node (ref "R25") (pin "1") (pinfunction "1_1") (pintype "passive"))
      (node (ref "R32") (pin "2") (pinfunction "2_2") (pintype "passive"))
      (node (ref "U17") (pin "10") (pinfunction "MICIN-_10") (pintype "input"))
    )
    (net (code "277") (name "Net-(U20-CAS)") (class "Default")
      (node (ref "R56") (pin "1") (pinfunction "1_1") (pintype "passive"))
      (node (ref "U20") (pin "2") (pinfunction "CAS_2") (pintype "input"))
    )
    (net (code "278") (name "Net-(U20-RAS)") (class "Default")
      (node (ref "R55") (pin "1") (pinfunction "1_1") (pintype "passive"))
      (node (ref "U20") (pin "27") (pinfunction "RAS_27") (pintype "input"))
    )
    (net (code "279") (name "unconnected-(J2-RINGSW-PadB)") (class "Default")
      (node (ref "J2") (pin "B") (pinfunction "RINGSW_B") (pintype "passive"))
    )
    (net (code "280") (name "unconnected-(J2-TIPSW-PadC)") (class "Default")
      (node (ref "J2") (pin "C") (pinfunction "TIPSW_C") (pintype "passive"))
    )
    (net (code "281") (name "unconnected-(J3-RINGSW-PadB)") (class "Default")
      (node (ref "J3") (pin "B") (pinfunction "RINGSW_B") (pintype "passive"))
    )
    (net (code "282") (name "unconnected-(J3-TIPSW-PadC)") (class "Default")
      (node (ref "J3") (pin "C") (pinfunction "TIPSW_C") (pintype "passive"))
    )
    (net (code "283") (name "unconnected-(J4-PadSWITCH)") (class "Default")
      (node (ref "J4") (pin "SWITCH") (pinfunction "SWITCH_SWITCH") (pintype "passive"))
    )
    (net (code "284") (name "unconnected-(K1-COL1-Pad4)") (class "Default")
      (node (ref "K1") (pin "4") (pinfunction "COL1_4") (pintype "passive"))
    )
    (net (code "285") (name "unconnected-(K1-COL2-Pad3)") (class "Default")
      (node (ref "K1") (pin "3") (pinfunction "COL2_3") (pintype "passive"))
    )
    (net (code "286") (name "unconnected-(K1-COL3-Pad2)") (class "Default")
      (node (ref "K1") (pin "2") (pinfunction "COL3_2") (pintype "passive"))
    )
    (net (code "287") (name "unconnected-(K1-COL4-Pad1)") (class "Default")
      (node (ref "K1") (pin "1") (pinfunction "COL4_1") (pintype "passive"))
    )
    (net (code "288") (name "unconnected-(K1-ROW1-Pad8)") (class "Default")
      (node (ref "K1") (pin "8") (pinfunction "ROW1_8") (pintype "passive"))
    )
    (net (code "289") (name "unconnected-(K1-ROW2-Pad7)") (class "Default")
      (node (ref "K1") (pin "7") (pinfunction "ROW2_7") (pintype "passive"))
    )
    (net (code "290") (name "unconnected-(K1-ROW3-Pad6)") (class "Default")
      (node (ref "K1") (pin "6") (pinfunction "ROW3_6") (pintype "passive"))
    )
    (net (code "291") (name "unconnected-(K1-ROW4-Pad5)") (class "Default")
      (node (ref "K1") (pin "5") (pinfunction "ROW4_5") (pintype "passive"))
    )
    (net (code "292") (name "unconnected-(P1-Pad2)") (class "Default")
      (node (ref "P1") (pin "2") (pinfunction "2_2") (pintype "passive"))
    )
    (net (code "293") (name "unconnected-(P5-Pad1)") (class "Default")
      (node (ref "P5") (pin "1") (pinfunction "1_1") (pintype "passive"))
    )
    (net (code "294") (name "unconnected-(P5-Pad3)") (class "Default")
      (node (ref "P5") (pin "3") (pinfunction "3_3") (pintype "passive"))
    )
    (net (code "295") (name "unconnected-(P5-Pad5)") (class "Default")
      (node (ref "P5") (pin "5") (pinfunction "5_5") (pintype "passive"))
    )
    (net (code "296") (name "unconnected-(P5-Pad7)") (class "Default")
      (node (ref "P5") (pin "7") (pinfunction "7_7") (pintype "passive"))
    )
    (net (code "297") (name "unconnected-(P5-Pad9)") (class "Default")
      (node (ref "P5") (pin "9") (pinfunction "9_9") (pintype "passive"))
    )
    (net (code "298") (name "unconnected-(P5-Pad11)") (class "Default")
      (node (ref "P5") (pin "11") (pinfunction "11_11") (pintype "passive"))
    )
    (net (code "299") (name "unconnected-(P5-Pad13)") (class "Default")
      (node (ref "P5") (pin "13") (pinfunction "13_13") (pintype "passive"))
    )
    (net (code "300") (name "unconnected-(P6-Pad11)") (class "Default")
      (node (ref "P6") (pin "11") (pinfunction "11_11") (pintype "passive"))
    )
    (net (code "301") (name "unconnected-(P6-Pad13)") (class "Default")
      (node (ref "P6") (pin "13") (pinfunction "13_13") (pintype "passive"))
    )
    (net (code "302") (name "unconnected-(P6-Pad15)") (class "Default")
      (node (ref "P6") (pin "15") (pinfunction "15_15") (pintype "passive"))
    )
    (net (code "303") (name "unconnected-(U1-A20-Pad158)") (class "Default")
      (node (ref "U1") (pin "158") (pinfunction "A20_158") (pintype "output"))
    )
    (net (code "304") (name "unconnected-(U1-A21-Pad159)") (class "Default")
      (node (ref "U1") (pin "159") (pinfunction "A21_159") (pintype "output"))
    )
    (net (code "305") (name "unconnected-(U1-A22-Pad160)") (class "Default")
      (node (ref "U1") (pin "160") (pinfunction "A22_160") (pintype "output"))
    )
    (net (code "306") (name "unconnected-(U1-BMS{slash}PA31{slash}DTXD{slash}RTS2-Pad79)") (class "Default")
      (node (ref "U1") (pin "79") (pinfunction "BMS/PA31/DTXD/RTS2_79") (pintype "bidirectional"))
    )
    (net (code "307") (name "unconnected-(U1-CAS-Pad177)") (class "Default")
      (node (ref "U1") (pin "177") (pinfunction "CAS_177") (pintype "output"))
    )
    (net (code "308") (name "unconnected-(U1-DDM-Pad127)") (class "Default")
      (node (ref "U1") (pin "127") (pinfunction "DDM_127") (pintype "passive"))
    )
    (net (code "309") (name "unconnected-(U1-DDP-Pad128)") (class "Default")
      (node (ref "U1") (pin "128") (pinfunction "DDP_128") (pintype "passive"))
    )
    (net (code "310") (name "unconnected-(U1-HDMA-Pad125)") (class "Default")
      (node (ref "U1") (pin "125") (pinfunction "HDMA_125") (pintype "passive"))
    )
    (net (code "311") (name "unconnected-(U1-HDPA-Pad126)") (class "Default")
      (node (ref "U1") (pin "126") (pinfunction "HDPA_126") (pintype "passive"))
    )
    (net (code "312") (name "unconnected-(U1-NWR3{slash}NBS3{slash}CFIOW-Pad173)") (class "Default")
      (node (ref "U1") (pin "173") (pinfunction "NWR3/NBS3/CFIOW_173") (pintype "output"))
    )
    (net (code "313") (name "unconnected-(U1-PA0{slash}MISO{slash}PCK3-Pad42)") (class "Default")
      (node (ref "U1") (pin "42") (pinfunction "PA0/MISO/PCK3_42") (pintype "bidirectional"))
    )
    (net (code "314") (name "unconnected-(U1-PA17{slash}TXD0{slash}TIOA0-Pad61)") (class "Default")
      (node (ref "U1") (pin "61") (pinfunction "PA17/TXD0/TIOA0_61") (pintype "bidirectional"))
    )
    (net (code "315") (name "unconnected-(U1-PA18{slash}RXD0{slash}TIOB0-Pad64)") (class "Default")
      (node (ref "U1") (pin "64") (pinfunction "PA18/RXD0/TIOB0_64") (pintype "bidirectional"))
    )
    (net (code "316") (name "unconnected-(U1-PA19{slash}SCK0{slash}TIOA1-Pad65)") (class "Default")
      (node (ref "U1") (pin "65") (pinfunction "PA19/SCK0/TIOA1_65") (pintype "bidirectional"))
    )
    (net (code "317") (name "unconnected-(U1-PA20{slash}CTS0{slash}TIOB1-Pad66)") (class "Default")
      (node (ref "U1") (pin "66") (pinfunction "PA20/CTS0/TIOB1_66") (pintype "bidirectional"))
    )
    (net (code "318") (name "unconnected-(U1-PA21{slash}RTS0{slash}TIOA2-Pad67)") (class "Default")
      (node (ref "U1") (pin "67") (pinfunction "PA21/RTS0/TIOA2_67") (pintype "bidirectional"))
    )
    (net (code "319") (name "unconnected-(U1-PA22{slash}RXD2{slash}TIOB2-Pad68)") (class "Default")
      (node (ref "U1") (pin "68") (pinfunction "PA22/RXD2/TIOB2_68") (pintype "bidirectional"))
    )
    (net (code "320") (name "unconnected-(U1-PA23{slash}TXD2{slash}IRQ3-Pad69)") (class "Default")
      (node (ref "U1") (pin "69") (pinfunction "PA23/TXD2/IRQ3_69") (pintype "bidirectional"))
    )
    (net (code "321") (name "unconnected-(U1-PA27{slash}MCCK{slash}TCLK3-Pad73)") (class "Default")
      (node (ref "U1") (pin "73") (pinfunction "PA27/MCCK/TCLK3_73") (pintype "bidirectional"))
    )
    (net (code "322") (name "unconnected-(U1-PA28{slash}MCCDA{slash}TCLK4-Pad74)") (class "Default")
      (node (ref "U1") (pin "74") (pinfunction "PA28/MCCDA/TCLK4_74") (pintype "bidirectional"))
    )
    (net (code "323") (name "unconnected-(U1-PA29{slash}MCCA0{slash}TCLK5-Pad77)") (class "Default")
      (node (ref "U1") (pin "77") (pinfunction "PA29/MCCA0/TCLK5_77") (pintype "bidirectional"))
    )
    (net (code "324") (name "unconnected-(U1-PA30{slash}DRXD{slash}CTS2-Pad78)") (class "Default")
      (node (ref "U1") (pin "78") (pinfunction "PA30/DRXD/CTS2_78") (pintype "bidirectional"))
    )
    (net (code "325") (name "unconnected-(U1-PB4{slash}RK0{slash}MCDA2-Pad84)") (class "Default")
      (node (ref "U1") (pin "84") (pinfunction "PB4/RK0/MCDA2_84") (pintype "bidirectional"))
    )
    (net (code "326") (name "unconnected-(U1-PB5{slash}RF0{slash}MCDA3-Pad85)") (class "Default")
      (node (ref "U1") (pin "85") (pinfunction "PB5/RF0/MCDA3_85") (pintype "bidirectional"))
    )
    (net (code "327") (name "unconnected-(U1-PB6{slash}TF1{slash}TIOA3-Pad86)") (class "Default")
      (node (ref "U1") (pin "86") (pinfunction "PB6/TF1/TIOA3_86") (pintype "bidirectional"))
    )
    (net (code "328") (name "unconnected-(U1-PB7{slash}TK1{slash}TIOB3-Pad87)") (class "Default")
      (node (ref "U1") (pin "87") (pinfunction "PB7/TK1/TIOB3_87") (pintype "bidirectional"))
    )
    (net (code "329") (name "unconnected-(U1-PB8{slash}TD1{slash}TIOA4-Pad88)") (class "Default")
      (node (ref "U1") (pin "88") (pinfunction "PB8/TD1/TIOA4_88") (pintype "bidirectional"))
    )
    (net (code "330") (name "unconnected-(U1-PB9{slash}RD1{slash}TIOB4-Pad89)") (class "Default")
      (node (ref "U1") (pin "89") (pinfunction "PB9/RD1/TIOB4_89") (pintype "bidirectional"))
    )
    (net (code "331") (name "unconnected-(U1-PB10{slash}RK1{slash}TIOA5-Pad90)") (class "Default")
      (node (ref "U1") (pin "90") (pinfunction "PB10/RK1/TIOA5_90") (pintype "bidirectional"))
    )
    (net (code "332") (name "unconnected-(U1-PB11{slash}RF1{slash}TIOB5-Pad91)") (class "Default")
      (node (ref "U1") (pin "91") (pinfunction "PB11/RF1/TIOB5_91") (pintype "bidirectional"))
    )
    (net (code "333") (name "unconnected-(U1-PB20{slash}TXD1-Pad102)") (class "Default")
      (node (ref "U1") (pin "102") (pinfunction "PB20/TXD1_102") (pintype "bidirectional"))
    )
    (net (code "334") (name "unconnected-(U1-PB21{slash}RXD1-Pad103)") (class "Default")
      (node (ref "U1") (pin "103") (pinfunction "PB21/RXD1_103") (pintype "bidirectional"))
    )
    (net (code "335") (name "unconnected-(U1-PB22{slash}SCK1-Pad104)") (class "Default")
      (node (ref "U1") (pin "104") (pinfunction "PB22/SCK1_104") (pintype "bidirectional"))
    )
    (net (code "336") (name "unconnected-(U1-PB23{slash}DCD1-Pad118)") (class "Default")
      (node (ref "U1") (pin "118") (pinfunction "PB23/DCD1_118") (pintype "bidirectional"))
    )
    (net (code "337") (name "unconnected-(U1-PB24{slash}CTS1-Pad119)") (class "Default")
      (node (ref "U1") (pin "119") (pinfunction "PB24/CTS1_119") (pintype "bidirectional"))
    )
    (net (code "338") (name "unconnected-(U1-PB25{slash}DSR1{slash}EF100-Pad120)") (class "Default")
      (node (ref "U1") (pin "120") (pinfunction "PB25/DSR1/EF100_120") (pintype "bidirectional"))
    )
    (net (code "339") (name "unconnected-(U1-PB26{slash}RTS1-Pad121)") (class "Default")
      (node (ref "U1") (pin "121") (pinfunction "PB26/RTS1_121") (pintype "bidirectional"))
    )
    (net (code "340") (name "unconnected-(U1-PB28{slash}FIQ-Pad123)") (class "Default")
      (node (ref "U1") (pin "123") (pinfunction "PB28/FIQ_123") (pintype "bidirectional"))
    )
    (net (code "341") (name "unconnected-(U1-PB29{slash}IRQ0-Pad124)") (class "Default")
      (node (ref "U1") (pin "124") (pinfunction "PB29/IRQ0_124") (pintype "bidirectional"))
    )
    (net (code "342") (name "unconnected-(U1-PC0{slash}BFCK-Pad17)") (class "Default")
      (node (ref "U1") (pin "17") (pinfunction "PC0/BFCK_17") (pintype "bidirectional"))
    )
    (net (code "343") (name "unconnected-(U1-PC1{slash}BFRDY{slash}SMOE-Pad18)") (class "Default")
      (node (ref "U1") (pin "18") (pinfunction "PC1/BFRDY/SMOE_18") (pintype "bidirectional"))
    )
    (net (code "344") (name "unconnected-(U1-PC2{slash}BFAVD-Pad21)") (class "Default")
      (node (ref "U1") (pin "21") (pinfunction "PC2/BFAVD_21") (pintype "bidirectional"))
    )
    (net (code "345") (name "unconnected-(U1-PC3{slash}BFBAA{slash}SMWE-Pad22)") (class "Default")
      (node (ref "U1") (pin "22") (pinfunction "PC3/BFBAA/SMWE_22") (pintype "bidirectional"))
    )
    (net (code "346") (name "unconnected-(U1-PC4{slash}BFOE-Pad23)") (class "Default")
      (node (ref "U1") (pin "23") (pinfunction "PC4/BFOE_23") (pintype "bidirectional"))
    )
    (net (code "347") (name "unconnected-(U1-PC5{slash}BFWE-Pad24)") (class "Default")
      (node (ref "U1") (pin "24") (pinfunction "PC5/BFWE_24") (pintype "bidirectional"))
    )
    (net (code "348") (name "unconnected-(U1-PC7{slash}A23-Pad161)") (class "Default")
      (node (ref "U1") (pin "161") (pinfunction "PC7/A23_161") (pintype "bidirectional"))
    )
    (net (code "349") (name "unconnected-(U1-PC8{slash}A24-Pad162)") (class "Default")
      (node (ref "U1") (pin "162") (pinfunction "PC8/A24_162") (pintype "bidirectional"))
    )
    (net (code "350") (name "unconnected-(U1-PC9{slash}A25{slash}CFRNW-Pad163)") (class "Default")
      (node (ref "U1") (pin "163") (pinfunction "PC9/A25/CFRNW_163") (pintype "bidirectional"))
    )
    (net (code "351") (name "unconnected-(U1-PC14-Pad15)") (class "Default")
      (node (ref "U1") (pin "15") (pinfunction "PC14_15") (pintype "bidirectional"))
    )
    (net (code "352") (name "unconnected-(U1-PC15-Pad16)") (class "Default")
      (node (ref "U1") (pin "16") (pinfunction "PC15_16") (pintype "bidirectional"))
    )
    (net (code "353") (name "unconnected-(U1-PC16{slash}D16-Pad201)") (class "Default")
      (node (ref "U1") (pin "201") (pinfunction "PC16/D16_201") (pintype "bidirectional"))
    )
    (net (code "354") (name "unconnected-(U1-PC17{slash}D17-Pad202)") (class "Default")
      (node (ref "U1") (pin "202") (pinfunction "PC17/D17_202") (pintype "bidirectional"))
    )
    (net (code "355") (name "unconnected-(U1-PC18{slash}D18-Pad203)") (class "Default")
      (node (ref "U1") (pin "203") (pinfunction "PC18/D18_203") (pintype "bidirectional"))
    )
    (net (code "356") (name "unconnected-(U1-PC19{slash}D19-Pad204)") (class "Default")
      (node (ref "U1") (pin "204") (pinfunction "PC19/D19_204") (pintype "bidirectional"))
    )
    (net (code "357") (name "unconnected-(U1-PC20{slash}D20-Pad205)") (class "Default")
      (node (ref "U1") (pin "205") (pinfunction "PC20/D20_205") (pintype "bidirectional"))
    )
    (net (code "358") (name "unconnected-(U1-PC21{slash}D21-Pad206)") (class "Default")
      (node (ref "U1") (pin "206") (pinfunction "PC21/D21_206") (pintype "bidirectional"))
    )
    (net (code "359") (name "unconnected-(U1-PC22{slash}D22-Pad207)") (class "Default")
      (node (ref "U1") (pin "207") (pinfunction "PC22/D22_207") (pintype "bidirectional"))
    )
    (net (code "360") (name "unconnected-(U1-PC23{slash}D23-Pad208)") (class "Default")
      (node (ref "U1") (pin "208") (pinfunction "PC23/D23_208") (pintype "bidirectional"))
    )
    (net (code "361") (name "unconnected-(U1-PC25{slash}D25-Pad2)") (class "Default")
      (node (ref "U1") (pin "2") (pinfunction "PC25/D25_2") (pintype "bidirectional"))
    )
    (net (code "362") (name "unconnected-(U1-RAS-Pad176)") (class "Default")
      (node (ref "U1") (pin "176") (pinfunction "RAS_176") (pintype "output"))
    )
    (net (code "363") (name "unconnected-(U1-SDA10-Pad144)") (class "Default")
      (node (ref "U1") (pin "144") (pinfunction "SDA10_144") (pintype "output"))
    )
    (net (code "364") (name "unconnected-(U1-SDCK-Pad174)") (class "Default")
      (node (ref "U1") (pin "174") (pinfunction "SDCK_174") (pintype "output"))
    )
    (net (code "365") (name "unconnected-(U1-SDCKE-Pad175)") (class "Default")
      (node (ref "U1") (pin "175") (pinfunction "SDCKE_175") (pintype "output"))
    )
    (net (code "366") (name "unconnected-(U1-SDWE-Pad178)") (class "Default")
      (node (ref "U1") (pin "178") (pinfunction "SDWE_178") (pintype "output"))
    )
    (net (code "367") (name "unconnected-(U3-WDI-Pad6)") (class "Default")
      (node (ref "U3") (pin "6") (pinfunction "WDI_6") (pintype "input"))
    )
    (net (code "368") (name "unconnected-(U3-WDO-Pad8)") (class "Default")
      (node (ref "U3") (pin "8") (pinfunction "WDO_8") (pintype "output"))
    )
    (net (code "369") (name "unconnected-(U5-IN3{slash}GOE0-Pad2)") (class "Default")
      (node (ref "U5") (pin "2") (pinfunction "IN3/GOE0_2") (pintype "input"))
    )
    (net (code "370") (name "unconnected-(U5-I{slash}O21-Pad42)") (class "Default")
      (node (ref "U5") (pin "42") (pinfunction "I/O21_42") (pintype "bidirectional"))
    )
    (net (code "371") (name "unconnected-(U5-I{slash}O22-Pad43)") (class "Default")
      (node (ref "U5") (pin "43") (pinfunction "I/O22_43") (pintype "bidirectional"))
    )
    (net (code "372") (name "unconnected-(U5-I{slash}O23-Pad44)") (class "Default")
      (node (ref "U5") (pin "44") (pinfunction "I/O23_44") (pintype "bidirectional"))
    )
    (net (code "373") (name "unconnected-(U5-I{slash}O24-Pad3)") (class "Default")
      (node (ref "U5") (pin "3") (pinfunction "I/O24_3") (pintype "bidirectional"))
    )
    (net (code "374") (name "unconnected-(U5-I{slash}O25-Pad4)") (class "Default")
      (node (ref "U5") (pin "4") (pinfunction "I/O25_4") (pintype "bidirectional"))
    )
    (net (code "375") (name "unconnected-(U5-I{slash}O26-Pad5)") (class "Default")
      (node (ref "U5") (pin "5") (pinfunction "I/O26_5") (pintype "bidirectional"))
    )
    (net (code "376") (name "unconnected-(U5-I{slash}O27-Pad6)") (class "Default")
      (node (ref "U5") (pin "6") (pinfunction "I/O27_6") (pintype "bidirectional"))
    )
    (net (code "377") (name "unconnected-(U5-I{slash}O28-Pad7)") (class "Default")
      (node (ref "U5") (pin "7") (pinfunction "I/O28_7") (pintype "bidirectional"))
    )
    (net (code "378") (name "unconnected-(U5-I{slash}O29-Pad8)") (class "Default")
      (node (ref "U5") (pin "8") (pinfunction "I/O29_8") (pintype "bidirectional"))
    )
    (net (code "379") (name "unconnected-(U5-I{slash}O30-Pad9)") (class "Default")
      (node (ref "U5") (pin "9") (pinfunction "I/O30_9") (pintype "bidirectional"))
    )
    (net (code "380") (name "unconnected-(U5-I{slash}O31-Pad10)") (class "Default")
      (node (ref "U5") (pin "10") (pinfunction "I/O31_10") (pintype "bidirectional"))
    )
    (net (code "381") (name "unconnected-(U8-1A4-Pad43)") (class "Default")
      (node (ref "U8") (pin "43") (pinfunction "1A4_43") (pintype "bidirectional"))
    )
    (net (code "382") (name "unconnected-(U8-1B4-Pad6)") (class "Default")
      (node (ref "U8") (pin "6") (pinfunction "1B4_6") (pintype "bidirectional"))
    )
    (net (code "383") (name "unconnected-(U9-D-Pad14)") (class "Default")
      (node (ref "U9") (pin "14") (pinfunction "D_14") (pintype "input"))
    )
    (net (code "384") (name "unconnected-(U9-H-Pad13)") (class "Default")
      (node (ref "U9") (pin "13") (pinfunction "H_13") (pintype "tri_state"))
    )
    (net (code "385") (name "unconnected-(U9-NC-Pad12)") (class "Default")
      (node (ref "U9") (pin "12") (pinfunction "NC_12") (pintype "passive"))
    )
    (net (code "386") (name "unconnected-(U11-A-Pad3)") (class "Default")
      (node (ref "U11") (pin "3") (pinfunction "A_3") (pintype "input"))
    )
    (net (code "387") (name "unconnected-(U11-B-Pad6)") (class "Default")
      (node (ref "U11") (pin "6") (pinfunction "B_6") (pintype "input"))
    )
    (net (code "388") (name "unconnected-(U11-E-Pad4)") (class "Default")
      (node (ref "U11") (pin "4") (pinfunction "E_4") (pintype "tri_state"))
    )
    (net (code "389") (name "unconnected-(U11-F-Pad5)") (class "Default")
      (node (ref "U11") (pin "5") (pinfunction "F_5") (pintype "tri_state"))
    )
    (net (code "390") (name "unconnected-(U11-NC-Pad12)") (class "Default")
      (node (ref "U11") (pin "12") (pinfunction "NC_12") (pintype "passive"))
    )
    (net (code "391") (name "unconnected-(U13-ROW1-Pad1)") (class "Default")
      (node (ref "U13") (pin "1") (pinfunction "ROW1_1") (pintype "passive"))
    )
    (net (code "392") (name "unconnected-(U16-25MHZ_OUT-Pad25)") (class "Default")
      (node (ref "U16") (pin "25") (pinfunction "25MHZ_OUT_25") (pintype "output"))
    )
    (net (code "393") (name "unconnected-(U18-2A1-Pad36)") (class "Default")
      (node (ref "U18") (pin "36") (pinfunction "2A1_36") (pintype "bidirectional"))
    )
    (net (code "394") (name "unconnected-(U18-2A2-Pad35)") (class "Default")
      (node (ref "U18") (pin "35") (pinfunction "2A2_35") (pintype "bidirectional"))
    )
    (net (code "395") (name "unconnected-(U18-2A3-Pad33)") (class "Default")
      (node (ref "U18") (pin "33") (pinfunction "2A3_33") (pintype "bidirectional"))
    )
    (net (code "396") (name "unconnected-(U18-2A4-Pad32)") (class "Default")
      (node (ref "U18") (pin "32") (pinfunction "2A4_32") (pintype "bidirectional"))
    )
    (net (code "397") (name "unconnected-(U18-2A5-Pad30)") (class "Default")
      (node (ref "U18") (pin "30") (pinfunction "2A5_30") (pintype "bidirectional"))
    )
    (net (code "398") (name "unconnected-(U18-2A6-Pad29)") (class "Default")
      (node (ref "U18") (pin "29") (pinfunction "2A6_29") (pintype "bidirectional"))
    )
    (net (code "399") (name "unconnected-(U18-2A7-Pad27)") (class "Default")
      (node (ref "U18") (pin "27") (pinfunction "2A7_27") (pintype "bidirectional"))
    )
    (net (code "400") (name "unconnected-(U18-2A8-Pad26)") (class "Default")
      (node (ref "U18") (pin "26") (pinfunction "2A8_26") (pintype "bidirectional"))
    )
    (net (code "401") (name "unconnected-(U18-2B1-Pad13)") (class "Default")
      (node (ref "U18") (pin "13") (pinfunction "2B1_13") (pintype "bidirectional"))
    )
    (net (code "402") (name "unconnected-(U18-2B2-Pad14)") (class "Default")
      (node (ref "U18") (pin "14") (pinfunction "2B2_14") (pintype "bidirectional"))
    )
    (net (code "403") (name "unconnected-(U18-2B3-Pad16)") (class "Default")
      (node (ref "U18") (pin "16") (pinfunction "2B3_16") (pintype "bidirectional"))
    )
    (net (code "404") (name "unconnected-(U18-2B4-Pad17)") (class "Default")
      (node (ref "U18") (pin "17") (pinfunction "2B4_17") (pintype "bidirectional"))
    )
    (net (code "405") (name "unconnected-(U18-2B5-Pad19)") (class "Default")
      (node (ref "U18") (pin "19") (pinfunction "2B5_19") (pintype "bidirectional"))
    )
    (net (code "406") (name "unconnected-(U18-2B6-Pad20)") (class "Default")
      (node (ref "U18") (pin "20") (pinfunction "2B6_20") (pintype "bidirectional"))
    )
    (net (code "407") (name "unconnected-(U18-2B7-Pad22)") (class "Default")
      (node (ref "U18") (pin "22") (pinfunction "2B7_22") (pintype "bidirectional"))
    )
    (net (code "408") (name "unconnected-(U18-2B8-Pad23)") (class "Default")
      (node (ref "U18") (pin "23") (pinfunction "2B8_23") (pintype "bidirectional"))
    )
    (net (code "409") (name "unconnected-(U19-2B3-Pad16)") (class "Default")
      (node (ref "U19") (pin "16") (pinfunction "2B3_16") (pintype "bidirectional"))
    )
    (net (code "410") (name "unconnected-(U19-2B4-Pad17)") (class "Default")
      (node (ref "U19") (pin "17") (pinfunction "2B4_17") (pintype "bidirectional"))
    )
    (net (code "411") (name "unconnected-(U19-2B5-Pad19)") (class "Default")
      (node (ref "U19") (pin "19") (pinfunction "2B5_19") (pintype "bidirectional"))
    )
    (net (code "412") (name "unconnected-(U19-2B6-Pad20)") (class "Default")
      (node (ref "U19") (pin "20") (pinfunction "2B6_20") (pintype "bidirectional"))
    )
    (net (code "413") (name "unconnected-(U19-2B7-Pad22)") (class "Default")
      (node (ref "U19") (pin "22") (pinfunction "2B7_22") (pintype "bidirectional"))
    )
    (net (code "414") (name "unconnected-(U19-2B8-Pad23)") (class "Default")
      (node (ref "U19") (pin "23") (pinfunction "2B8_23") (pintype "bidirectional"))
    )
    (net (code "415") (name "unconnected-(U21-2B3-Pad16)") (class "Default")
      (node (ref "U21") (pin "16") (pinfunction "2B3_16") (pintype "bidirectional"))
    )
    (net (code "416") (name "unconnected-(U21-2B4-Pad17)") (class "Default")
      (node (ref "U21") (pin "17") (pinfunction "2B4_17") (pintype "bidirectional"))
    )
    (net (code "417") (name "unconnected-(U21-2B5-Pad19)") (class "Default")
      (node (ref "U21") (pin "19") (pinfunction "2B5_19") (pintype "bidirectional"))
    )
    (net (code "418") (name "unconnected-(U21-2B6-Pad20)") (class "Default")
      (node (ref "U21") (pin "20") (pinfunction "2B6_20") (pintype "bidirectional"))
    )
    (net (code "419") (name "unconnected-(U21-2B7-Pad22)") (class "Default")
      (node (ref "U21") (pin "22") (pinfunction "2B7_22") (pintype "bidirectional"))
    )
    (net (code "420") (name "unconnected-(U21-2B8-Pad23)") (class "Default")
      (node (ref "U21") (pin "23") (pinfunction "2B8_23") (pintype "bidirectional"))
    )
  )
)
